# Aqua_D_CTRL.net
KiCad netlist of a schematic drawn in EAGLE
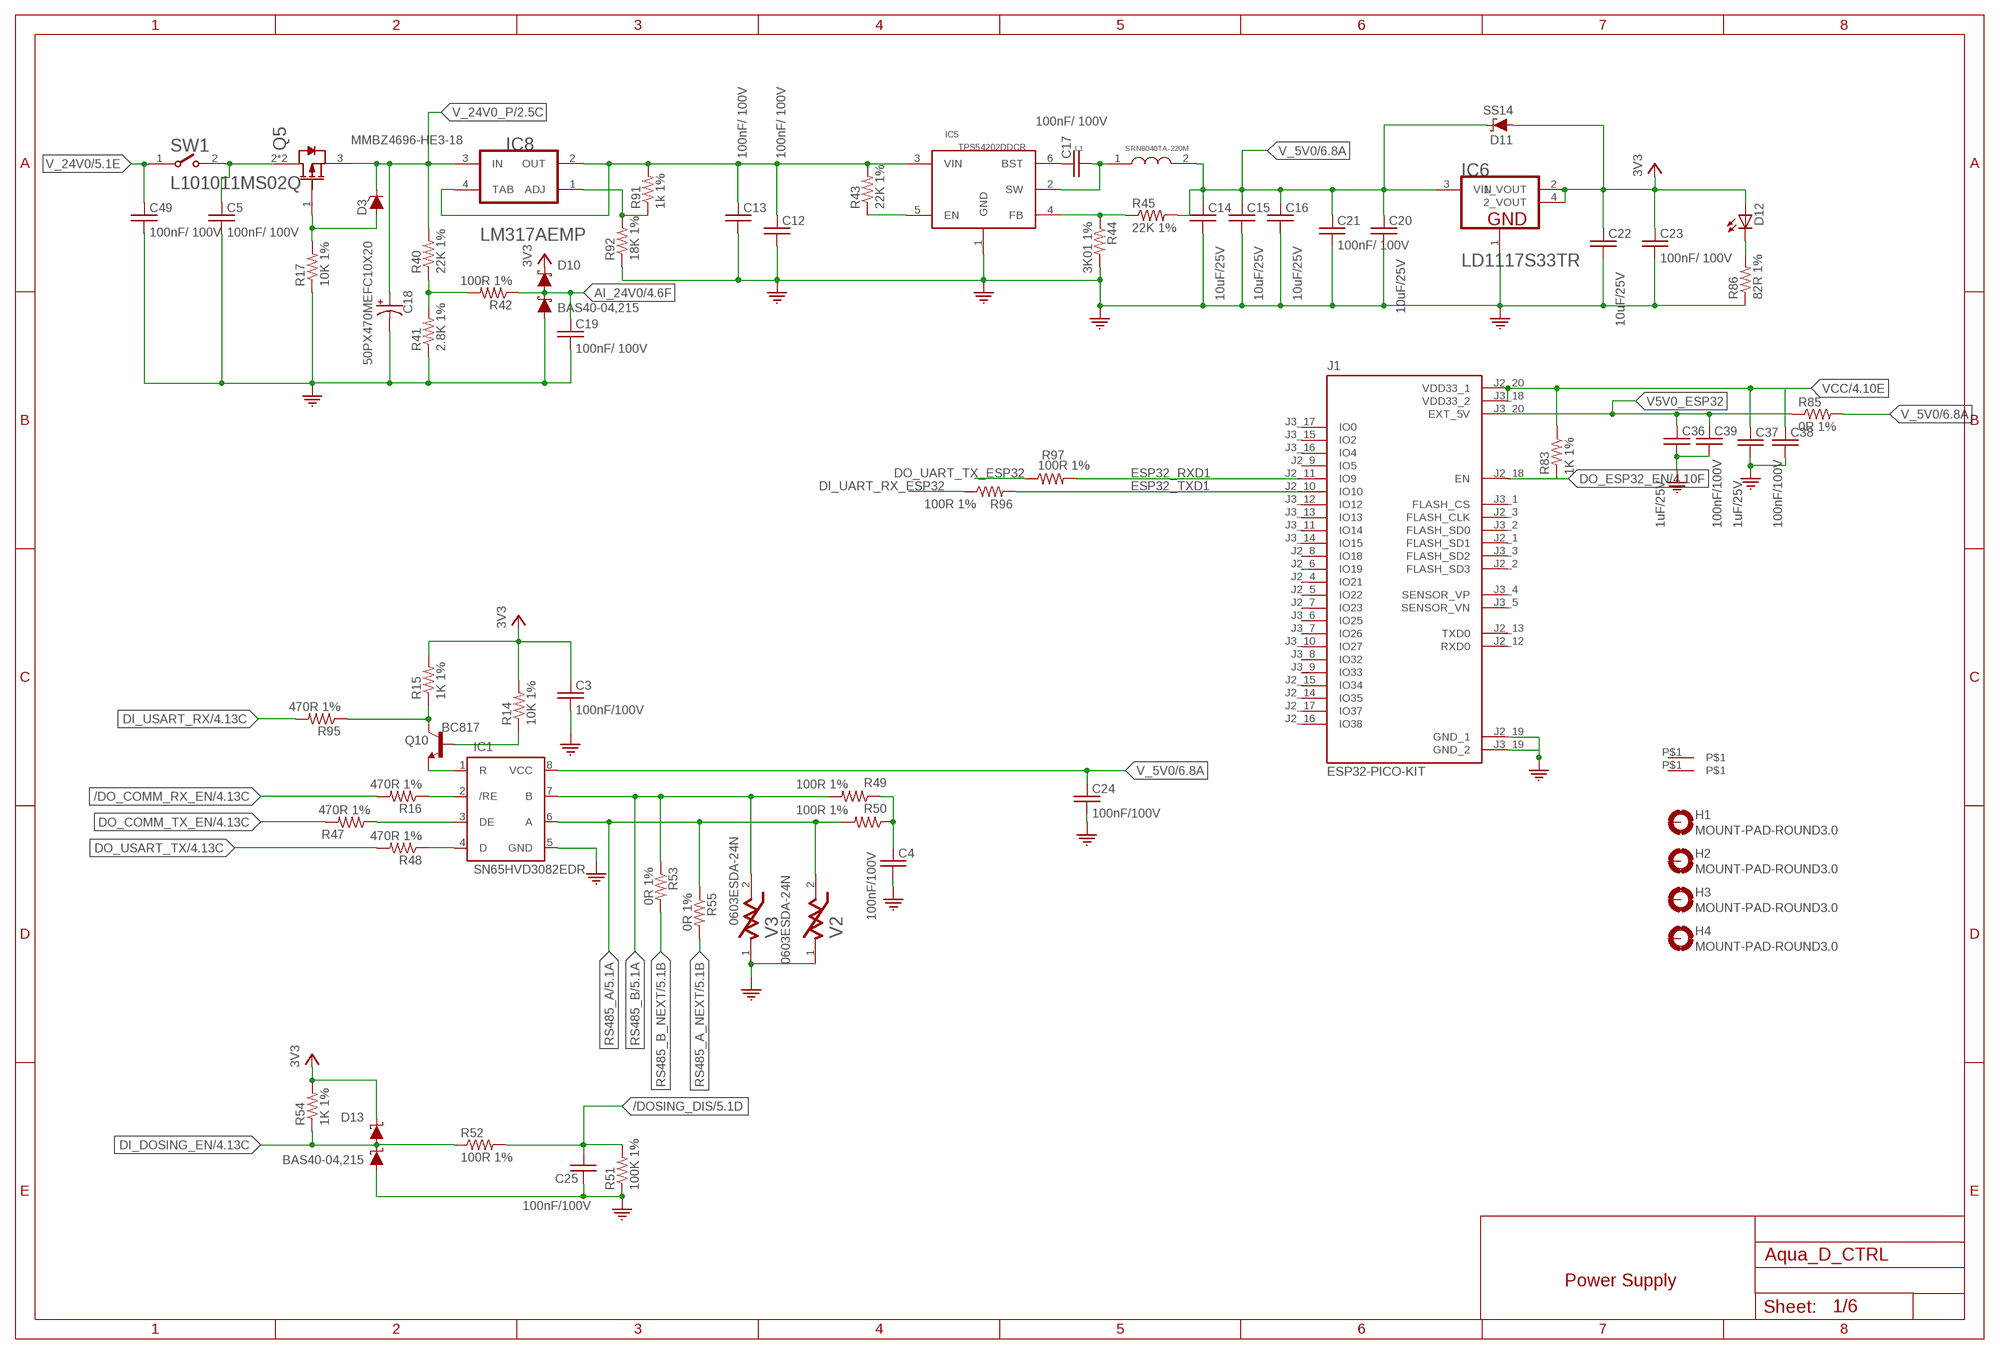
[diagram p0: schematic, sheet 1]
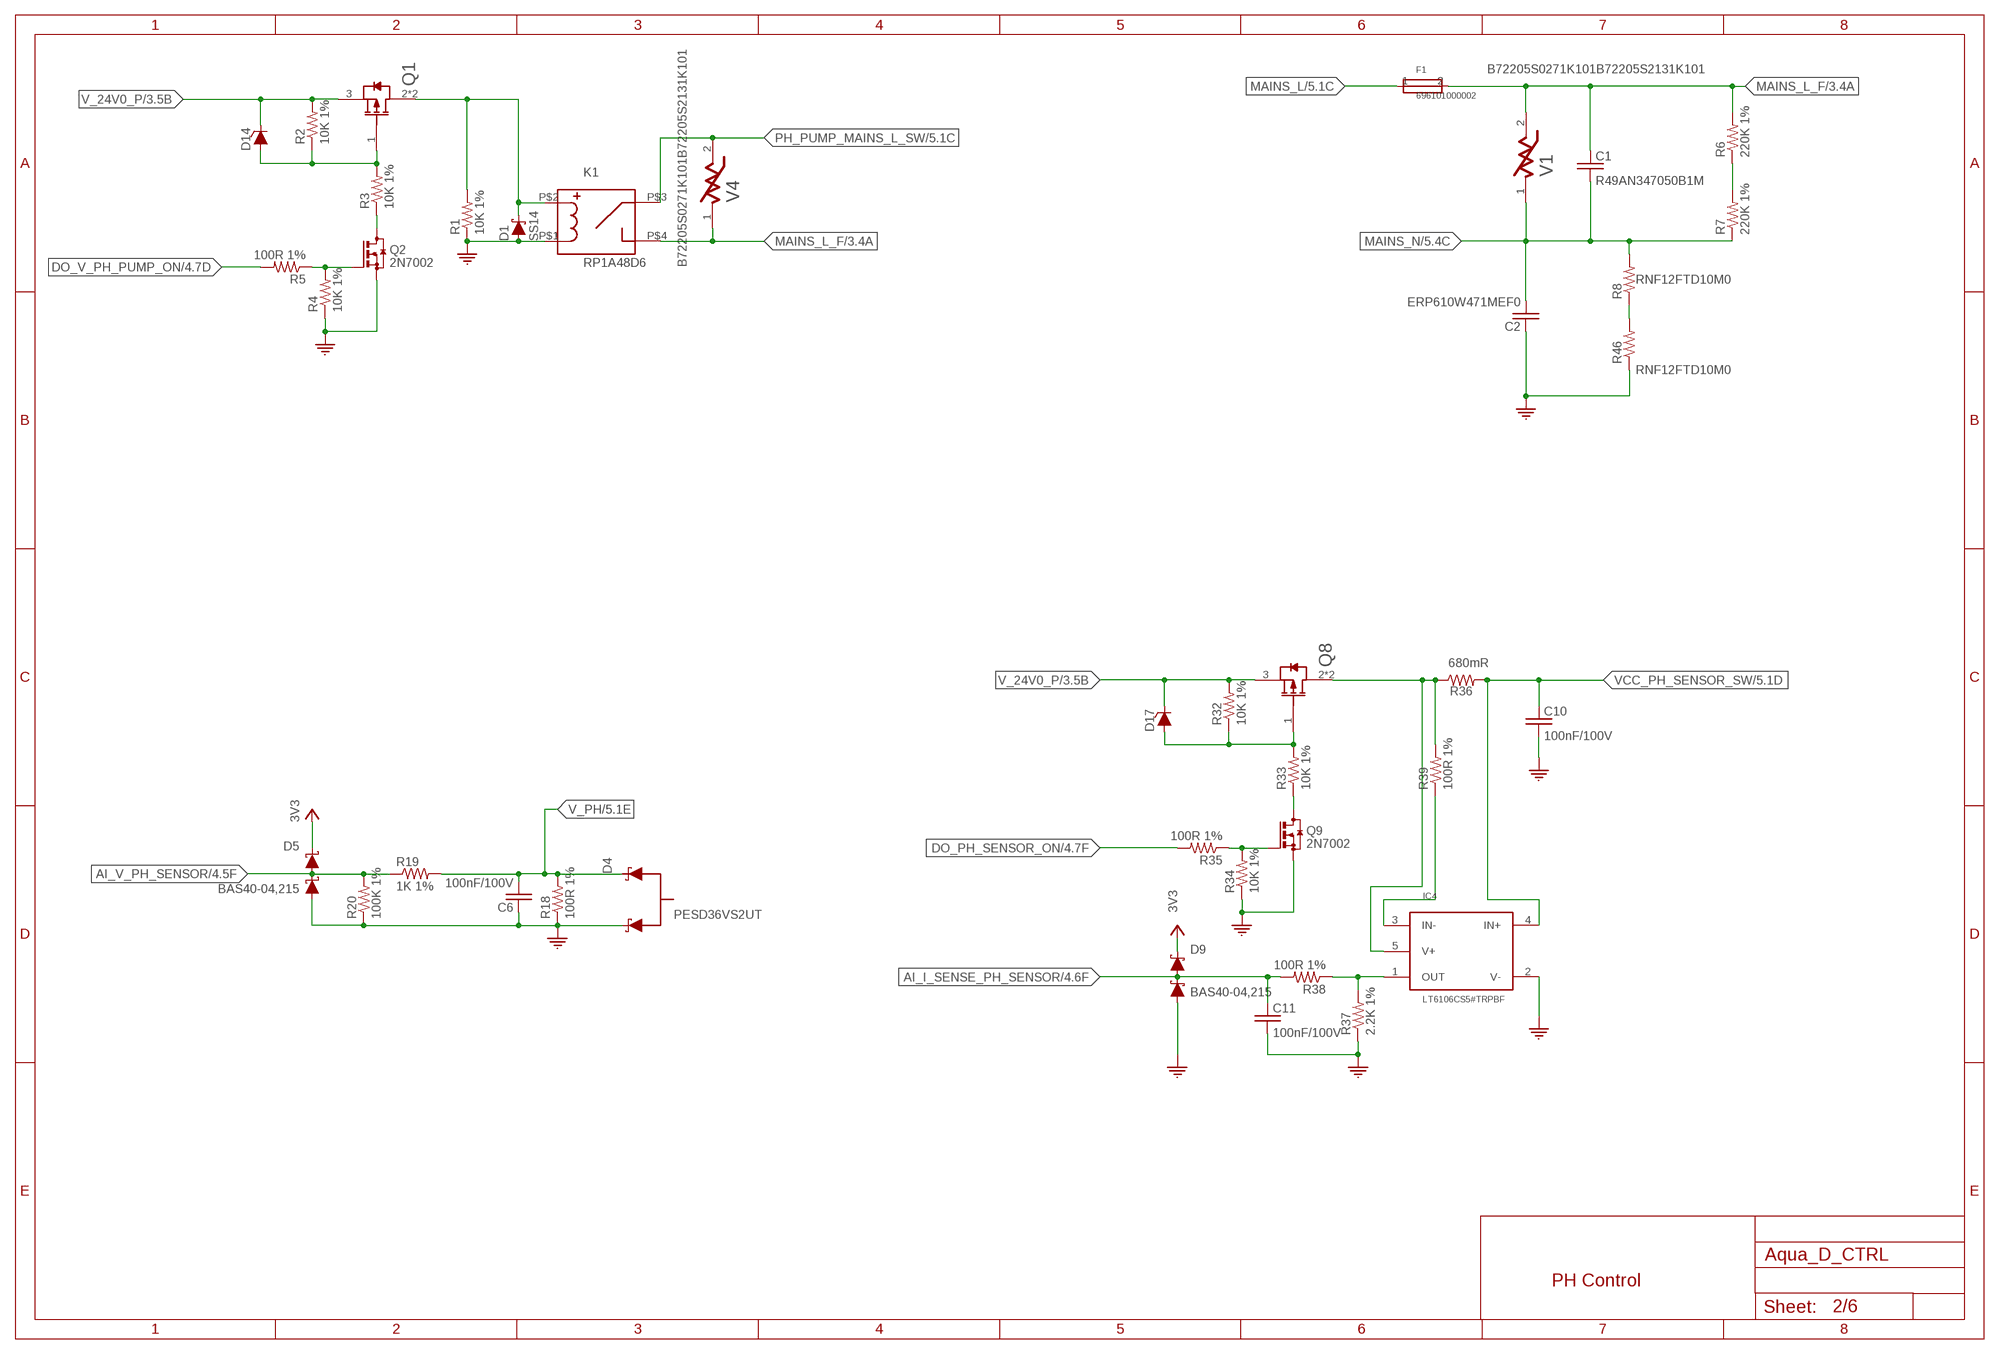
[diagram p1: schematic, sheet 2]
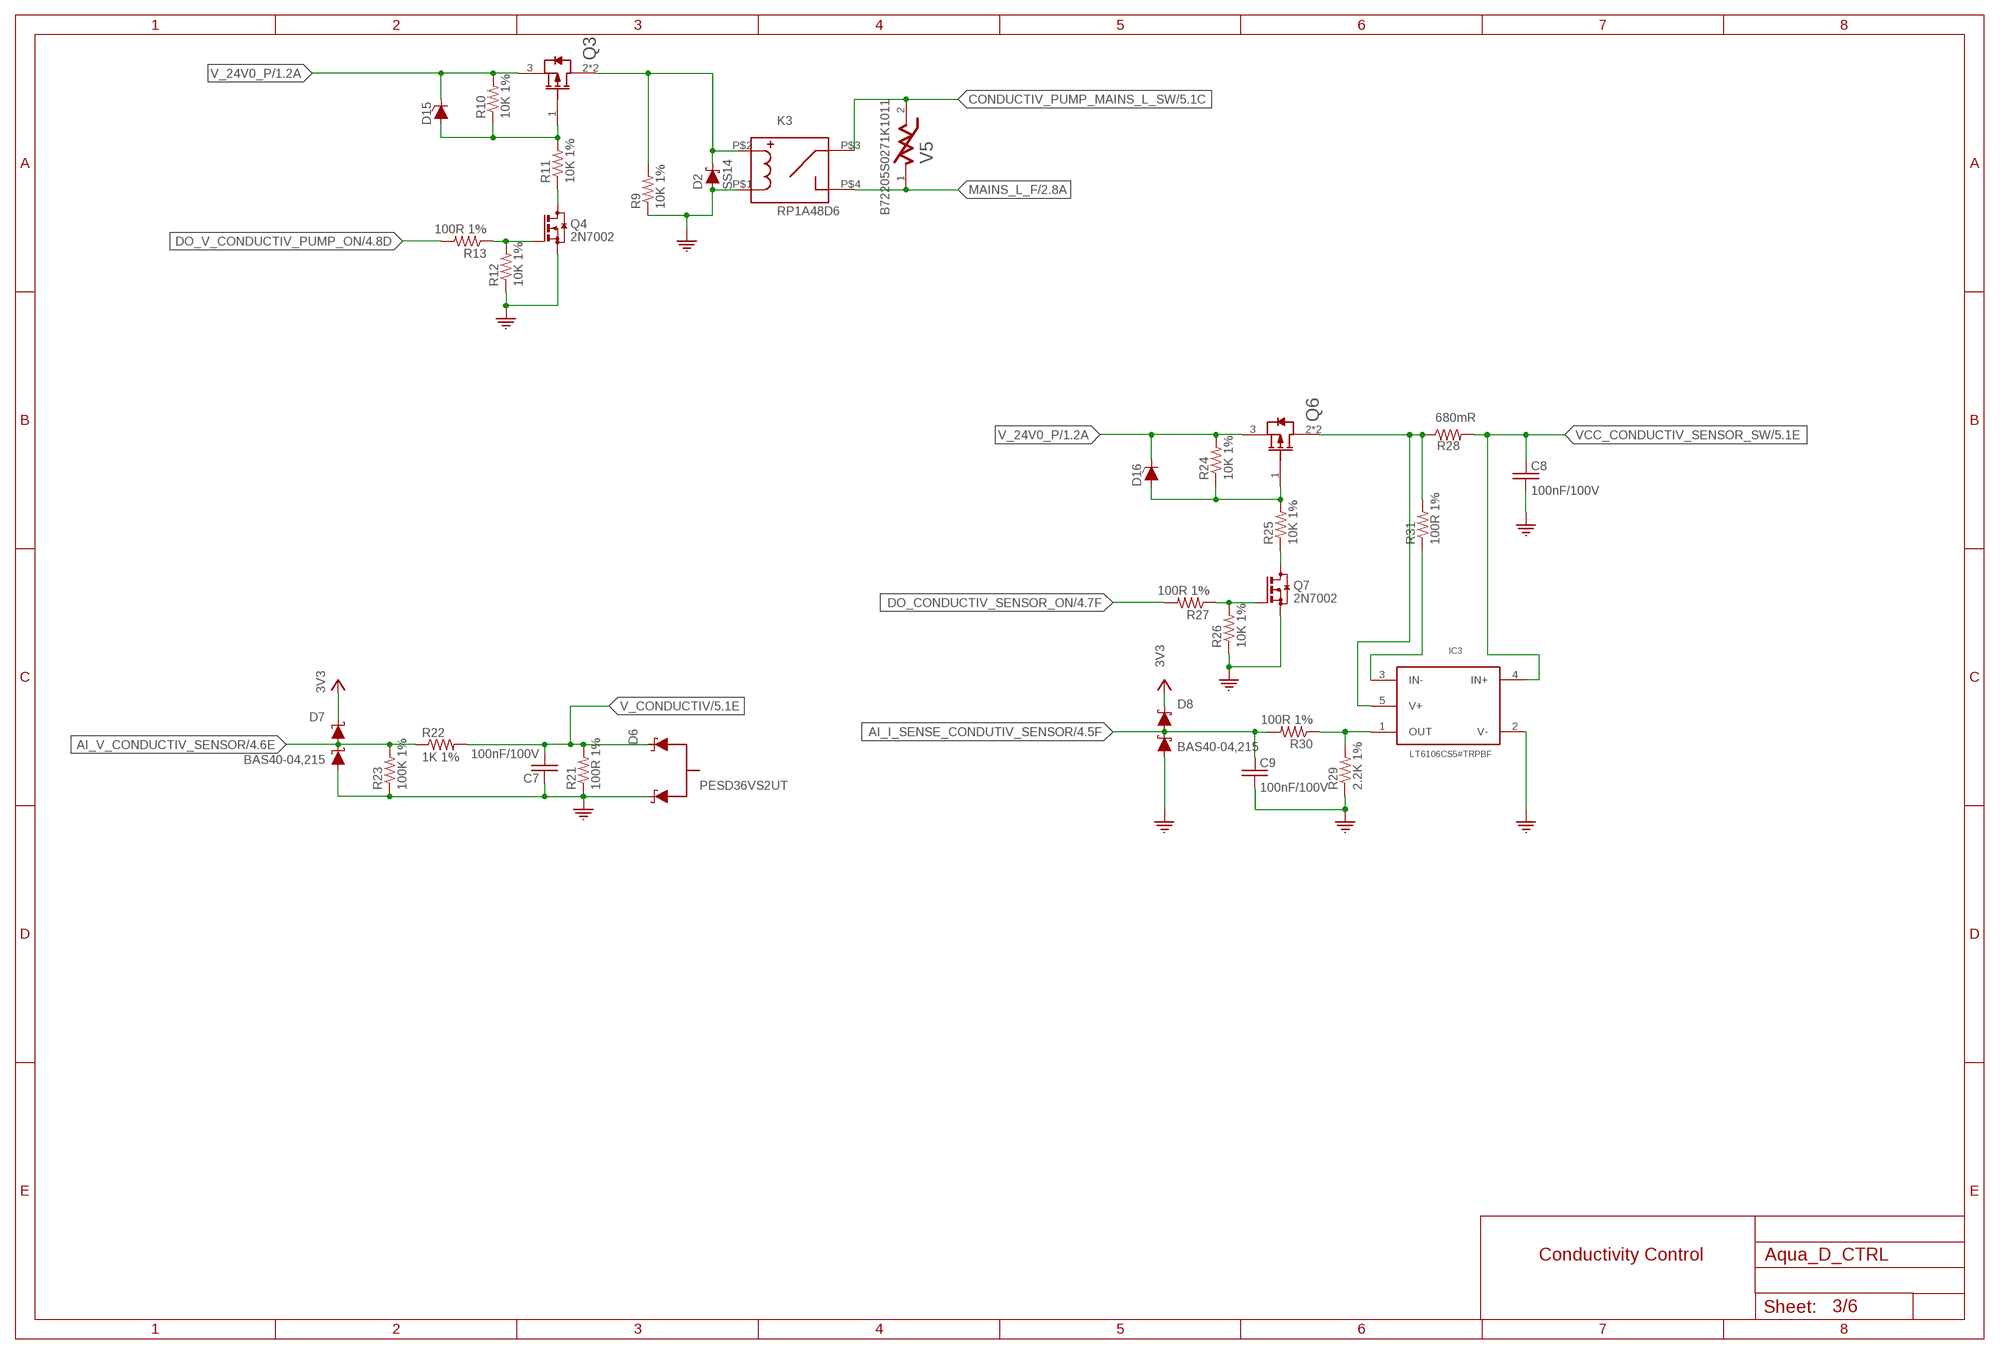
[diagram p2: schematic, sheet 3]
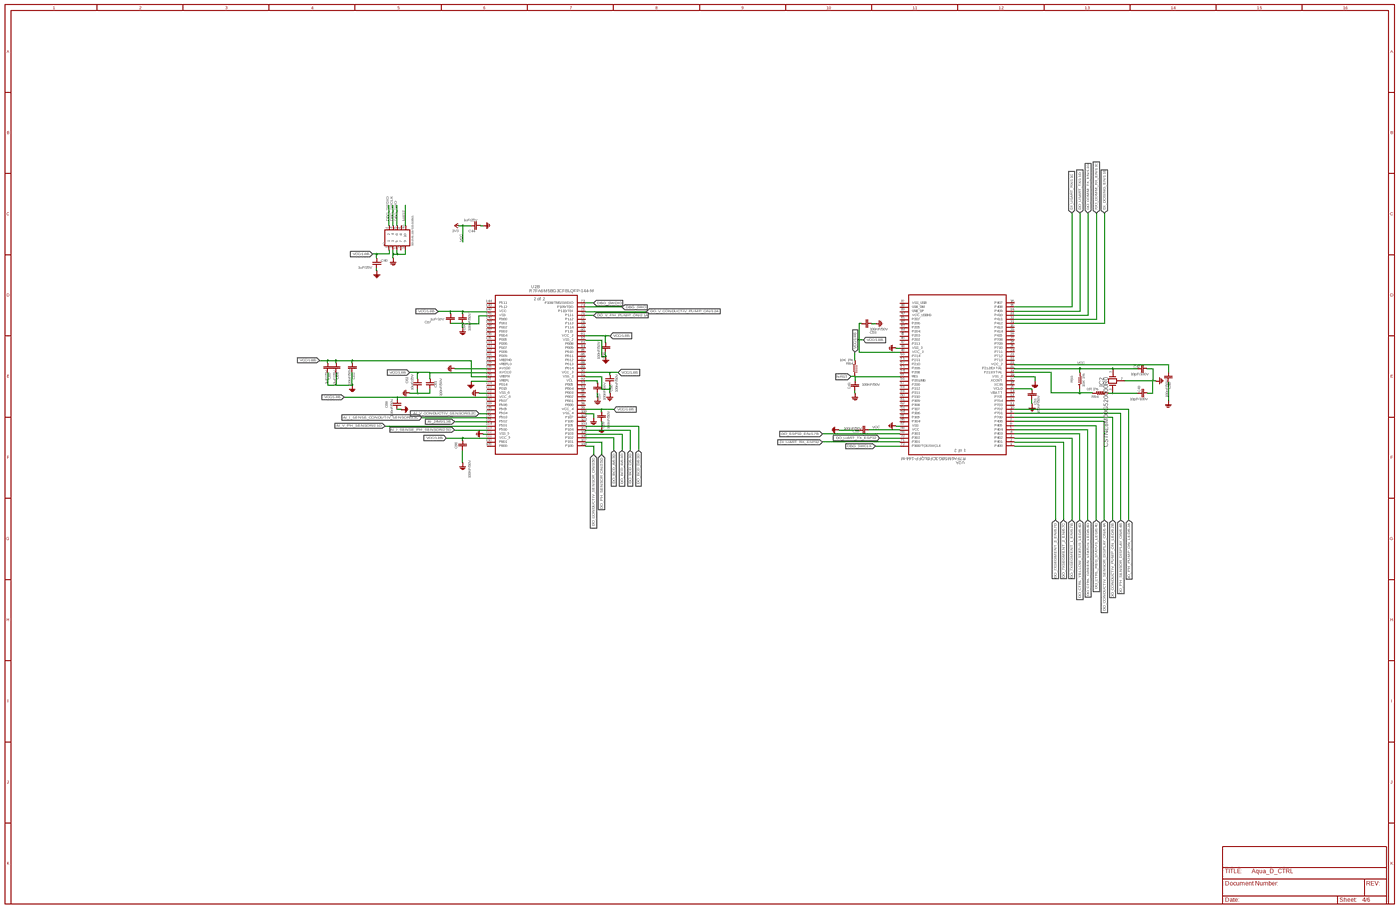
[diagram p3: schematic, sheet 4, overview]
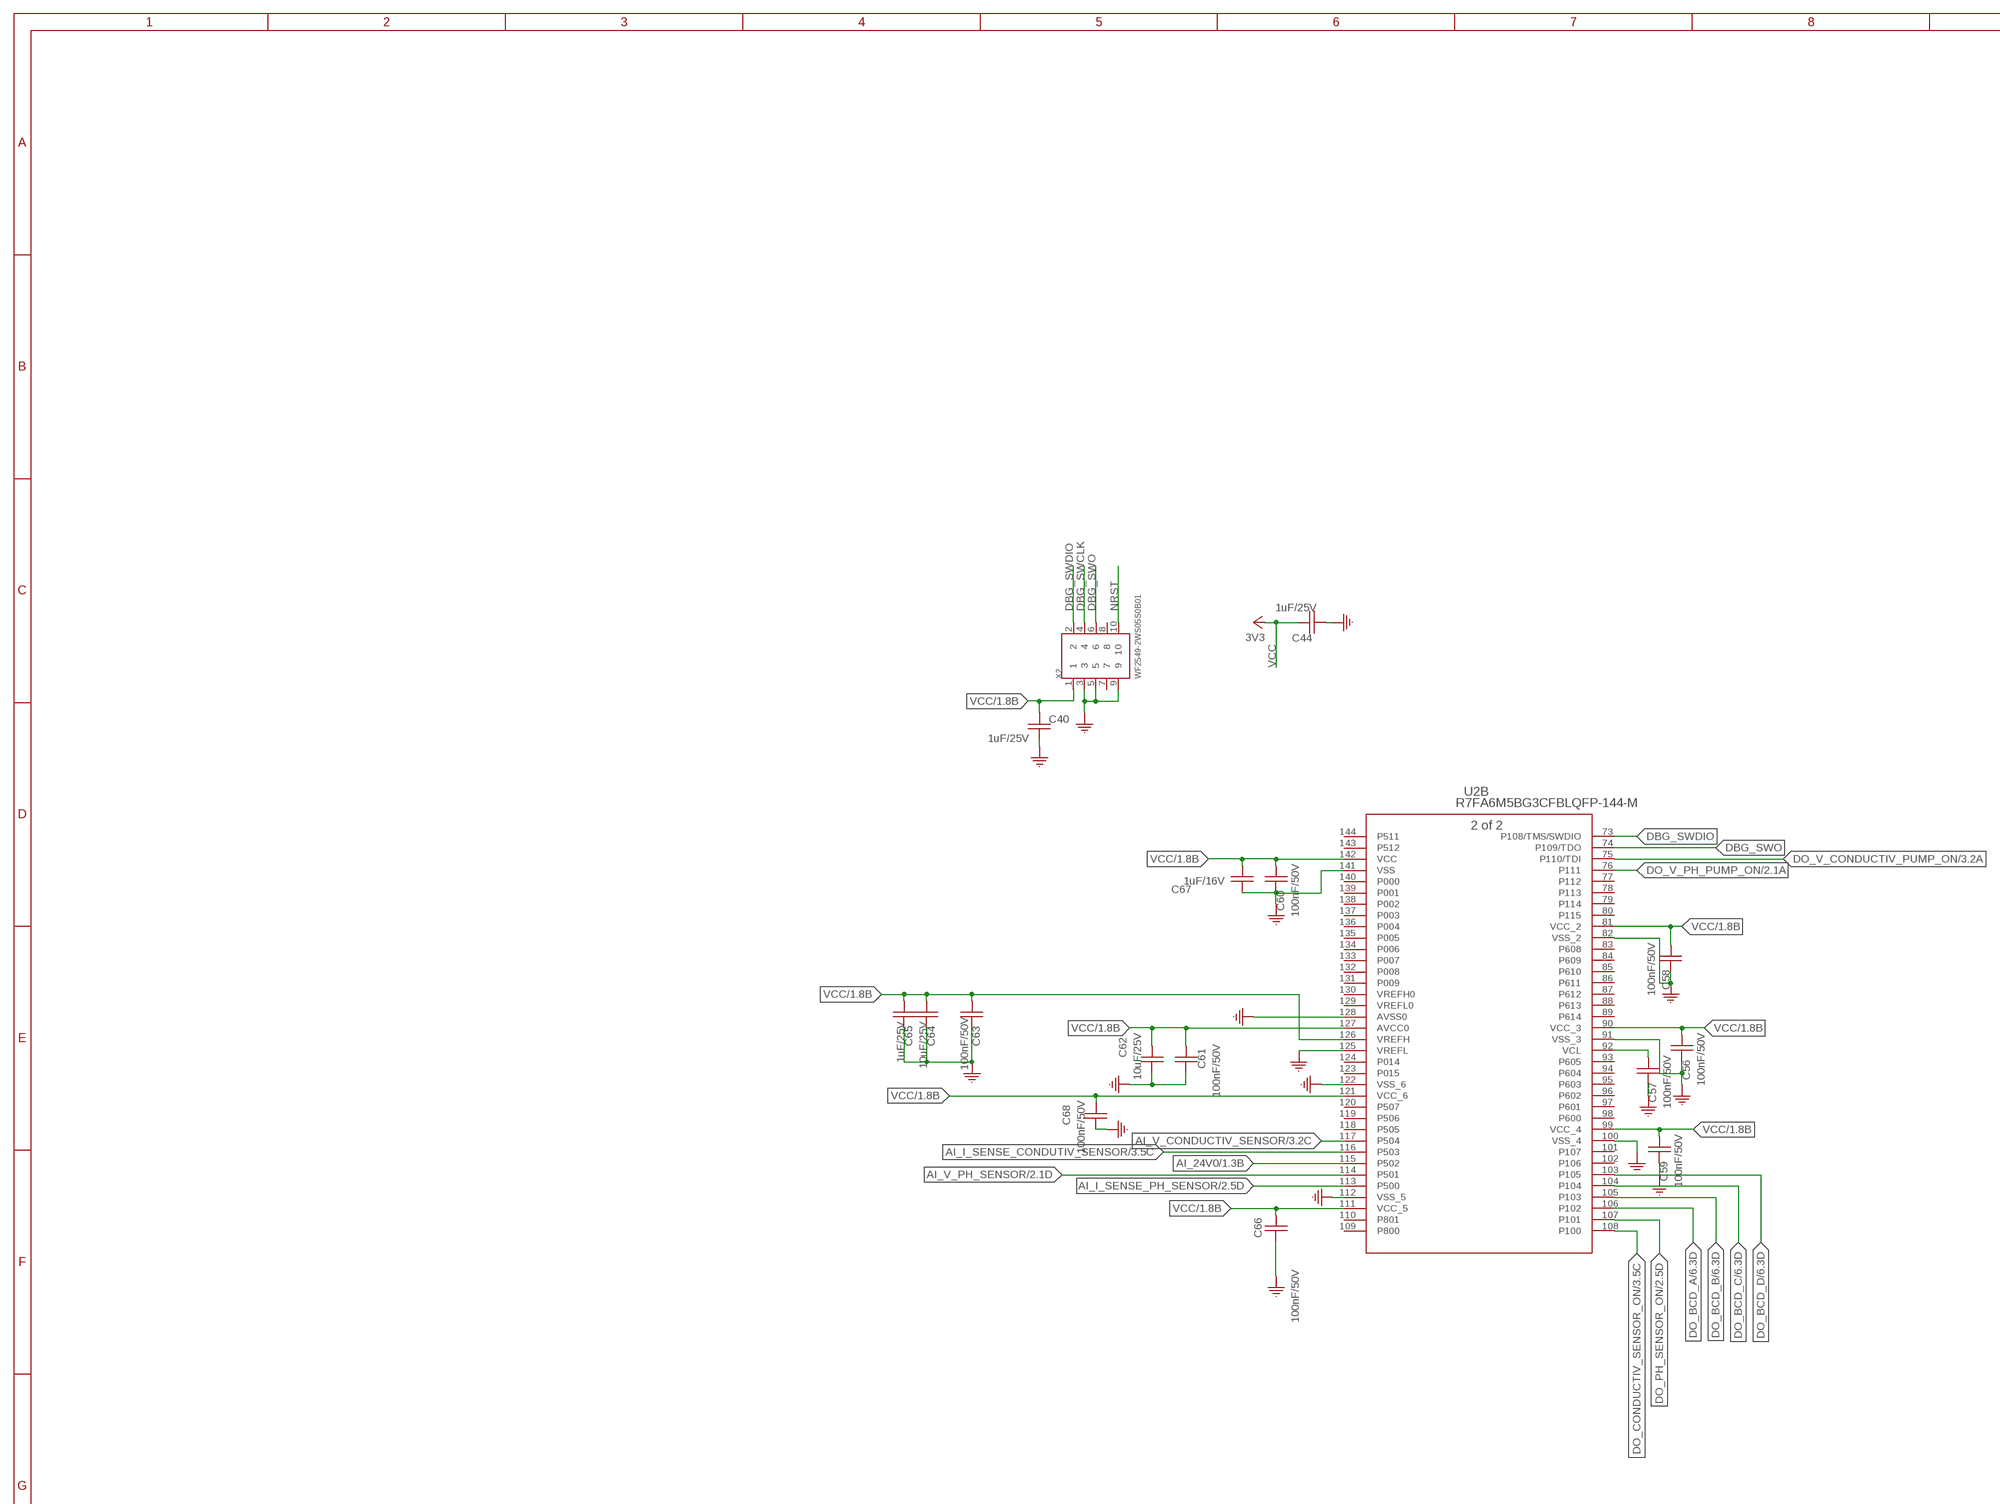
[diagram p4: schematic, sheet 4, part 1 of 4]
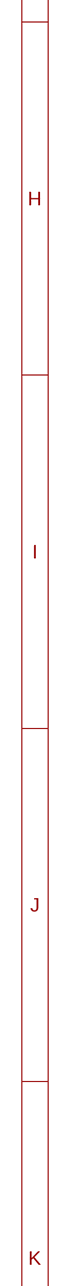
[diagram p5: schematic, sheet 4, part 2 of 4]
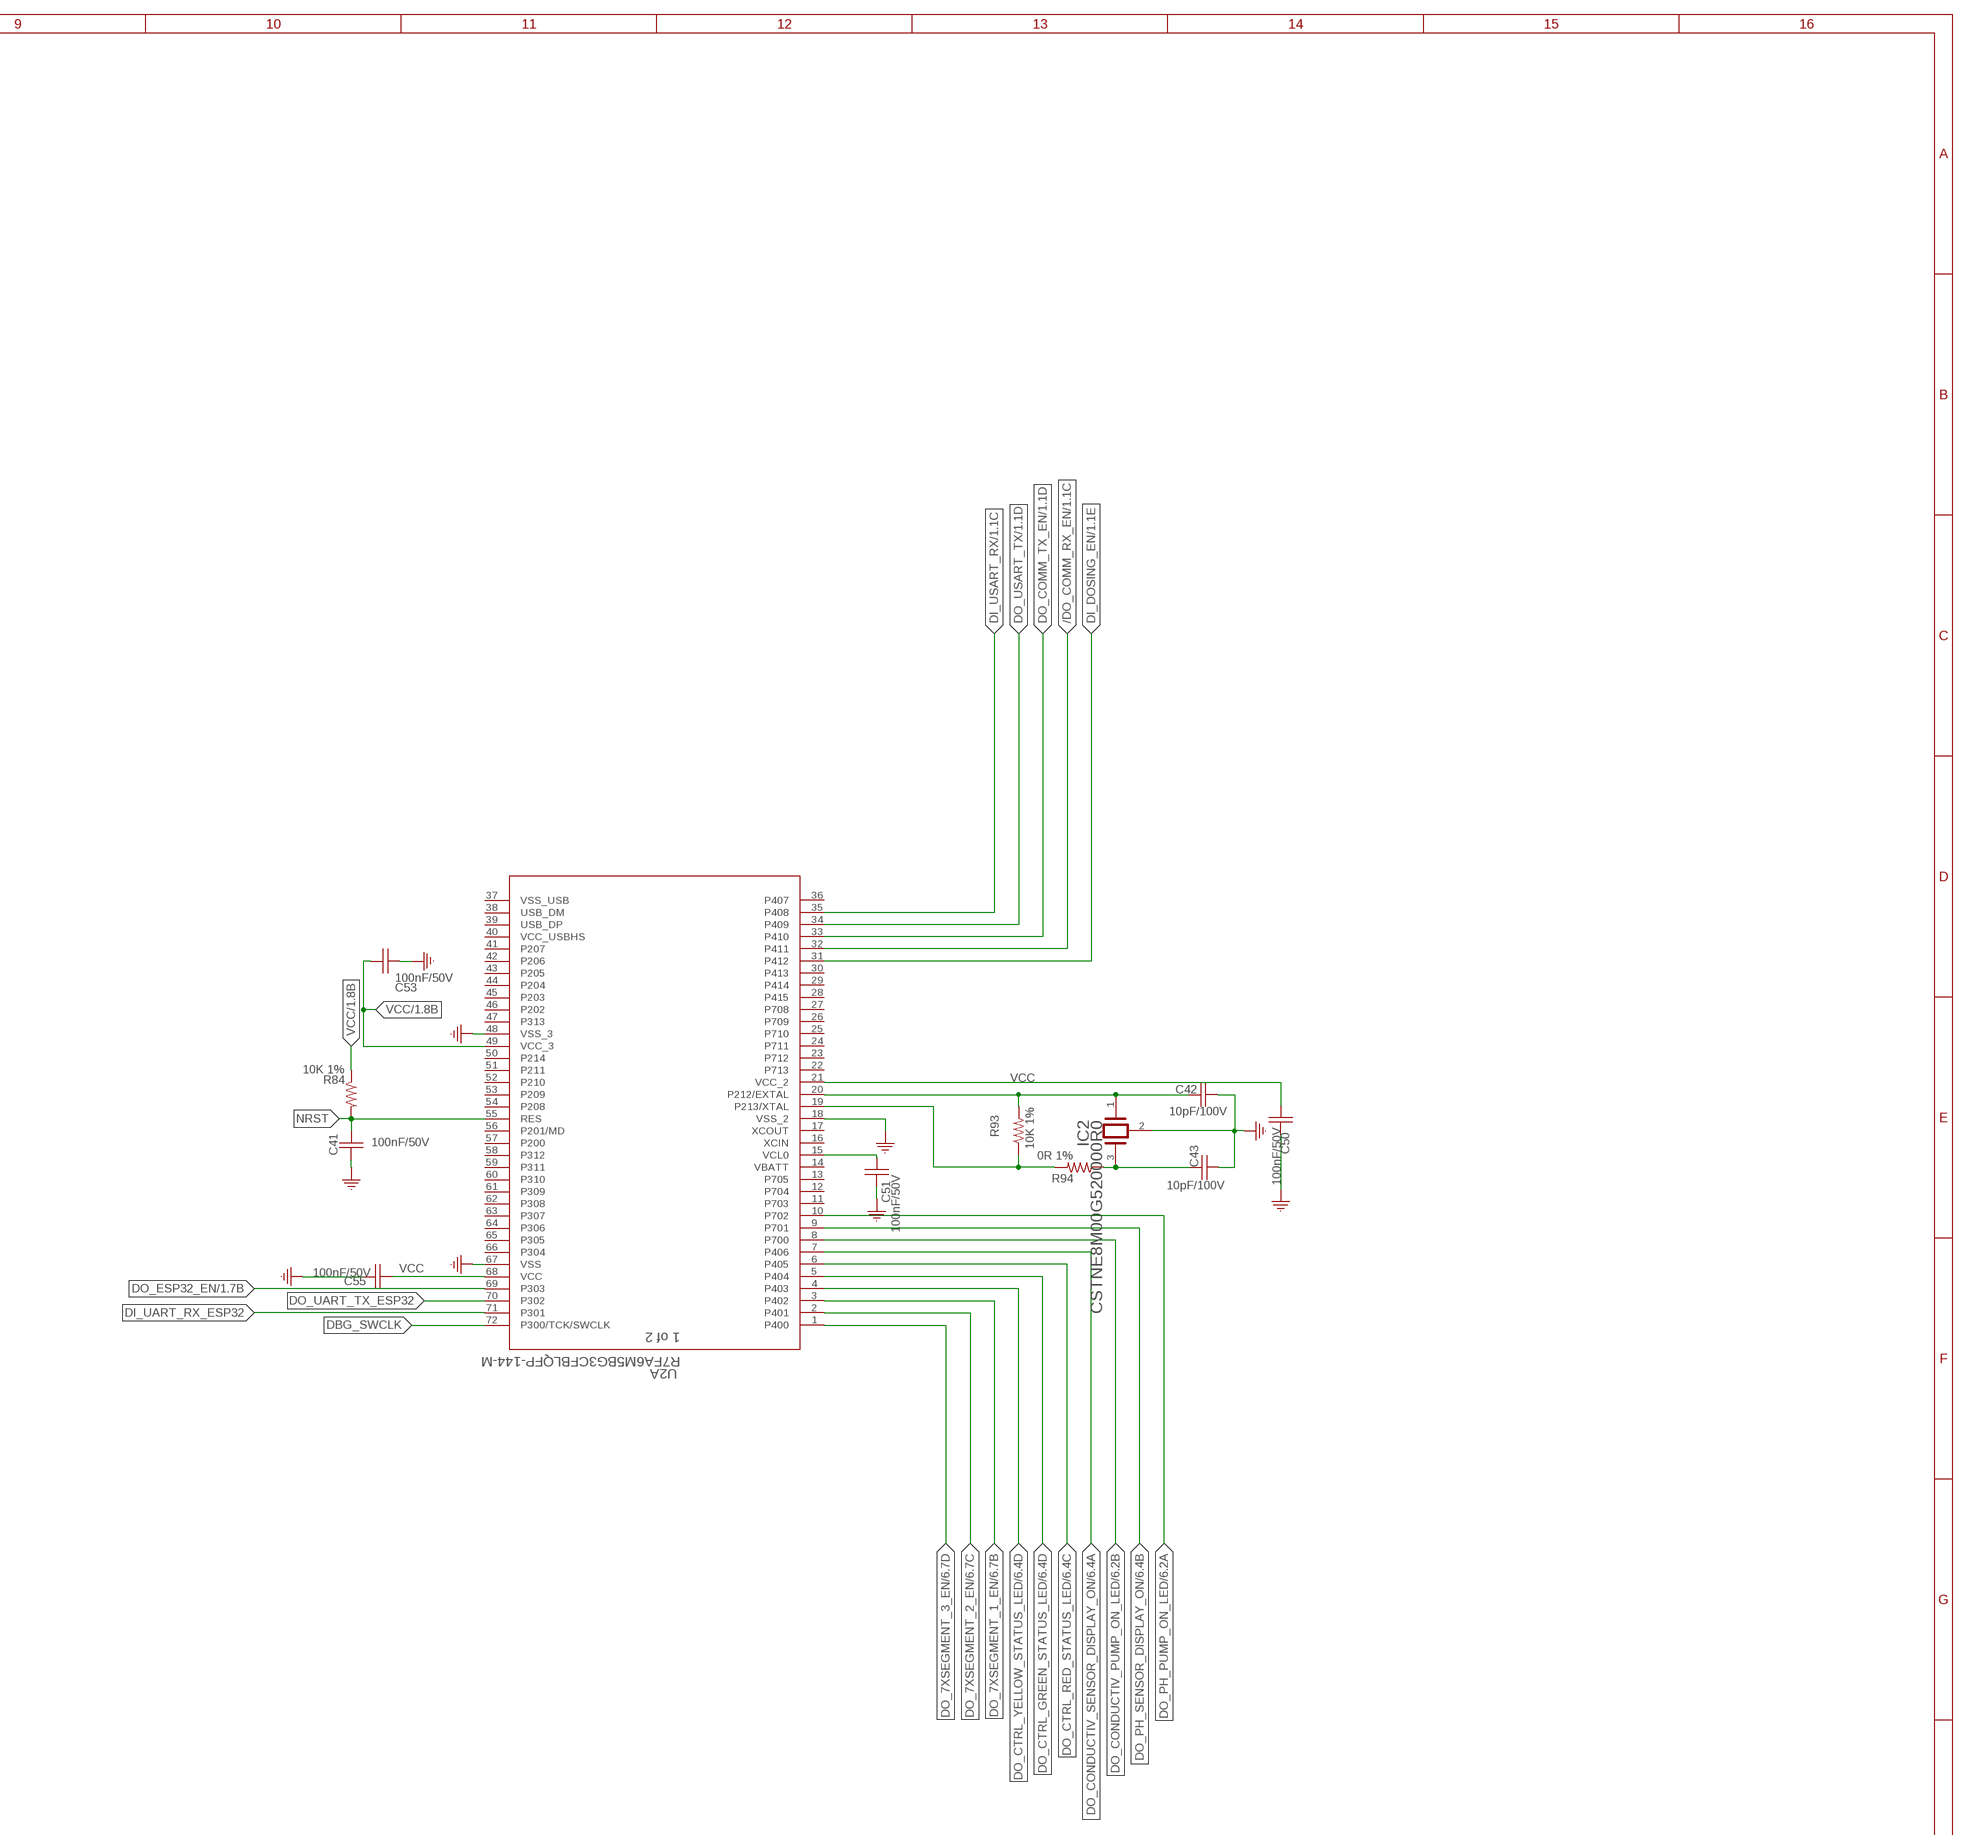
[diagram p6: schematic, sheet 4, part 3 of 4]
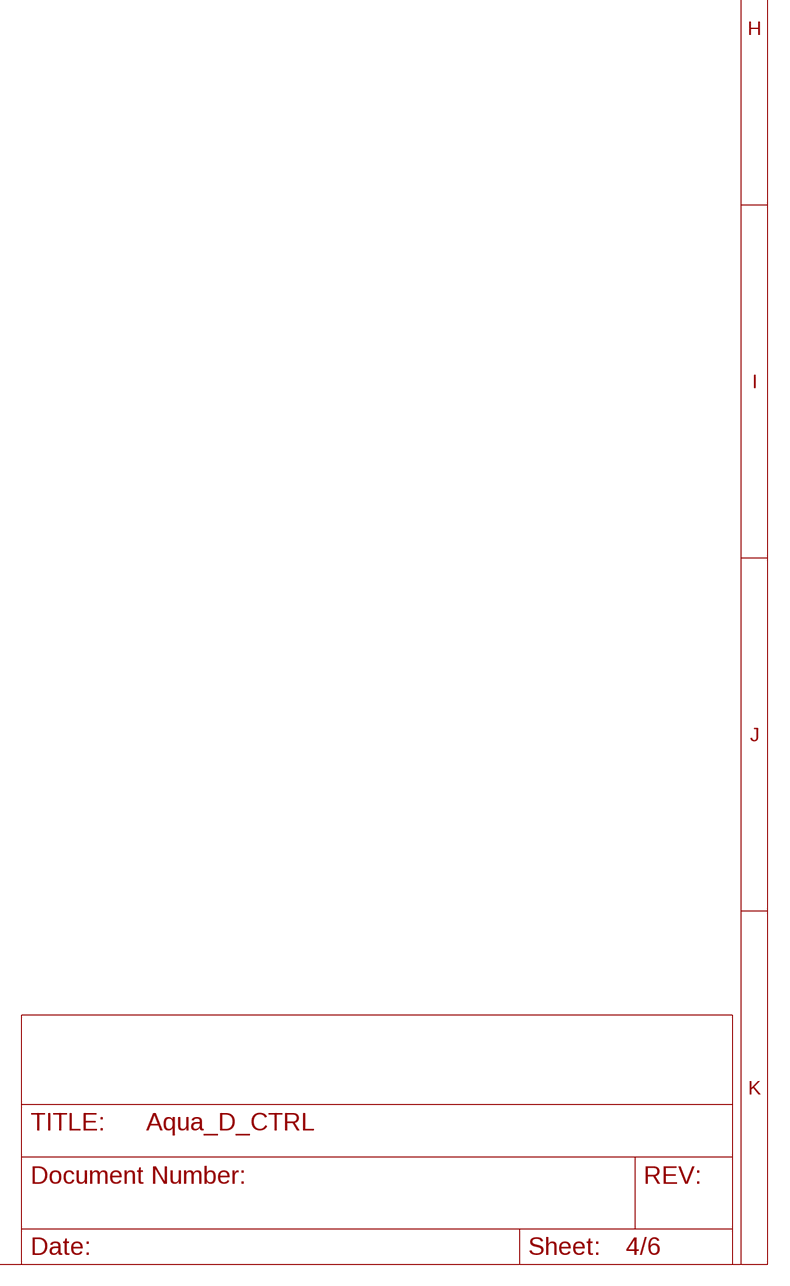
[diagram p7: schematic, sheet 4, part 4 of 4]
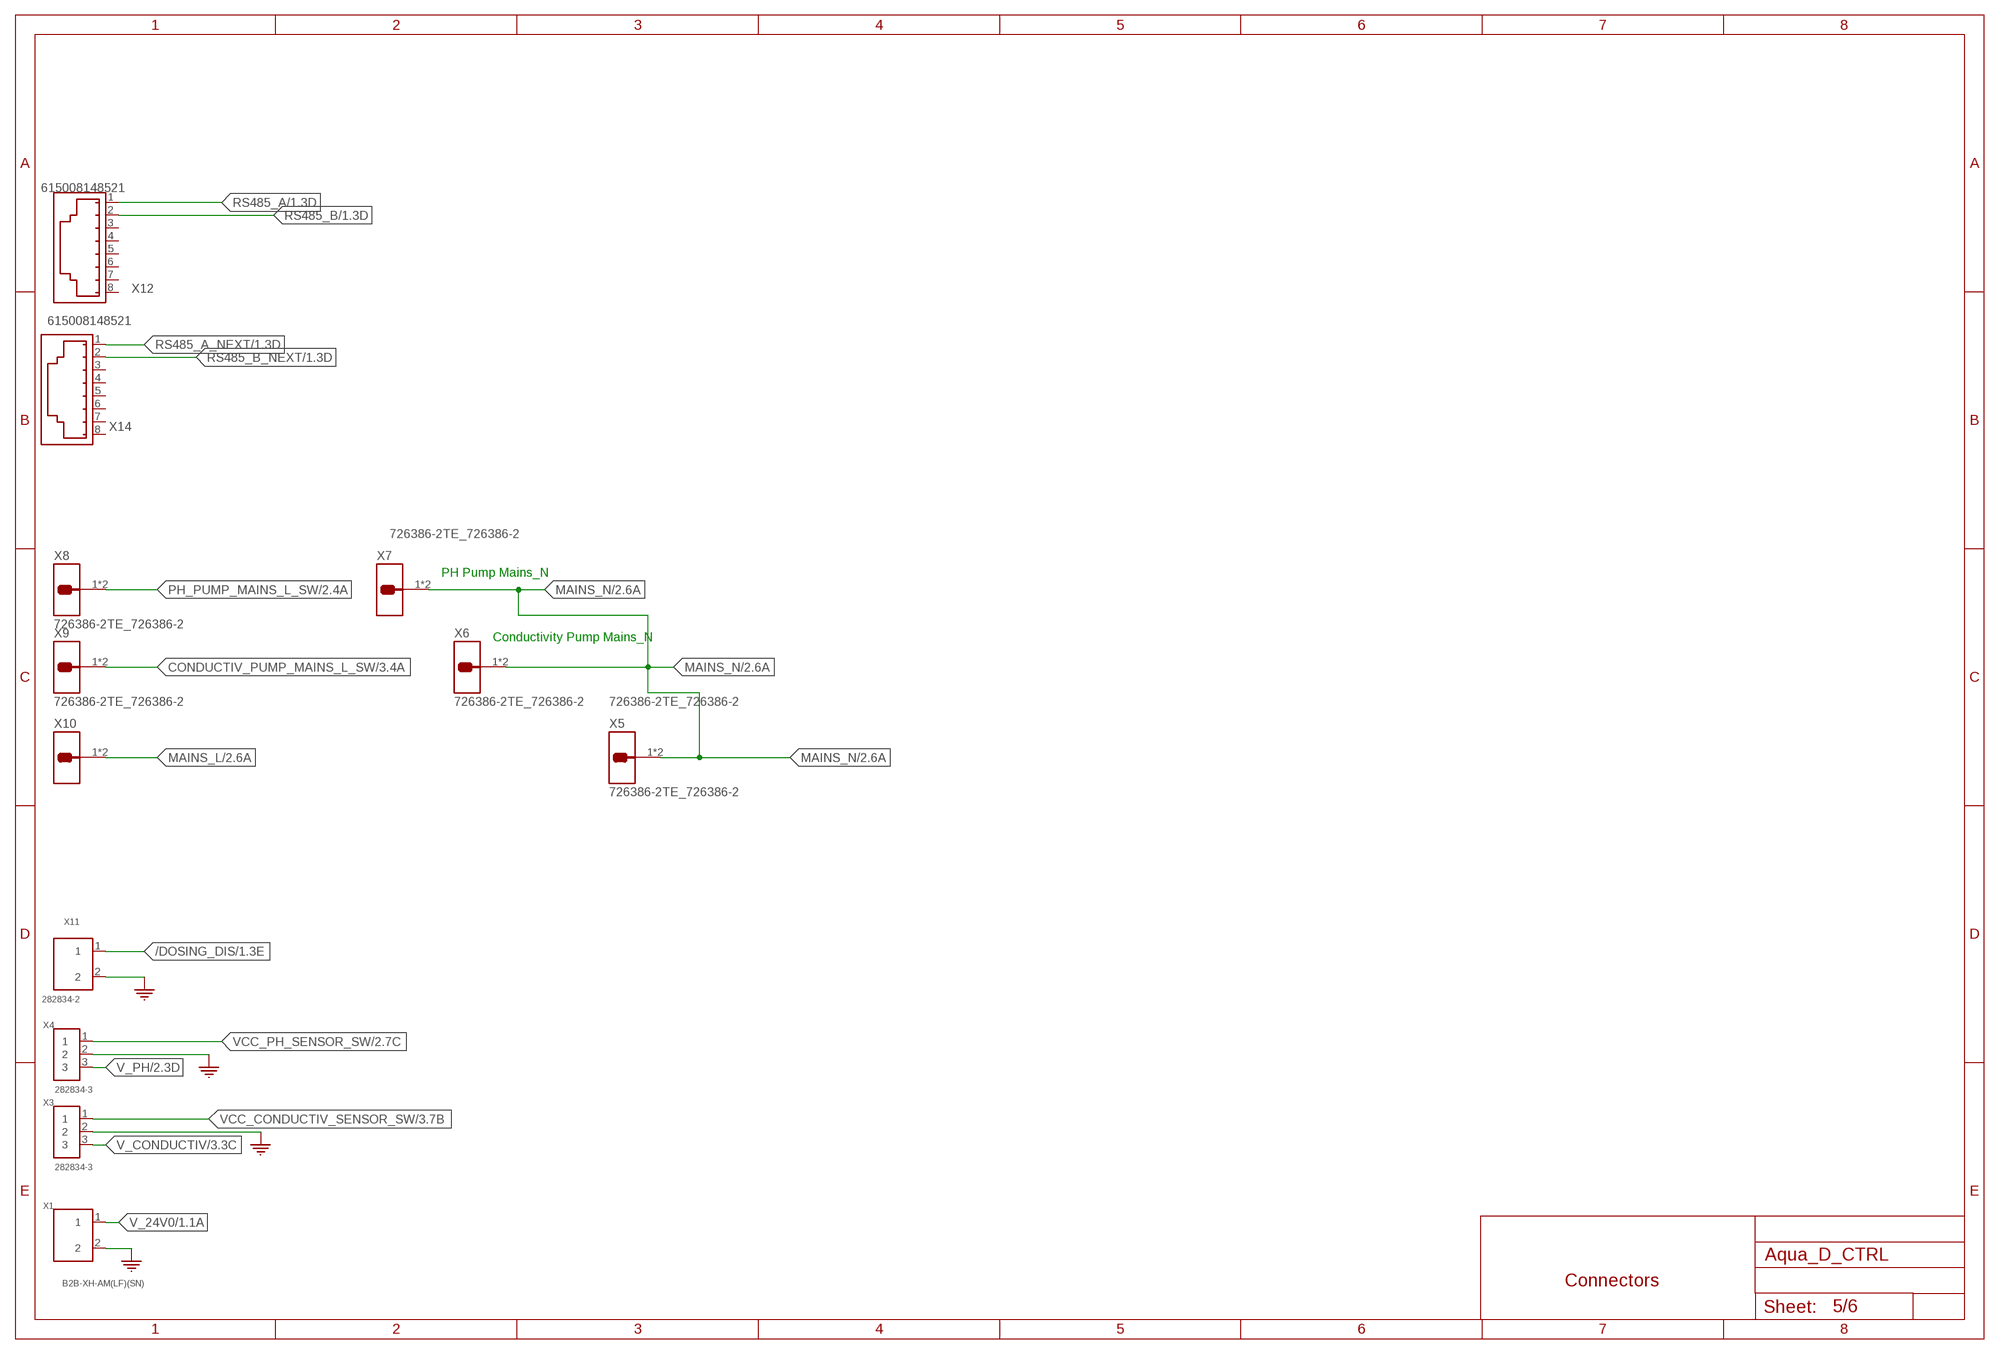
[diagram p8: schematic, sheet 5]
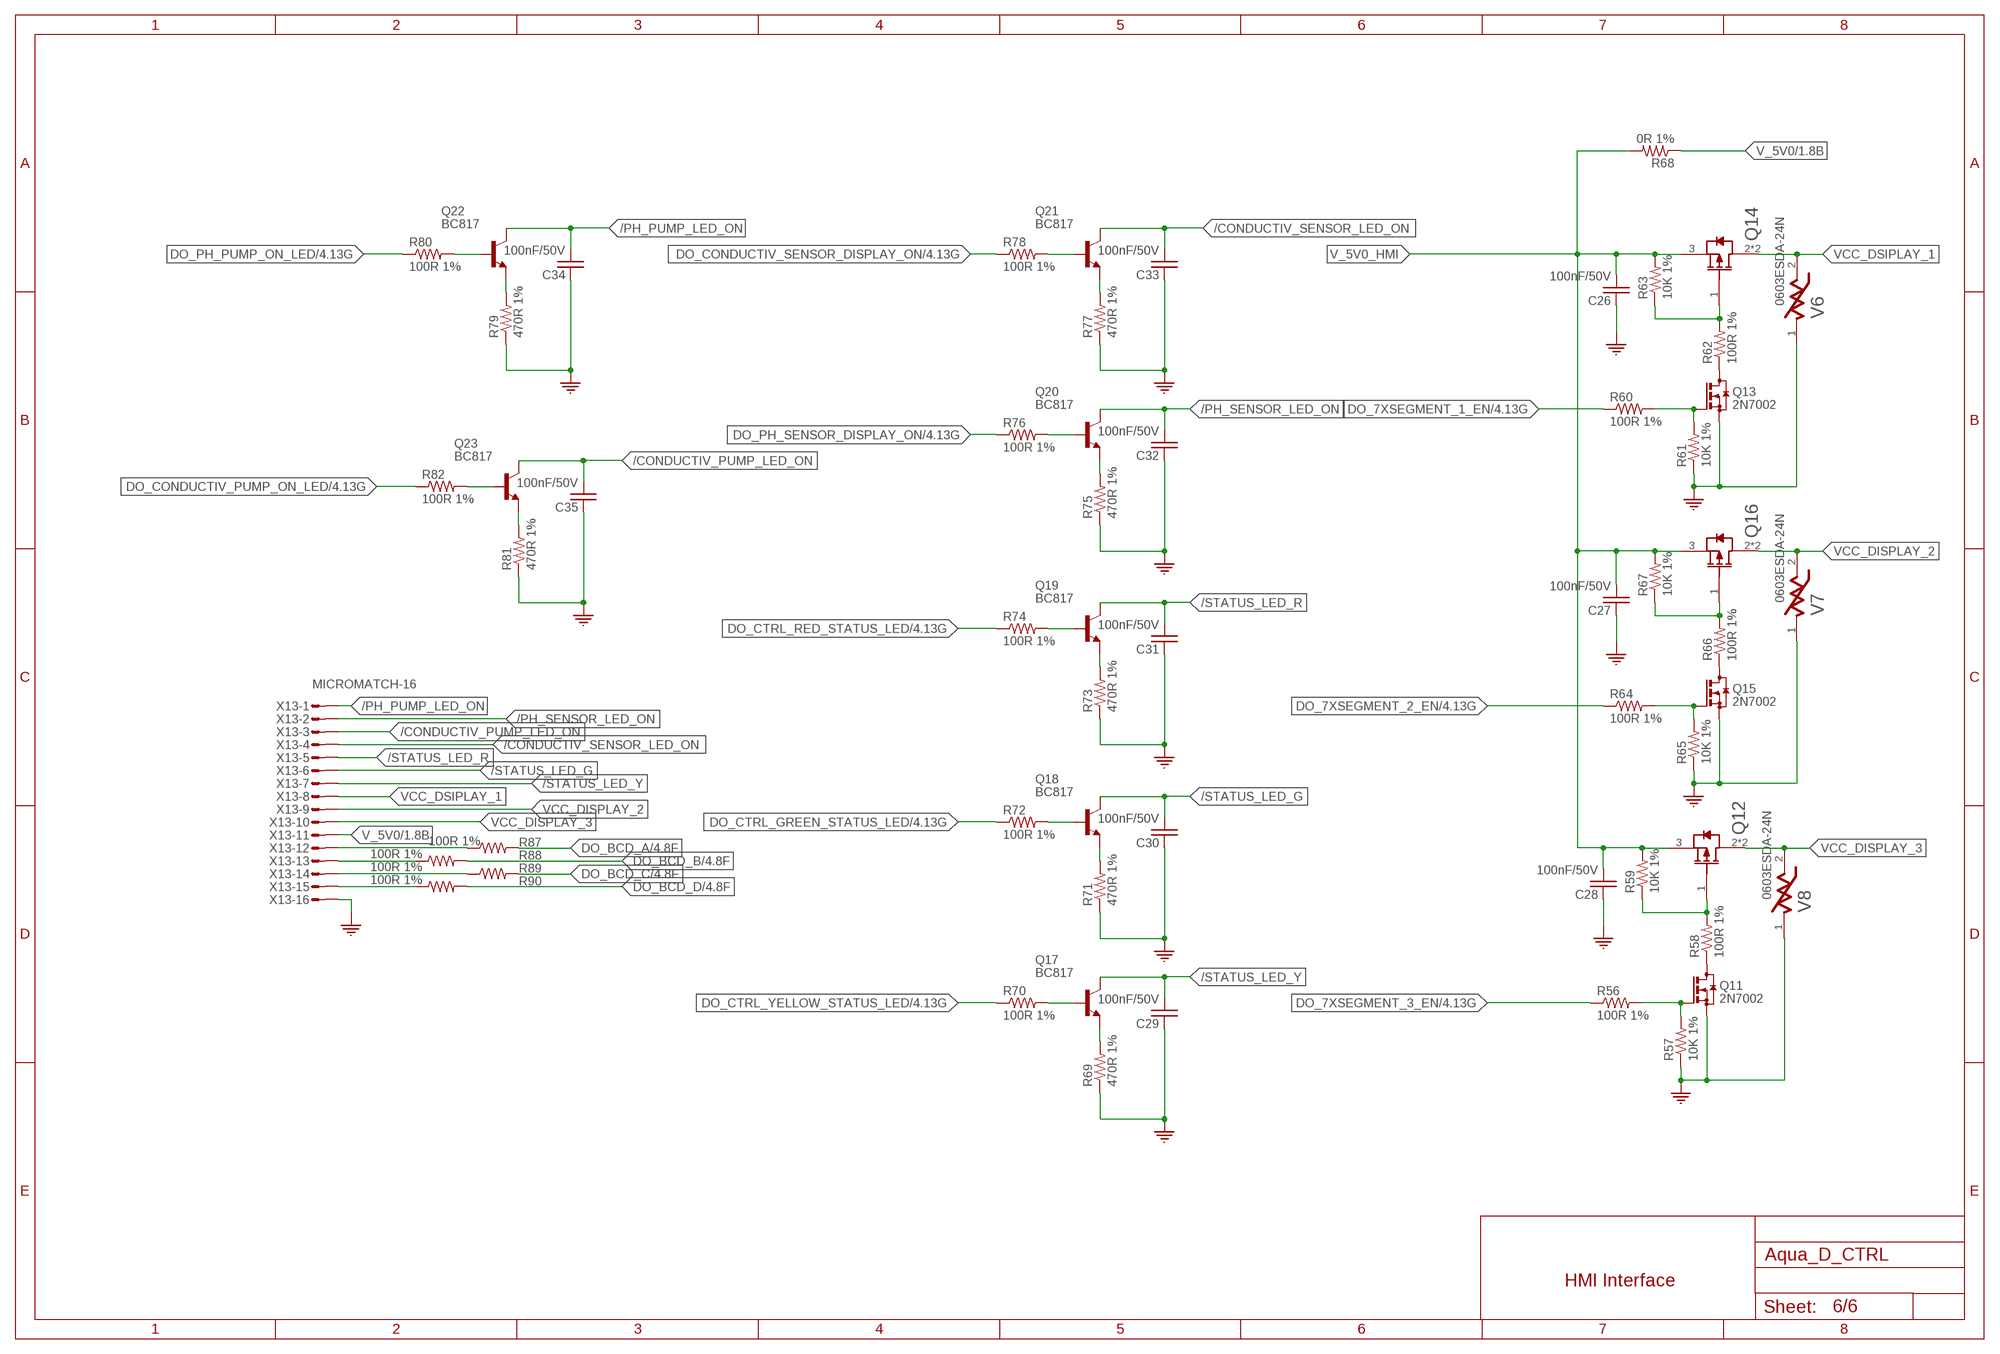
[diagram p9: schematic, sheet 6]

(export (version "E")
  (design (tool "Eeschema 10.0.6"))
  (components
    (comp (ref "C40")
      (value "1uF/25V")
      (footprint "eagle-import:0603")
      (libsource (lib "eagle-import") (part "C_0603"))
    )
    (comp (ref "C41")
      (value "100nF/50V")
      (footprint "eagle-import:0603")
      (libsource (lib "eagle-import") (part "C_0603"))
    )
    (comp (ref "C42")
      (value "10pF/100V")
      (footprint "eagle-import:0603")
      (libsource (lib "eagle-import") (part "C_0603"))
    )
    (comp (ref "C43")
      (value "10pF/100V")
      (footprint "eagle-import:0603")
      (libsource (lib "eagle-import") (part "C_0603"))
    )
    (comp (ref "C44")
      (value "1uF/25V")
      (footprint "eagle-import:0603")
      (libsource (lib "eagle-import") (part "C_0603"))
    )
    (comp (ref "C50")
      (value "100nF/50V")
      (footprint "eagle-import:0603")
      (libsource (lib "eagle-import") (part "C_0603"))
    )
    (comp (ref "C51")
      (value "100nF/50V")
      (footprint "eagle-import:0603")
      (libsource (lib "eagle-import") (part "C_0603"))
    )
    (comp (ref "C53")
      (value "100nF/50V")
      (footprint "eagle-import:0603")
      (libsource (lib "eagle-import") (part "C_0603"))
    )
    (comp (ref "C55")
      (value "100nF/50V")
      (footprint "eagle-import:0603")
      (libsource (lib "eagle-import") (part "C_0603"))
    )
    (comp (ref "C56")
      (value "100nF/50V")
      (footprint "eagle-import:0603")
      (libsource (lib "eagle-import") (part "C_0603"))
    )
    (comp (ref "C57")
      (value "100nF/50V")
      (footprint "eagle-import:0603")
      (libsource (lib "eagle-import") (part "C_0603"))
    )
    (comp (ref "C58")
      (value "100nF/50V")
      (footprint "eagle-import:0603")
      (libsource (lib "eagle-import") (part "C_0603"))
    )
    (comp (ref "C59")
      (value "100nF/50V")
      (footprint "eagle-import:0603")
      (libsource (lib "eagle-import") (part "C_0603"))
    )
    (comp (ref "C60")
      (value "100nF/50V")
      (footprint "eagle-import:0603")
      (libsource (lib "eagle-import") (part "C_0603"))
    )
    (comp (ref "C61")
      (value "100nF/50V")
      (footprint "eagle-import:0603")
      (libsource (lib "eagle-import") (part "C_0603"))
    )
    (comp (ref "C62")
      (value "10uF/25V")
      (footprint "eagle-import:0603")
      (libsource (lib "eagle-import") (part "C_0603"))
    )
    (comp (ref "C63")
      (value "100nF/50V")
      (footprint "eagle-import:0603")
      (libsource (lib "eagle-import") (part "C_0603"))
    )
    (comp (ref "C64")
      (value "10uF/25V")
      (footprint "eagle-import:0603")
      (libsource (lib "eagle-import") (part "C_0603"))
    )
    (comp (ref "C65")
      (value "1uF/25V")
      (footprint "eagle-import:0603")
      (libsource (lib "eagle-import") (part "C_0603"))
    )
    (comp (ref "C66")
      (value "100nF/50V")
      (footprint "eagle-import:0603")
      (libsource (lib "eagle-import") (part "C_0603"))
    )
    (comp (ref "C67")
      (value "1uF/16V")
      (footprint "eagle-import:0603")
      (libsource (lib "eagle-import") (part "C_0603"))
    )
    (comp (ref "C68")
      (value "100nF/50V")
      (footprint "eagle-import:0603")
      (libsource (lib "eagle-import") (part "C_0603"))
    )
    (comp (ref "IC2")
      (value "CSTNE8M00G520000R0")
      (footprint "eagle-import:CSTNE8M00G520000R0")
      (fields (field (name "MFR") "Murata"))
      (libsource (lib "eagle-import") (part "CSTNE8M00G520000R0"))
    )
    (comp (ref "R84")
      (value "10K 1%")
      (footprint "eagle-import:R0603")
      (libsource (lib "eagle-import") (part "Labops_Lib_AH_R_0603"))
    )
    (comp (ref "R93")
      (value "10K 1%")
      (footprint "eagle-import:R0603")
      (libsource (lib "eagle-import") (part "Labops_Lib_AH_R_0603"))
    )
    (comp (ref "R94")
      (value "0R 1%")
      (footprint "eagle-import:R0603")
      (libsource (lib "eagle-import") (part "Labops_Lib_AH_R_0603"))
    )
    (comp (ref "U2")
      (value "R7FA6M5BG3CFBLQFP-144-M")
      (footprint "eagle-import:LQFP-144-M")
      (fields (field (name "MFR") "Renesas"))
      (libsource (lib "eagle-import") (part "R7FA6M5BG3CFBLQFP-144-M"))
    )
    (comp (ref "X2")
      (value "WF2549-2WS05S0B01")
      (footprint "eagle-import:X10_100MIL_2XROW_VERT")
      (fields (field (name "MFR") "WCON"))
      (libsource (lib "eagle-import") (part "WF2549-2WS05S0B01"))
    )
    (comp (ref "C3")
      (value "100nF/100V")
      (footprint "eagle-import:0603")
      (libsource (lib "eagle-import") (part "C_0603"))
    )
    (comp (ref "C4")
      (value "100nF/100V")
      (footprint "eagle-import:0603")
      (libsource (lib "eagle-import") (part "C_0603"))
    )
    (comp (ref "C5")
      (value "100nF/ 100V")
      (footprint "eagle-import:0603")
      (libsource (lib "eagle-import") (part "C_0603"))
    )
    (comp (ref "C12")
      (value "100nF/ 100V")
      (footprint "eagle-import:0603")
      (libsource (lib "eagle-import") (part "C_0603"))
    )
    (comp (ref "C13")
      (value "100nF/ 100V")
      (footprint "eagle-import:0603")
      (libsource (lib "eagle-import") (part "C_0603"))
    )
    (comp (ref "C14")
      (value "10uF/25V")
      (footprint "eagle-import:0603")
      (libsource (lib "eagle-import") (part "C_0603"))
    )
    (comp (ref "C15")
      (value "10uF/25V")
      (footprint "eagle-import:0603")
      (libsource (lib "eagle-import") (part "C_0603"))
    )
    (comp (ref "C16")
      (value "10uF/25V")
      (footprint "eagle-import:0603")
      (libsource (lib "eagle-import") (part "C_0603"))
    )
    (comp (ref "C17")
      (value "100nF/ 100V")
      (footprint "eagle-import:0603")
      (libsource (lib "eagle-import") (part "C_0603"))
    )
    (comp (ref "C18")
      (value "50PX470MEFC10X20")
      (footprint "eagle-import:CAPACITOR-ELKO-RM5-10X16")
      (fields (field (name "MFR") "Rubicon"))
      (libsource (lib "eagle-import") (part "50PX470MEFC10X20"))
    )
    (comp (ref "C19")
      (value "100nF/ 100V")
      (footprint "eagle-import:0603")
      (libsource (lib "eagle-import") (part "C_0603"))
    )
    (comp (ref "C20")
      (value "10uF/25V")
      (footprint "eagle-import:0603")
      (libsource (lib "eagle-import") (part "C_0603"))
    )
    (comp (ref "C21")
      (value "100nF/ 100V")
      (footprint "eagle-import:0603")
      (libsource (lib "eagle-import") (part "C_0603"))
    )
    (comp (ref "C22")
      (value "10uF/25V")
      (footprint "eagle-import:0603")
      (libsource (lib "eagle-import") (part "C_0603"))
    )
    (comp (ref "C23")
      (value "100nF/ 100V")
      (footprint "eagle-import:0603")
      (libsource (lib "eagle-import") (part "C_0603"))
    )
    (comp (ref "C24")
      (value "100nF/100V")
      (footprint "eagle-import:0603")
      (libsource (lib "eagle-import") (part "C_0603"))
    )
    (comp (ref "C25")
      (value "100nF/100V")
      (footprint "eagle-import:0603")
      (libsource (lib "eagle-import") (part "C_0603"))
    )
    (comp (ref "C36")
      (value "1uF/25V")
      (footprint "eagle-import:0603")
      (libsource (lib "eagle-import") (part "C_0603"))
    )
    (comp (ref "C37")
      (value "1uF/25V")
      (footprint "eagle-import:0603")
      (libsource (lib "eagle-import") (part "C_0603"))
    )
    (comp (ref "C38")
      (value "100nF/100V")
      (footprint "eagle-import:0603")
      (libsource (lib "eagle-import") (part "C_0603"))
    )
    (comp (ref "C39")
      (value "100nF/100V")
      (footprint "eagle-import:0603")
      (libsource (lib "eagle-import") (part "C_0603"))
    )
    (comp (ref "C49")
      (value "100nF/ 100V")
      (footprint "eagle-import:0603")
      (libsource (lib "eagle-import") (part "C_0603"))
    )
    (comp (ref "D3")
      (value "MMBZ4696-HE3-18")
      (footprint "eagle-import:SOT23-3")
      (fields (field (name "MFR") "Vishay"))
      (libsource (lib "eagle-import") (part "MMBZ4696-HE3-18"))
    )
    (comp (ref "D10")
      (value "BAS40-04,215")
      (footprint "eagle-import:SOT23-3")
      (fields (field (name "MFR") "NXP"))
      (libsource (lib "eagle-import") (part "BAS40-04,215"))
    )
    (comp (ref "D11")
      (value "SS14")
      (footprint "eagle-import:SMA")
      (fields (field (name "MFR") "MCC"))
      (libsource (lib "eagle-import") (part "SS14"))
    )
    (comp (ref "D12")
      (value "26-21/GPC-F3138B/CA")
      (footprint "eagle-import:SMD1206-LED")
      (fields (field (name "MFR") "Everlight"))
      (libsource (lib "eagle-import") (part "26-21/GPC-F3138B/CA"))
    )
    (comp (ref "D13")
      (value "BAS40-04,215")
      (footprint "eagle-import:SOT23-3")
      (fields (field (name "MFR") "NXP"))
      (libsource (lib "eagle-import") (part "BAS40-04,215"))
    )
    (comp (ref "FID1")
      (value "FIDUCIAL")
      (footprint "eagle-import:FIDUCIAL")
      (libsource (lib "eagle-import") (part "FIDUCIAL"))
    )
    (comp (ref "FID2")
      (value "FIDUCIAL")
      (footprint "eagle-import:FIDUCIAL")
      (libsource (lib "eagle-import") (part "FIDUCIAL"))
    )
    (comp (ref "H1")
      (value "MOUNT-PAD-ROUND3.0")
      (footprint "eagle-import:3,0-PAD")
      (libsource (lib "eagle-import") (part "MOUNT-PAD-ROUND3.0"))
    )
    (comp (ref "H2")
      (value "MOUNT-PAD-ROUND3.0")
      (footprint "eagle-import:3,0-PAD")
      (libsource (lib "eagle-import") (part "MOUNT-PAD-ROUND3.0"))
    )
    (comp (ref "H3")
      (value "MOUNT-PAD-ROUND3.0")
      (footprint "eagle-import:3,0-PAD")
      (libsource (lib "eagle-import") (part "MOUNT-PAD-ROUND3.0"))
    )
    (comp (ref "H4")
      (value "MOUNT-PAD-ROUND3.0")
      (footprint "eagle-import:3,0-PAD")
      (libsource (lib "eagle-import") (part "MOUNT-PAD-ROUND3.0"))
    )
    (comp (ref "IC1")
      (value "SN65HVD3082EDR")
      (footprint "eagle-import:SOIC8")
      (fields (field (name "MFR") "TI,3Peak"))
      (libsource (lib "eagle-import") (part "SN65HVD3082EDR"))
    )
    (comp (ref "IC5")
      (value "TPS54202DDCR")
      (footprint "eagle-import:SOT23-6")
      (fields (field (name "MFR") "Texas Instruments"))
      (libsource (lib "eagle-import") (part "TPS54202DDCR"))
    )
    (comp (ref "IC6")
      (value "LD1117S33TR")
      (footprint "eagle-import:SOT223_LD1117S33TR")
      (fields (field (name "MFR") "STmicro, Diodes, TI,"))
      (libsource (lib "eagle-import") (part "LD1117S33TR"))
    )
    (comp (ref "IC8")
      (value "LM317AEMP")
      (footprint "eagle-import:SOT223_LM317AEMP")
      (libsource (lib "eagle-import") (part "LM317AEMP"))
    )
    (comp (ref "J1")
      (value "ESP32-PICO-KIT")
      (footprint "eagle-import:XCVR_ESP32-PICO-KIT")
      (fields (field (name "MFR") "Espressif Systems"))
      (libsource (lib "eagle-import") (part "ESP32-PICO-KIT"))
    )
    (comp (ref "L1")
      (value "SRN8040TA-220M")
      (footprint "eagle-import:SRN8040TA-220M")
      (fields (field (name "MFR") "Bourns"))
      (libsource (lib "eagle-import") (part "SRN8040TA-220M"))
    )
    (comp (ref "Q5")
      (value "DMP6185SEQ-13")
      (footprint "eagle-import:SOT223")
      (fields (field (name "MFR") "Diodes"))
      (libsource (lib "eagle-import") (part "DMP6185SEQ-13"))
    )
    (comp (ref "Q10")
      (value "BC817")
      (footprint "eagle-import:SOT23")
      (fields (field (name "MFR") "NXP"))
      (libsource (lib "eagle-import") (part "BC817"))
    )
    (comp (ref "R14")
      (value "10K 1%")
      (footprint "eagle-import:R0603")
      (libsource (lib "eagle-import") (part "Labops_Lib_AH_R_0603"))
    )
    (comp (ref "R15")
      (value "1K 1%")
      (footprint "eagle-import:R0603")
      (libsource (lib "eagle-import") (part "Labops_Lib_AH_R_0603"))
    )
    (comp (ref "R16")
      (value "470R 1%")
      (footprint "eagle-import:R0603")
      (libsource (lib "eagle-import") (part "Labops_Lib_AH_R_0603"))
    )
    (comp (ref "R17")
      (value "10K 1%")
      (footprint "eagle-import:R0603")
      (libsource (lib "eagle-import") (part "Labops_Lib_AH_R_0603"))
    )
    (comp (ref "R40")
      (value "22K 1%")
      (footprint "eagle-import:R0603")
      (libsource (lib "eagle-import") (part "Labops_Lib_AH_R_0603"))
    )
    (comp (ref "R41")
      (value "2.8K 1%")
      (footprint "eagle-import:R0603")
      (libsource (lib "eagle-import") (part "Labops_Lib_AH_R_0603"))
    )
    (comp (ref "R42")
      (value "100R 1%")
      (footprint "eagle-import:R0603")
      (libsource (lib "eagle-import") (part "Labops_Lib_AH_R_0603"))
    )
    (comp (ref "R43")
      (value "22K 1%")
      (footprint "eagle-import:R0603")
      (libsource (lib "eagle-import") (part "Labops_Lib_AH_R_0603"))
    )
    (comp (ref "R44")
      (value "3K01 1%")
      (footprint "eagle-import:R0603")
      (libsource (lib "eagle-import") (part "Labops_Lib_AH_R_0603"))
    )
    (comp (ref "R45")
      (value "22K 1%")
      (footprint "eagle-import:R0603")
      (libsource (lib "eagle-import") (part "Labops_Lib_AH_R_0603"))
    )
    (comp (ref "R47")
      (value "470R 1%")
      (footprint "eagle-import:R0603")
      (libsource (lib "eagle-import") (part "Labops_Lib_AH_R_0603"))
    )
    (comp (ref "R48")
      (value "470R 1%")
      (footprint "eagle-import:R0603")
      (libsource (lib "eagle-import") (part "Labops_Lib_AH_R_0603"))
    )
    (comp (ref "R49")
      (value "100R 1%")
      (footprint "eagle-import:R0603")
      (libsource (lib "eagle-import") (part "Labops_Lib_AH_R_0603"))
    )
    (comp (ref "R50")
      (value "100R 1%")
      (footprint "eagle-import:R0603")
      (libsource (lib "eagle-import") (part "Labops_Lib_AH_R_0603"))
    )
    (comp (ref "R51")
      (value "100K 1%")
      (footprint "eagle-import:R1206")
      (libsource (lib "eagle-import") (part "R_1206"))
    )
    (comp (ref "R52")
      (value "100R 1%")
      (footprint "eagle-import:R0603")
      (libsource (lib "eagle-import") (part "Labops_Lib_AH_R_0603"))
    )
    (comp (ref "R53")
      (value "0R 1%")
      (footprint "eagle-import:R0603")
      (libsource (lib "eagle-import") (part "Labops_Lib_AH_R_0603"))
    )
    (comp (ref "R54")
      (value "1K 1%")
      (footprint "eagle-import:R1206")
      (libsource (lib "eagle-import") (part "R_1206"))
    )
    (comp (ref "R55")
      (value "0R 1%")
      (footprint "eagle-import:R0603")
      (libsource (lib "eagle-import") (part "Labops_Lib_AH_R_0603"))
    )
    (comp (ref "R83")
      (value "1K 1%")
      (footprint "eagle-import:R0603")
      (libsource (lib "eagle-import") (part "Labops_Lib_AH_R_0603"))
    )
    (comp (ref "R85")
      (value "0R 1%")
      (footprint "eagle-import:R1206")
      (libsource (lib "eagle-import") (part "R_1206"))
    )
    (comp (ref "R86")
      (value "82R 1%")
      (footprint "eagle-import:R1206")
      (libsource (lib "eagle-import") (part "R_1206"))
    )
    (comp (ref "R91")
      (value "1k 1%")
      (footprint "eagle-import:R0603")
      (libsource (lib "eagle-import") (part "Labops_Lib_AH_R_0603"))
    )
    (comp (ref "R92")
      (value "18K 1%")
      (footprint "eagle-import:R0603")
      (libsource (lib "eagle-import") (part "Labops_Lib_AH_R_0603"))
    )
    (comp (ref "R95")
      (value "470R 1%")
      (footprint "eagle-import:R0603")
      (libsource (lib "eagle-import") (part "Labops_Lib_AH_R_0603"))
    )
    (comp (ref "R96")
      (value "100R 1%")
      (footprint "eagle-import:R0603")
      (libsource (lib "eagle-import") (part "Labops_Lib_AH_R_0603"))
    )
    (comp (ref "R97")
      (value "100R 1%")
      (footprint "eagle-import:R0603")
      (libsource (lib "eagle-import") (part "Labops_Lib_AH_R_0603"))
    )
    (comp (ref "SW1")
      (value "L101011MS02Q")
      (footprint "eagle-import:L101011MS02Q")
      (fields (field (name "MFR") "C&K"))
      (libsource (lib "eagle-import") (part "L101011MS02Q"))
    )
    (comp (ref "V2")
      (value "0603ESDA-24N")
      (footprint "eagle-import:0603")
      (fields (field (name "MFR") "BORN"))
      (libsource (lib "eagle-import") (part "0603ESDA-24N"))
    )
    (comp (ref "V3")
      (value "0603ESDA-24N")
      (footprint "eagle-import:0603")
      (fields (field (name "MFR") "BORN"))
      (libsource (lib "eagle-import") (part "0603ESDA-24N"))
    )
    (comp (ref "C26")
      (value "100nF/50V")
      (footprint "eagle-import:0603")
      (libsource (lib "eagle-import") (part "C_0603"))
    )
    (comp (ref "C27")
      (value "100nF/50V")
      (footprint "eagle-import:0603")
      (libsource (lib "eagle-import") (part "C_0603"))
    )
    (comp (ref "C28")
      (value "100nF/50V")
      (footprint "eagle-import:0603")
      (libsource (lib "eagle-import") (part "C_0603"))
    )
    (comp (ref "C29")
      (value "100nF/50V")
      (footprint "eagle-import:0603")
      (libsource (lib "eagle-import") (part "C_0603"))
    )
    (comp (ref "C30")
      (value "100nF/50V")
      (footprint "eagle-import:0603")
      (libsource (lib "eagle-import") (part "C_0603"))
    )
    (comp (ref "C31")
      (value "100nF/50V")
      (footprint "eagle-import:0603")
      (libsource (lib "eagle-import") (part "C_0603"))
    )
    (comp (ref "C32")
      (value "100nF/50V")
      (footprint "eagle-import:0603")
      (libsource (lib "eagle-import") (part "C_0603"))
    )
    (comp (ref "C33")
      (value "100nF/50V")
      (footprint "eagle-import:0603")
      (libsource (lib "eagle-import") (part "C_0603"))
    )
    (comp (ref "C34")
      (value "100nF/50V")
      (footprint "eagle-import:0603")
      (libsource (lib "eagle-import") (part "C_0603"))
    )
    (comp (ref "C35")
      (value "100nF/50V")
      (footprint "eagle-import:0603")
      (libsource (lib "eagle-import") (part "C_0603"))
    )
    (comp (ref "Q11")
      (value "2N7002")
      (footprint "eagle-import:SOT23")
      (fields (field (name "MFR") "Diodes, Guangdong Hotetech,NXP"))
      (libsource (lib "eagle-import") (part "2N7002"))
    )
    (comp (ref "Q12")
      (value "UT2955G-AA3-R")
      (footprint "eagle-import:SOT223")
      (fields (field (name "MFR") "UTC"))
      (libsource (lib "eagle-import") (part "UT2955G-AA3-R"))
    )
    (comp (ref "Q13")
      (value "2N7002")
      (footprint "eagle-import:SOT23")
      (fields (field (name "MFR") "Diodes, Guangdong Hotetech,NXP"))
      (libsource (lib "eagle-import") (part "2N7002"))
    )
    (comp (ref "Q14")
      (value "UT2955G-AA3-R")
      (footprint "eagle-import:SOT223")
      (fields (field (name "MFR") "UTC"))
      (libsource (lib "eagle-import") (part "UT2955G-AA3-R"))
    )
    (comp (ref "Q15")
      (value "2N7002")
      (footprint "eagle-import:SOT23")
      (fields (field (name "MFR") "Diodes, Guangdong Hotetech,NXP"))
      (libsource (lib "eagle-import") (part "2N7002"))
    )
    (comp (ref "Q16")
      (value "UT2955G-AA3-R")
      (footprint "eagle-import:SOT223")
      (fields (field (name "MFR") "UTC"))
      (libsource (lib "eagle-import") (part "UT2955G-AA3-R"))
    )
    (comp (ref "Q17")
      (value "BC817")
      (footprint "eagle-import:SOT23")
      (fields (field (name "MFR") "NXP"))
      (libsource (lib "eagle-import") (part "BC817"))
    )
    (comp (ref "Q18")
      (value "BC817")
      (footprint "eagle-import:SOT23")
      (fields (field (name "MFR") "NXP"))
      (libsource (lib "eagle-import") (part "BC817"))
    )
    (comp (ref "Q19")
      (value "BC817")
      (footprint "eagle-import:SOT23")
      (fields (field (name "MFR") "NXP"))
      (libsource (lib "eagle-import") (part "BC817"))
    )
    (comp (ref "Q20")
      (value "BC817")
      (footprint "eagle-import:SOT23")
      (fields (field (name "MFR") "NXP"))
      (libsource (lib "eagle-import") (part "BC817"))
    )
    (comp (ref "Q21")
      (value "BC817")
      (footprint "eagle-import:SOT23")
      (fields (field (name "MFR") "NXP"))
      (libsource (lib "eagle-import") (part "BC817"))
    )
    (comp (ref "Q22")
      (value "BC817")
      (footprint "eagle-import:SOT23")
      (fields (field (name "MFR") "NXP"))
      (libsource (lib "eagle-import") (part "BC817"))
    )
    (comp (ref "Q23")
      (value "BC817")
      (footprint "eagle-import:SOT23")
      (fields (field (name "MFR") "NXP"))
      (libsource (lib "eagle-import") (part "BC817"))
    )
    (comp (ref "R56")
      (value "100R 1%")
      (footprint "eagle-import:R0603")
      (libsource (lib "eagle-import") (part "Labops_Lib_AH_R_0603"))
    )
    (comp (ref "R57")
      (value "10K 1%")
      (footprint "eagle-import:R0603")
      (libsource (lib "eagle-import") (part "Labops_Lib_AH_R_0603"))
    )
    (comp (ref "R58")
      (value "100R 1%")
      (footprint "eagle-import:R0603")
      (libsource (lib "eagle-import") (part "Labops_Lib_AH_R_0603"))
    )
    (comp (ref "R59")
      (value "10K 1%")
      (footprint "eagle-import:R0603")
      (libsource (lib "eagle-import") (part "Labops_Lib_AH_R_0603"))
    )
    (comp (ref "R60")
      (value "100R 1%")
      (footprint "eagle-import:R0603")
      (libsource (lib "eagle-import") (part "Labops_Lib_AH_R_0603"))
    )
    (comp (ref "R61")
      (value "10K 1%")
      (footprint "eagle-import:R0603")
      (libsource (lib "eagle-import") (part "Labops_Lib_AH_R_0603"))
    )
    (comp (ref "R62")
      (value "100R 1%")
      (footprint "eagle-import:R0603")
      (libsource (lib "eagle-import") (part "Labops_Lib_AH_R_0603"))
    )
    (comp (ref "R63")
      (value "10K 1%")
      (footprint "eagle-import:R0603")
      (libsource (lib "eagle-import") (part "Labops_Lib_AH_R_0603"))
    )
    (comp (ref "R64")
      (value "100R 1%")
      (footprint "eagle-import:R0603")
      (libsource (lib "eagle-import") (part "Labops_Lib_AH_R_0603"))
    )
    (comp (ref "R65")
      (value "10K 1%")
      (footprint "eagle-import:R0603")
      (libsource (lib "eagle-import") (part "Labops_Lib_AH_R_0603"))
    )
    (comp (ref "R66")
      (value "100R 1%")
      (footprint "eagle-import:R0603")
      (libsource (lib "eagle-import") (part "Labops_Lib_AH_R_0603"))
    )
    (comp (ref "R67")
      (value "10K 1%")
      (footprint "eagle-import:R0603")
      (libsource (lib "eagle-import") (part "Labops_Lib_AH_R_0603"))
    )
    (comp (ref "R68")
      (value "0R 1%")
      (footprint "eagle-import:R0603")
      (libsource (lib "eagle-import") (part "Labops_Lib_AH_R_0603"))
    )
    (comp (ref "R69")
      (value "470R 1%")
      (footprint "eagle-import:R0603")
      (libsource (lib "eagle-import") (part "Labops_Lib_AH_R_0603"))
    )
    (comp (ref "R70")
      (value "100R 1%")
      (footprint "eagle-import:R0603")
      (libsource (lib "eagle-import") (part "Labops_Lib_AH_R_0603"))
    )
    (comp (ref "R71")
      (value "470R 1%")
      (footprint "eagle-import:R0603")
      (libsource (lib "eagle-import") (part "Labops_Lib_AH_R_0603"))
    )
    (comp (ref "R72")
      (value "100R 1%")
      (footprint "eagle-import:R0603")
      (libsource (lib "eagle-import") (part "Labops_Lib_AH_R_0603"))
    )
    (comp (ref "R73")
      (value "470R 1%")
      (footprint "eagle-import:R0603")
      (libsource (lib "eagle-import") (part "Labops_Lib_AH_R_0603"))
    )
    (comp (ref "R74")
      (value "100R 1%")
      (footprint "eagle-import:R0603")
      (libsource (lib "eagle-import") (part "Labops_Lib_AH_R_0603"))
    )
    (comp (ref "R75")
      (value "470R 1%")
      (footprint "eagle-import:R0603")
      (libsource (lib "eagle-import") (part "Labops_Lib_AH_R_0603"))
    )
    (comp (ref "R76")
      (value "100R 1%")
      (footprint "eagle-import:R0603")
      (libsource (lib "eagle-import") (part "Labops_Lib_AH_R_0603"))
    )
    (comp (ref "R77")
      (value "470R 1%")
      (footprint "eagle-import:R0603")
      (libsource (lib "eagle-import") (part "Labops_Lib_AH_R_0603"))
    )
    (comp (ref "R78")
      (value "100R 1%")
      (footprint "eagle-import:R0603")
      (libsource (lib "eagle-import") (part "Labops_Lib_AH_R_0603"))
    )
    (comp (ref "R79")
      (value "470R 1%")
      (footprint "eagle-import:R0603")
      (libsource (lib "eagle-import") (part "Labops_Lib_AH_R_0603"))
    )
    (comp (ref "R80")
      (value "100R 1%")
      (footprint "eagle-import:R0603")
      (libsource (lib "eagle-import") (part "Labops_Lib_AH_R_0603"))
    )
    (comp (ref "R81")
      (value "470R 1%")
      (footprint "eagle-import:R0603")
      (libsource (lib "eagle-import") (part "Labops_Lib_AH_R_0603"))
    )
    (comp (ref "R82")
      (value "100R 1%")
      (footprint "eagle-import:R0603")
      (libsource (lib "eagle-import") (part "Labops_Lib_AH_R_0603"))
    )
    (comp (ref "R87")
      (value "100R 1%")
      (footprint "eagle-import:R0603")
      (libsource (lib "eagle-import") (part "Labops_Lib_AH_R_0603"))
    )
    (comp (ref "R88")
      (value "100R 1%")
      (footprint "eagle-import:R0603")
      (libsource (lib "eagle-import") (part "Labops_Lib_AH_R_0603"))
    )
    (comp (ref "R89")
      (value "100R 1%")
      (footprint "eagle-import:R0603")
      (libsource (lib "eagle-import") (part "Labops_Lib_AH_R_0603"))
    )
    (comp (ref "R90")
      (value "100R 1%")
      (footprint "eagle-import:R0603")
      (libsource (lib "eagle-import") (part "Labops_Lib_AH_R_0603"))
    )
    (comp (ref "V6")
      (value "0603ESDA-24N")
      (footprint "eagle-import:0603")
      (fields (field (name "MFR") "BORN"))
      (libsource (lib "eagle-import") (part "0603ESDA-24N"))
    )
    (comp (ref "V7")
      (value "0603ESDA-24N")
      (footprint "eagle-import:0603")
      (fields (field (name "MFR") "BORN"))
      (libsource (lib "eagle-import") (part "0603ESDA-24N"))
    )
    (comp (ref "V8")
      (value "0603ESDA-24N")
      (footprint "eagle-import:0603")
      (fields (field (name "MFR") "BORN"))
      (libsource (lib "eagle-import") (part "0603ESDA-24N"))
    )
    (comp (ref "X13")
      (value "MICROMATCH-16")
      (footprint "eagle-import:MICROMATCH-16")
      (fields (field (name "MF") "FARNELL") (field (name "MPN") "8-215464-6"))
      (libsource (lib "eagle-import") (part "MICROMATCH-16"))
    )
    (comp (ref "X1")
      (value "B2B-XH-AM(LF)(SN)")
      (footprint "eagle-import:B2B-XH-AM(LF)(SN)")
      (fields (field (name "MFR") "JST"))
      (libsource (lib "eagle-import") (part "B2B-XH-AM(LF)(SN)"))
    )
    (comp (ref "X3")
      (value "282834-3")
      (footprint "eagle-import:TE_282834-3_0")
      (fields (field (name "MFR") "TE"))
      (libsource (lib "eagle-import") (part "282834-3"))
    )
    (comp (ref "X4")
      (value "282834-3")
      (footprint "eagle-import:TE_282834-3_0")
      (fields (field (name "MFR") "TE"))
      (libsource (lib "eagle-import") (part "282834-3"))
    )
    (comp (ref "X5")
      (value "726386-2TE_726386-2")
      (footprint "eagle-import:TE_726386-2")
      (fields
        (field (name "DIGIKEY_PART_NUMBER") "A114371-ND")
        (field (name "MF") "TE")
        (field (name "MOUSER_PART_NUMBER") "571-726386-2")
      )
      (libsource (lib "eagle-import") (part "726386-2TE_726386-2"))
    )
    (comp (ref "X6")
      (value "726386-2TE_726386-2")
      (footprint "eagle-import:TE_726386-2")
      (fields
        (field (name "DIGIKEY_PART_NUMBER") "A114371-ND")
        (field (name "MF") "TE")
        (field (name "MOUSER_PART_NUMBER") "571-726386-2")
      )
      (libsource (lib "eagle-import") (part "726386-2TE_726386-2"))
    )
    (comp (ref "X7")
      (value "726386-2TE_726386-2")
      (footprint "eagle-import:TE_726386-2")
      (fields
        (field (name "DIGIKEY_PART_NUMBER") "A114371-ND")
        (field (name "MF") "TE")
        (field (name "MOUSER_PART_NUMBER") "571-726386-2")
      )
      (libsource (lib "eagle-import") (part "726386-2TE_726386-2"))
    )
    (comp (ref "X8")
      (value "726386-2TE_726386-2")
      (footprint "eagle-import:TE_726386-2")
      (fields
        (field (name "DIGIKEY_PART_NUMBER") "A114371-ND")
        (field (name "MF") "TE")
        (field (name "MOUSER_PART_NUMBER") "571-726386-2")
      )
      (libsource (lib "eagle-import") (part "726386-2TE_726386-2"))
    )
    (comp (ref "X9")
      (value "726386-2TE_726386-2")
      (footprint "eagle-import:TE_726386-2")
      (fields
        (field (name "DIGIKEY_PART_NUMBER") "A114371-ND")
        (field (name "MF") "TE")
        (field (name "MOUSER_PART_NUMBER") "571-726386-2")
      )
      (libsource (lib "eagle-import") (part "726386-2TE_726386-2"))
    )
    (comp (ref "X10")
      (value "726386-2TE_726386-2")
      (footprint "eagle-import:TE_726386-2")
      (fields
        (field (name "DIGIKEY_PART_NUMBER") "A114371-ND")
        (field (name "MF") "TE")
        (field (name "MOUSER_PART_NUMBER") "571-726386-2")
      )
      (libsource (lib "eagle-import") (part "726386-2TE_726386-2"))
    )
    (comp (ref "X11")
      (value "282834-2")
      (footprint "eagle-import:TE_282834-2_0")
      (fields (field (name "MFR") "TE"))
      (libsource (lib "eagle-import") (part "282834-2"))
    )
    (comp (ref "X12")
      (value "615008148521")
      (footprint "eagle-import:615008148521")
      (fields (field (name "MFR") "Wurth Elektronik"))
      (libsource (lib "eagle-import") (part "615008148521"))
    )
    (comp (ref "X14")
      (value "615008148521")
      (footprint "eagle-import:615008148521")
      (fields (field (name "MFR") "Wurth Elektronik"))
      (libsource (lib "eagle-import") (part "615008148521"))
    )
    (comp (ref "C7")
      (value "100nF/100V")
      (footprint "eagle-import:0603")
      (libsource (lib "eagle-import") (part "C_0603"))
    )
    (comp (ref "C8")
      (value "100nF/100V")
      (footprint "eagle-import:0603")
      (fields (field (name "PART_VALUE") "100nF/100V"))
      (libsource (lib "eagle-import") (part "C_0603"))
    )
    (comp (ref "C9")
      (value "100nF/100V")
      (footprint "eagle-import:0603")
      (fields (field (name "PART_VALUE") "100nF/100V"))
      (libsource (lib "eagle-import") (part "C_0603"))
    )
    (comp (ref "D2")
      (value "SS14")
      (footprint "eagle-import:SMA")
      (fields (field (name "MFR") "MCC"))
      (libsource (lib "eagle-import") (part "SS14"))
    )
    (comp (ref "D6")
      (value "PESD36VS2UT")
      (footprint "eagle-import:SOT23-3")
      (fields (field (name "MFR") "NXP"))
      (libsource (lib "eagle-import") (part "PESD36VS2UT"))
    )
    (comp (ref "D7")
      (value "BAS40-04,215")
      (footprint "eagle-import:SOT23-3")
      (fields (field (name "MFR") "NXP"))
      (libsource (lib "eagle-import") (part "BAS40-04,215"))
    )
    (comp (ref "D8")
      (value "BAS40-04,215")
      (footprint "eagle-import:SOT23-3")
      (fields (field (name "MFR") "NXP"))
      (libsource (lib "eagle-import") (part "BAS40-04,215"))
    )
    (comp (ref "D15")
      (value "MMBZ4696-HE3-18")
      (footprint "eagle-import:SOT23-3")
      (fields (field (name "MFR") "Vishay"))
      (libsource (lib "eagle-import") (part "MMBZ4696-HE3-18"))
    )
    (comp (ref "D16")
      (value "MMBZ4696-HE3-18")
      (footprint "eagle-import:SOT23-3")
      (fields (field (name "MFR") "Vishay"))
      (libsource (lib "eagle-import") (part "MMBZ4696-HE3-18"))
    )
    (comp (ref "IC3")
      (value "LT6106CS5#TRPBF")
      (footprint "eagle-import:SOT-23-5")
      (fields (field (name "MFR") "Analog Devices"))
      (libsource (lib "eagle-import") (part "LT6106CS5#TRPBF"))
    )
    (comp (ref "K3")
      (value "RP1A48D6")
      (footprint "eagle-import:SSR_RP1A")
      (libsource (lib "eagle-import") (part "RP1A48D6"))
    )
    (comp (ref "Q3")
      (value "UT2955G-AA3-R")
      (footprint "eagle-import:SOT223")
      (fields (field (name "MFR") "UTC"))
      (libsource (lib "eagle-import") (part "UT2955G-AA3-R"))
    )
    (comp (ref "Q4")
      (value "2N7002")
      (footprint "eagle-import:SOT23")
      (fields (field (name "MFR") "Diodes, Guangdong Hotetech,NXP"))
      (libsource (lib "eagle-import") (part "2N7002"))
    )
    (comp (ref "Q6")
      (value "UT2955G-AA3-R")
      (footprint "eagle-import:SOT223")
      (fields (field (name "MFR") "UTC"))
      (libsource (lib "eagle-import") (part "UT2955G-AA3-R"))
    )
    (comp (ref "Q7")
      (value "2N7002")
      (footprint "eagle-import:SOT23")
      (fields (field (name "MFR") "Diodes, Guangdong Hotetech,NXP"))
      (libsource (lib "eagle-import") (part "2N7002"))
    )
    (comp (ref "R9")
      (value "10K 1%")
      (footprint "eagle-import:0603")
      (libsource (lib "eagle-import") (part "R_0603"))
    )
    (comp (ref "R10")
      (value "10K 1%")
      (footprint "eagle-import:0603")
      (libsource (lib "eagle-import") (part "R_0603"))
    )
    (comp (ref "R11")
      (value "10K 1%")
      (footprint "eagle-import:0603")
      (libsource (lib "eagle-import") (part "R_0603"))
    )
    (comp (ref "R12")
      (value "10K 1%")
      (footprint "eagle-import:0603")
      (libsource (lib "eagle-import") (part "R_0603"))
    )
    (comp (ref "R13")
      (value "100R 1%")
      (footprint "eagle-import:0603")
      (libsource (lib "eagle-import") (part "R_0603"))
    )
    (comp (ref "R21")
      (value "100R 1%")
      (footprint "eagle-import:R1206")
      (libsource (lib "eagle-import") (part "R_1206"))
    )
    (comp (ref "R22")
      (value "1K 1%")
      (footprint "eagle-import:R0603")
      (libsource (lib "eagle-import") (part "Labops_Lib_AH_R_0603"))
    )
    (comp (ref "R23")
      (value "100K 1%")
      (footprint "eagle-import:R0603")
      (libsource (lib "eagle-import") (part "Labops_Lib_AH_R_0603"))
    )
    (comp (ref "R24")
      (value "10K 1%")
      (footprint "eagle-import:0603")
      (libsource (lib "eagle-import") (part "R_0603"))
    )
    (comp (ref "R25")
      (value "10K 1%")
      (footprint "eagle-import:0603")
      (libsource (lib "eagle-import") (part "R_0603"))
    )
    (comp (ref "R26")
      (value "10K 1%")
      (footprint "eagle-import:0603")
      (libsource (lib "eagle-import") (part "R_0603"))
    )
    (comp (ref "R27")
      (value "100R 1%")
      (footprint "eagle-import:0603")
      (libsource (lib "eagle-import") (part "R_0603"))
    )
    (comp (ref "R28")
      (value "R_2010")
      (footprint "eagle-import:R2010")
      (fields (field (name "MFN") "RL73K2HR68JTE") (field (name "PART_VALUE") "680mR"))
      (libsource (lib "eagle-import") (part "R_2010"))
    )
    (comp (ref "R29")
      (value "2.2K 1%")
      (footprint "eagle-import:0603")
      (libsource (lib "eagle-import") (part "R_0603"))
    )
    (comp (ref "R30")
      (value "100R 1%")
      (footprint "eagle-import:0603")
      (libsource (lib "eagle-import") (part "R_0603"))
    )
    (comp (ref "R31")
      (value "100R 1%")
      (footprint "eagle-import:0603")
      (libsource (lib "eagle-import") (part "R_0603"))
    )
    (comp (ref "V5")
      (value "B72205S0271K1011")
      (footprint "eagle-import:EPCOS_B72205S0271K101_MODIFIED")
      (libsource (lib "eagle-import") (part "B72205S0271K1011"))
    )
    (comp (ref "C1")
      (value "R49AN347050B1M")
      (footprint "eagle-import:R49AN347050B1M")
      (fields (field (name "MFR") "Kemet"))
      (libsource (lib "eagle-import") (part "R49AN347050B1M"))
    )
    (comp (ref "C2")
      (value "ERP610W471MEF0")
      (footprint "eagle-import:CAP-P12.5-H15-W4-D1")
      (fields (field (name "MFR") "Kemet"))
      (libsource (lib "eagle-import") (part "ERP610W471MEF0"))
    )
    (comp (ref "C6")
      (value "100nF/100V")
      (footprint "eagle-import:0603")
      (libsource (lib "eagle-import") (part "C_0603"))
    )
    (comp (ref "C10")
      (value "100nF/100V")
      (footprint "eagle-import:0603")
      (fields (field (name "PART_VALUE") "100nF/100V"))
      (libsource (lib "eagle-import") (part "C_0603"))
    )
    (comp (ref "C11")
      (value "100nF/100V")
      (footprint "eagle-import:0603")
      (fields (field (name "PART_VALUE") "100nF/100V"))
      (libsource (lib "eagle-import") (part "C_0603"))
    )
    (comp (ref "D1")
      (value "SS14")
      (footprint "eagle-import:SMA")
      (fields (field (name "MFR") "MCC"))
      (libsource (lib "eagle-import") (part "SS14"))
    )
    (comp (ref "D4")
      (value "PESD36VS2UT")
      (footprint "eagle-import:SOT23-3")
      (fields (field (name "MFR") "NXP"))
      (libsource (lib "eagle-import") (part "PESD36VS2UT"))
    )
    (comp (ref "D5")
      (value "BAS40-04,215")
      (footprint "eagle-import:SOT23-3")
      (fields (field (name "MFR") "NXP"))
      (libsource (lib "eagle-import") (part "BAS40-04,215"))
    )
    (comp (ref "D9")
      (value "BAS40-04,215")
      (footprint "eagle-import:SOT23-3")
      (fields (field (name "MFR") "NXP"))
      (libsource (lib "eagle-import") (part "BAS40-04,215"))
    )
    (comp (ref "D14")
      (value "MMBZ4696-HE3-18")
      (footprint "eagle-import:SOT23-3")
      (fields (field (name "MFR") "Vishay"))
      (libsource (lib "eagle-import") (part "MMBZ4696-HE3-18"))
    )
    (comp (ref "D17")
      (value "MMBZ4696-HE3-18")
      (footprint "eagle-import:SOT23-3")
      (fields (field (name "MFR") "Vishay"))
      (libsource (lib "eagle-import") (part "MMBZ4696-HE3-18"))
    )
    (comp (ref "F1")
      (value "696101000002")
      (footprint "eagle-import:FUSE_RM22.6")
      (fields (field (name "MFR") "Wurth Elektronik"))
      (libsource (lib "eagle-import") (part "696101000002"))
    )
    (comp (ref "IC4")
      (value "LT6106CS5#TRPBF")
      (footprint "eagle-import:SOT-23-5")
      (fields (field (name "MFR") "Analog Devices"))
      (libsource (lib "eagle-import") (part "LT6106CS5#TRPBF"))
    )
    (comp (ref "K1")
      (value "RP1A48D6")
      (footprint "eagle-import:SSR_RP1A")
      (libsource (lib "eagle-import") (part "RP1A48D6"))
    )
    (comp (ref "Q1")
      (value "UT2955G-AA3-R")
      (footprint "eagle-import:SOT223")
      (fields (field (name "MFR") "UTC"))
      (libsource (lib "eagle-import") (part "UT2955G-AA3-R"))
    )
    (comp (ref "Q2")
      (value "2N7002")
      (footprint "eagle-import:SOT23")
      (fields (field (name "MFR") "Diodes, Guangdong Hotetech,NXP"))
      (libsource (lib "eagle-import") (part "2N7002"))
    )
    (comp (ref "Q8")
      (value "UT2955G-AA3-R")
      (footprint "eagle-import:SOT223")
      (fields (field (name "MFR") "UTC"))
      (libsource (lib "eagle-import") (part "UT2955G-AA3-R"))
    )
    (comp (ref "Q9")
      (value "2N7002")
      (footprint "eagle-import:SOT23")
      (fields (field (name "MFR") "Diodes, Guangdong Hotetech,NXP"))
      (libsource (lib "eagle-import") (part "2N7002"))
    )
    (comp (ref "R1")
      (value "10K 1%")
      (footprint "eagle-import:0603")
      (libsource (lib "eagle-import") (part "R_0603"))
    )
    (comp (ref "R2")
      (value "10K 1%")
      (footprint "eagle-import:0603")
      (libsource (lib "eagle-import") (part "R_0603"))
    )
    (comp (ref "R3")
      (value "10K 1%")
      (footprint "eagle-import:0603")
      (libsource (lib "eagle-import") (part "R_0603"))
    )
    (comp (ref "R4")
      (value "10K 1%")
      (footprint "eagle-import:0603")
      (libsource (lib "eagle-import") (part "R_0603"))
    )
    (comp (ref "R5")
      (value "100R 1%")
      (footprint "eagle-import:0603")
      (libsource (lib "eagle-import") (part "R_0603"))
    )
    (comp (ref "R6")
      (value "220K 1%")
      (footprint "eagle-import:R2010")
      (libsource (lib "eagle-import") (part "R_2010"))
    )
    (comp (ref "R7")
      (value "220K 1%")
      (footprint "eagle-import:R2010")
      (libsource (lib "eagle-import") (part "R_2010"))
    )
    (comp (ref "R8")
      (value "RNF12FTD10M0")
      (footprint "eagle-import:RES-RM12.5-VR37")
      (fields (field (name "MFR") "Stackpole Electronics Inc"))
      (libsource (lib "eagle-import") (part "RNF12FTD10M0"))
    )
    (comp (ref "R18")
      (value "100R 1%")
      (footprint "eagle-import:R1206")
      (libsource (lib "eagle-import") (part "R_1206"))
    )
    (comp (ref "R19")
      (value "1K 1%")
      (footprint "eagle-import:R0603")
      (libsource (lib "eagle-import") (part "Labops_Lib_AH_R_0603"))
    )
    (comp (ref "R20")
      (value "100K 1%")
      (footprint "eagle-import:R0603")
      (libsource (lib "eagle-import") (part "Labops_Lib_AH_R_0603"))
    )
    (comp (ref "R32")
      (value "10K 1%")
      (footprint "eagle-import:0603")
      (libsource (lib "eagle-import") (part "R_0603"))
    )
    (comp (ref "R33")
      (value "10K 1%")
      (footprint "eagle-import:0603")
      (libsource (lib "eagle-import") (part "R_0603"))
    )
    (comp (ref "R34")
      (value "10K 1%")
      (footprint "eagle-import:0603")
      (libsource (lib "eagle-import") (part "R_0603"))
    )
    (comp (ref "R35")
      (value "100R 1%")
      (footprint "eagle-import:0603")
      (libsource (lib "eagle-import") (part "R_0603"))
    )
    (comp (ref "R36")
      (value "R_2010")
      (footprint "eagle-import:R2010")
      (fields (field (name "MFN") "RL73K2HR68JTE") (field (name "PART_VALUE") "680mR"))
      (libsource (lib "eagle-import") (part "R_2010"))
    )
    (comp (ref "R37")
      (value "2.2K 1%")
      (footprint "eagle-import:0603")
      (libsource (lib "eagle-import") (part "R_0603"))
    )
    (comp (ref "R38")
      (value "100R 1%")
      (footprint "eagle-import:0603")
      (libsource (lib "eagle-import") (part "R_0603"))
    )
    (comp (ref "R39")
      (value "100R 1%")
      (footprint "eagle-import:0603")
      (libsource (lib "eagle-import") (part "R_0603"))
    )
    (comp (ref "R46")
      (value "RNF12FTD10M0")
      (footprint "eagle-import:RES-RM12.5-VR37")
      (fields (field (name "MFR") "Stackpole Electronics Inc"))
      (libsource (lib "eagle-import") (part "RNF12FTD10M0"))
    )
    (comp (ref "V1")
      (value "B72205S0271K101B72205S2131K101")
      (footprint "eagle-import:EPCOS_B72205S0271K101_0")
      (fields (field (name "MFR") "EPCOS"))
      (libsource (lib "eagle-import") (part "B72205S0271K101B72205S2131K101"))
    )
    (comp (ref "V4")
      (value "B72205S0271K101B72205S2131K101")
      (footprint "eagle-import:EPCOS_B72205S0271K101_0")
      (fields (field (name "MFR") "EPCOS"))
      (libsource (lib "eagle-import") (part "B72205S0271K101B72205S2131K101"))
    )
  )
  (nets
    (net (code "1") (name "AI_24V0") (class "Default")
      (node (ref "C19") (pin "1") (pinfunction "1_1") (pintype "passive"))
      (node (ref "D10") (pin "3") (pinfunction "C1_A2_3") (pintype "passive"))
      (node (ref "R42") (pin "1") (pinfunction "1_1") (pintype "passive"))
      (node (ref "U2") (pin "115") (pinfunction "P502_115") (pintype "bidirectional"))
    )
    (net (code "2") (name "AI_I_SENSE_CONDUTIV_SENSOR") (class "Default")
      (node (ref "C9") (pin "1") (pinfunction "1_1") (pintype "passive"))
      (node (ref "D8") (pin "3") (pinfunction "C1_A2_3") (pintype "passive"))
      (node (ref "R30") (pin "2") (pinfunction "2_2") (pintype "passive"))
      (node (ref "U2") (pin "116") (pinfunction "P503_116") (pintype "bidirectional"))
    )
    (net (code "3") (name "AI_I_SENSE_PH_SENSOR") (class "Default")
      (node (ref "C11") (pin "1") (pinfunction "1_1") (pintype "passive"))
      (node (ref "D9") (pin "3") (pinfunction "C1_A2_3") (pintype "passive"))
      (node (ref "R38") (pin "2") (pinfunction "2_2") (pintype "passive"))
      (node (ref "U2") (pin "113") (pinfunction "P500_113") (pintype "bidirectional"))
    )
    (net (code "4") (name "AI_V_CONDUCTIV_SENSOR") (class "Default")
      (node (ref "D7") (pin "3") (pinfunction "C1_A2_3") (pintype "passive"))
      (node (ref "R22") (pin "1") (pinfunction "1_1") (pintype "passive"))
      (node (ref "R23") (pin "2") (pinfunction "2_2") (pintype "passive"))
      (node (ref "U2") (pin "117") (pinfunction "P504_117") (pintype "bidirectional"))
    )
    (net (code "5") (name "AI_V_PH_SENSOR") (class "Default")
      (node (ref "D5") (pin "3") (pinfunction "C1_A2_3") (pintype "passive"))
      (node (ref "R19") (pin "1") (pinfunction "1_1") (pintype "passive"))
      (node (ref "R20") (pin "2") (pinfunction "2_2") (pintype "passive"))
      (node (ref "U2") (pin "114") (pinfunction "P501_114") (pintype "bidirectional"))
    )
    (net (code "6") (name "CONDUCTIV_PUMP_MAINS_L_SW") (class "Default")
      (node (ref "K3") (pin "P$3") (pinfunction "3_P$3") (pintype "passive"))
      (node (ref "V5") (pin "2") (pinfunction "2_2") (pintype "passive"))
      (node (ref "X9") (pin "1") (pinfunction "1_1") (pintype "passive"))
      (node (ref "X9") (pin "1-2") (pinfunction "1_1-2") (pintype "passive"))
    )
    (net (code "7") (name "DBG_SWCLK") (class "Default")
      (node (ref "U2") (pin "72") (pinfunction "P300/TCK/SWCLK_72") (pintype "bidirectional"))
      (node (ref "X2") (pin "4") (pinfunction "4_4") (pintype "bidirectional"))
    )
    (net (code "8") (name "DBG_SWDIO") (class "Default")
      (node (ref "U2") (pin "73") (pinfunction "P108/TMS/SWDIO_73") (pintype "bidirectional"))
      (node (ref "X2") (pin "2") (pinfunction "2_2") (pintype "bidirectional"))
    )
    (net (code "9") (name "DBG_SWO") (class "Default")
      (node (ref "U2") (pin "74") (pinfunction "P109/TDO_74") (pintype "bidirectional"))
      (node (ref "X2") (pin "6") (pinfunction "6_6") (pintype "bidirectional"))
    )
    (net (code "10") (name "DI_DOSING_EN") (class "Default")
      (node (ref "D13") (pin "3") (pinfunction "C1_A2_3") (pintype "passive"))
      (node (ref "R52") (pin "1") (pinfunction "1_1") (pintype "passive"))
      (node (ref "R54") (pin "1") (pinfunction "1_1") (pintype "passive"))
      (node (ref "U2") (pin "31") (pinfunction "P412_31") (pintype "bidirectional"))
    )
    (net (code "11") (name "DI_UART_RX_ESP32") (class "Default")
      (node (ref "R96") (pin "1") (pinfunction "1_1") (pintype "passive"))
      (node (ref "U2") (pin "71") (pinfunction "P301_71") (pintype "bidirectional"))
    )
    (net (code "12") (name "DI_USART_RX") (class "Default")
      (node (ref "R95") (pin "2") (pinfunction "2_2") (pintype "passive"))
      (node (ref "U2") (pin "35") (pinfunction "P408_35") (pintype "bidirectional"))
    )
    (net (code "13") (name "DO_7XSEGMENT_1_EN") (class "Default")
      (node (ref "R60") (pin "1") (pinfunction "1_1") (pintype "passive"))
      (node (ref "U2") (pin "3") (pinfunction "P402_3") (pintype "bidirectional"))
    )
    (net (code "14") (name "DO_7XSEGMENT_2_EN") (class "Default")
      (node (ref "R64") (pin "1") (pinfunction "1_1") (pintype "passive"))
      (node (ref "U2") (pin "2") (pinfunction "P401_2") (pintype "bidirectional"))
    )
    (net (code "15") (name "DO_7XSEGMENT_3_EN") (class "Default")
      (node (ref "R56") (pin "1") (pinfunction "1_1") (pintype "passive"))
      (node (ref "U2") (pin "1") (pinfunction "P400_1") (pintype "bidirectional"))
    )
    (net (code "16") (name "DO_BCD_A") (class "Default")
      (node (ref "R87") (pin "2") (pinfunction "2_2") (pintype "passive"))
      (node (ref "U2") (pin "106") (pinfunction "P102_106") (pintype "bidirectional"))
    )
    (net (code "17") (name "DO_BCD_B") (class "Default")
      (node (ref "R88") (pin "2") (pinfunction "2_2") (pintype "passive"))
      (node (ref "U2") (pin "105") (pinfunction "P103_105") (pintype "bidirectional"))
    )
    (net (code "18") (name "DO_BCD_C") (class "Default")
      (node (ref "R89") (pin "2") (pinfunction "2_2") (pintype "passive"))
      (node (ref "U2") (pin "104") (pinfunction "P104_104") (pintype "bidirectional"))
    )
    (net (code "19") (name "DO_BCD_D") (class "Default")
      (node (ref "R90") (pin "2") (pinfunction "2_2") (pintype "passive"))
      (node (ref "U2") (pin "103") (pinfunction "P105_103") (pintype "bidirectional"))
    )
    (net (code "20") (name "DO_COMM_TX_EN") (class "Default")
      (node (ref "R47") (pin "2") (pinfunction "2_2") (pintype "passive"))
      (node (ref "U2") (pin "33") (pinfunction "P410_33") (pintype "bidirectional"))
    )
    (net (code "21") (name "DO_CONDUCTIV_PUMP_ON_LED") (class "Default")
      (node (ref "R82") (pin "1") (pinfunction "1_1") (pintype "passive"))
      (node (ref "U2") (pin "8") (pinfunction "P700_8") (pintype "bidirectional"))
    )
    (net (code "22") (name "DO_CONDUCTIV_SENSOR_DISPLAY_ON") (class "Default")
      (node (ref "R78") (pin "1") (pinfunction "1_1") (pintype "passive"))
      (node (ref "U2") (pin "7") (pinfunction "P406_7") (pintype "bidirectional"))
    )
    (net (code "23") (name "DO_CONDUCTIV_SENSOR_ON") (class "Default")
      (node (ref "R27") (pin "2") (pinfunction "2_2") (pintype "passive"))
      (node (ref "U2") (pin "108") (pinfunction "P100_108") (pintype "bidirectional"))
    )
    (net (code "24") (name "DO_CTRL_GREEN_STATUS_LED") (class "Default")
      (node (ref "R72") (pin "1") (pinfunction "1_1") (pintype "passive"))
      (node (ref "U2") (pin "5") (pinfunction "P404_5") (pintype "bidirectional"))
    )
    (net (code "25") (name "DO_CTRL_RED_STATUS_LED") (class "Default")
      (node (ref "R74") (pin "1") (pinfunction "1_1") (pintype "passive"))
      (node (ref "U2") (pin "6") (pinfunction "P405_6") (pintype "bidirectional"))
    )
    (net (code "26") (name "DO_CTRL_YELLOW_STATUS_LED") (class "Default")
      (node (ref "R70") (pin "1") (pinfunction "1_1") (pintype "passive"))
      (node (ref "U2") (pin "4") (pinfunction "P403_4") (pintype "bidirectional"))
    )
    (net (code "27") (name "DO_ESP32_EN") (class "Default")
      (node (ref "J1") (pin "J2_18") (pinfunction "EN_J2_18") (pintype "input"))
      (node (ref "R83") (pin "2") (pinfunction "2_2") (pintype "passive"))
      (node (ref "U2") (pin "69") (pinfunction "P303_69") (pintype "bidirectional"))
    )
    (net (code "28") (name "DO_PH_PUMP_ON_LED") (class "Default")
      (node (ref "R80") (pin "1") (pinfunction "1_1") (pintype "passive"))
      (node (ref "U2") (pin "10") (pinfunction "P702_10") (pintype "bidirectional"))
    )
    (net (code "29") (name "DO_PH_SENSOR_DISPLAY_ON") (class "Default")
      (node (ref "R76") (pin "1") (pinfunction "1_1") (pintype "passive"))
      (node (ref "U2") (pin "9") (pinfunction "P701_9") (pintype "bidirectional"))
    )
    (net (code "30") (name "DO_PH_SENSOR_ON") (class "Default")
      (node (ref "R35") (pin "2") (pinfunction "2_2") (pintype "passive"))
      (node (ref "U2") (pin "107") (pinfunction "P101_107") (pintype "bidirectional"))
    )
    (net (code "31") (name "DO_UART_TX_ESP32") (class "Default")
      (node (ref "R97") (pin "1") (pinfunction "1_1") (pintype "passive"))
      (node (ref "U2") (pin "70") (pinfunction "P302_70") (pintype "bidirectional"))
    )
    (net (code "32") (name "DO_USART_TX") (class "Default")
      (node (ref "R48") (pin "2") (pinfunction "2_2") (pintype "passive"))
      (node (ref "U2") (pin "34") (pinfunction "P409_34") (pintype "bidirectional"))
    )
    (net (code "33") (name "DO_V_CONDUCTIV_PUMP_ON") (class "Default")
      (node (ref "R13") (pin "2") (pinfunction "2_2") (pintype "passive"))
      (node (ref "U2") (pin "75") (pinfunction "P110/TDI_75") (pintype "bidirectional"))
    )
    (net (code "34") (name "DO_V_PH_PUMP_ON") (class "Default")
      (node (ref "R5") (pin "2") (pinfunction "2_2") (pintype "passive"))
      (node (ref "U2") (pin "76") (pinfunction "P111_76") (pintype "bidirectional"))
    )
    (net (code "35") (name "ESP32_RXD1") (class "Default")
      (node (ref "J1") (pin "J2_11") (pinfunction "IO9_J2_11") (pintype "bidirectional"))
      (node (ref "R97") (pin "2") (pinfunction "2_2") (pintype "passive"))
    )
    (net (code "36") (name "ESP32_TXD1") (class "Default")
      (node (ref "J1") (pin "J2_10") (pinfunction "IO10_J2_10") (pintype "bidirectional"))
      (node (ref "R96") (pin "2") (pinfunction "2_2") (pintype "passive"))
    )
    (net (code "37") (name "GND") (class "Default")
      (node (ref "C10") (pin "2") (pinfunction "2_2") (pintype "passive"))
      (node (ref "C11") (pin "2") (pinfunction "2_2") (pintype "passive"))
      (node (ref "C12") (pin "2") (pinfunction "2_2") (pintype "passive"))
      (node (ref "C13") (pin "2") (pinfunction "2_2") (pintype "passive"))
      (node (ref "C14") (pin "2") (pinfunction "2_2") (pintype "passive"))
      (node (ref "C15") (pin "2") (pinfunction "2_2") (pintype "passive"))
      (node (ref "C16") (pin "2") (pinfunction "2_2") (pintype "passive"))
      (node (ref "C18") (pin "2") (pinfunction "-_2") (pintype "passive"))
      (node (ref "C19") (pin "2") (pinfunction "2_2") (pintype "passive"))
      (node (ref "C2") (pin "P$1") (pinfunction "1_P$1") (pintype "passive"))
      (node (ref "C20") (pin "2") (pinfunction "2_2") (pintype "passive"))
      (node (ref "C21") (pin "2") (pinfunction "2_2") (pintype "passive"))
      (node (ref "C22") (pin "2") (pinfunction "2_2") (pintype "passive"))
      (node (ref "C23") (pin "2") (pinfunction "2_2") (pintype "passive"))
      (node (ref "C24") (pin "2") (pinfunction "2_2") (pintype "passive"))
      (node (ref "C25") (pin "1") (pinfunction "1_1") (pintype "passive"))
      (node (ref "C26") (pin "1") (pinfunction "1_1") (pintype "passive"))
      (node (ref "C27") (pin "1") (pinfunction "1_1") (pintype "passive"))
      (node (ref "C28") (pin "1") (pinfunction "1_1") (pintype "passive"))
      (node (ref "C29") (pin "1") (pinfunction "1_1") (pintype "passive"))
      (node (ref "C3") (pin "2") (pinfunction "2_2") (pintype "passive"))
      (node (ref "C30") (pin "1") (pinfunction "1_1") (pintype "passive"))
      (node (ref "C31") (pin "1") (pinfunction "1_1") (pintype "passive"))
      (node (ref "C32") (pin "1") (pinfunction "1_1") (pintype "passive"))
      (node (ref "C33") (pin "1") (pinfunction "1_1") (pintype "passive"))
      (node (ref "C34") (pin "1") (pinfunction "1_1") (pintype "passive"))
      (node (ref "C35") (pin "1") (pinfunction "1_1") (pintype "passive"))
      (node (ref "C36") (pin "2") (pinfunction "2_2") (pintype "passive"))
      (node (ref "C37") (pin "2") (pinfunction "2_2") (pintype "passive"))
      (node (ref "C38") (pin "2") (pinfunction "2_2") (pintype "passive"))
      (node (ref "C39") (pin "2") (pinfunction "2_2") (pintype "passive"))
      (node (ref "C4") (pin "2") (pinfunction "2_2") (pintype "passive"))
      (node (ref "C40") (pin "2") (pinfunction "2_2") (pintype "passive"))
      (node (ref "C41") (pin "2") (pinfunction "2_2") (pintype "passive"))
      (node (ref "C42") (pin "1") (pinfunction "1_1") (pintype "passive"))
      (node (ref "C43") (pin "1") (pinfunction "1_1") (pintype "passive"))
      (node (ref "C44") (pin "2") (pinfunction "2_2") (pintype "passive"))
      (node (ref "C49") (pin "2") (pinfunction "2_2") (pintype "passive"))
      (node (ref "C5") (pin "2") (pinfunction "2_2") (pintype "passive"))
      (node (ref "C50") (pin "1") (pinfunction "1_1") (pintype "passive"))
      (node (ref "C51") (pin "1") (pinfunction "1_1") (pintype "passive"))
      (node (ref "C53") (pin "1") (pinfunction "1_1") (pintype "passive"))
      (node (ref "C55") (pin "1") (pinfunction "1_1") (pintype "passive"))
      (node (ref "C56") (pin "1") (pinfunction "1_1") (pintype "passive"))
      (node (ref "C57") (pin "1") (pinfunction "1_1") (pintype "passive"))
      (node (ref "C58") (pin "1") (pinfunction "1_1") (pintype "passive"))
      (node (ref "C59") (pin "1") (pinfunction "1_1") (pintype "passive"))
      (node (ref "C6") (pin "1") (pinfunction "1_1") (pintype "passive"))
      (node (ref "C60") (pin "1") (pinfunction "1_1") (pintype "passive"))
      (node (ref "C61") (pin "1") (pinfunction "1_1") (pintype "passive"))
      (node (ref "C62") (pin "1") (pinfunction "1_1") (pintype "passive"))
      (node (ref "C63") (pin "1") (pinfunction "1_1") (pintype "passive"))
      (node (ref "C64") (pin "1") (pinfunction "1_1") (pintype "passive"))
      (node (ref "C65") (pin "1") (pinfunction "1_1") (pintype "passive"))
      (node (ref "C66") (pin "1") (pinfunction "1_1") (pintype "passive"))
      (node (ref "C67") (pin "1") (pinfunction "1_1") (pintype "passive"))
      (node (ref "C68") (pin "1") (pinfunction "1_1") (pintype "passive"))
      (node (ref "C7") (pin "1") (pinfunction "1_1") (pintype "passive"))
      (node (ref "C8") (pin "2") (pinfunction "2_2") (pintype "passive"))
      (node (ref "C9") (pin "2") (pinfunction "2_2") (pintype "passive"))
      (node (ref "D1") (pin "2") (pinfunction "A_2") (pintype "passive"))
      (node (ref "D10") (pin "1") (pinfunction "A1_1") (pintype "passive"))
      (node (ref "D13") (pin "1") (pinfunction "A1_1") (pintype "passive"))
      (node (ref "D2") (pin "2") (pinfunction "A_2") (pintype "passive"))
      (node (ref "D4") (pin "1") (pinfunction "C1_1") (pintype "passive"))
      (node (ref "D5") (pin "1") (pinfunction "A1_1") (pintype "passive"))
      (node (ref "D6") (pin "1") (pinfunction "C1_1") (pintype "passive"))
      (node (ref "D7") (pin "1") (pinfunction "A1_1") (pintype "passive"))
      (node (ref "D8") (pin "1") (pinfunction "A1_1") (pintype "passive"))
      (node (ref "D9") (pin "1") (pinfunction "A1_1") (pintype "passive"))
      (node (ref "IC1") (pin "5") (pinfunction "GND_5") (pintype "bidirectional"))
      (node (ref "IC2") (pin "2") (pinfunction "GND_2") (pintype "power_in"))
      (node (ref "IC3") (pin "2") (pinfunction "V-_2") (pintype "bidirectional"))
      (node (ref "IC4") (pin "2") (pinfunction "V-_2") (pintype "bidirectional"))
      (node (ref "IC5") (pin "1") (pinfunction "GND_1") (pintype "bidirectional"))
      (node (ref "IC6") (pin "1") (pinfunction "GND_1") (pintype "power_in"))
      (node (ref "J1") (pin "J2_19") (pinfunction "GND_1_J2_19") (pintype "power_in"))
      (node (ref "J1") (pin "J3_19") (pinfunction "GND_2_J3_19") (pintype "power_in"))
      (node (ref "K1") (pin "P$1") (pinfunction "1_P$1") (pintype "passive"))
      (node (ref "K3") (pin "P$1") (pinfunction "1_P$1") (pintype "passive"))
      (node (ref "Q11") (pin "2") (pinfunction "S_2") (pintype "passive"))
      (node (ref "Q13") (pin "2") (pinfunction "S_2") (pintype "passive"))
      (node (ref "Q15") (pin "2") (pinfunction "S_2") (pintype "passive"))
      (node (ref "Q2") (pin "2") (pinfunction "S_2") (pintype "passive"))
      (node (ref "Q4") (pin "2") (pinfunction "S_2") (pintype "passive"))
      (node (ref "Q7") (pin "2") (pinfunction "S_2") (pintype "passive"))
      (node (ref "Q9") (pin "2") (pinfunction "S_2") (pintype "passive"))
      (node (ref "R1") (pin "1") (pinfunction "1_1") (pintype "passive"))
      (node (ref "R12") (pin "1") (pinfunction "1_1") (pintype "passive"))
      (node (ref "R17") (pin "1") (pinfunction "1_1") (pintype "passive"))
      (node (ref "R18") (pin "1") (pinfunction "1_1") (pintype "passive"))
      (node (ref "R20") (pin "1") (pinfunction "1_1") (pintype "passive"))
      (node (ref "R21") (pin "1") (pinfunction "1_1") (pintype "passive"))
      (node (ref "R23") (pin "1") (pinfunction "1_1") (pintype "passive"))
      (node (ref "R26") (pin "1") (pinfunction "1_1") (pintype "passive"))
      (node (ref "R29") (pin "1") (pinfunction "1_1") (pintype "passive"))
      (node (ref "R34") (pin "1") (pinfunction "1_1") (pintype "passive"))
      (node (ref "R37") (pin "1") (pinfunction "1_1") (pintype "passive"))
      (node (ref "R4") (pin "1") (pinfunction "1_1") (pintype "passive"))
      (node (ref "R41") (pin "1") (pinfunction "1_1") (pintype "passive"))
      (node (ref "R44") (pin "2") (pinfunction "2_2") (pintype "passive"))
      (node (ref "R46") (pin "1") (pinfunction "1_1") (pintype "passive"))
      (node (ref "R51") (pin "1") (pinfunction "1_1") (pintype "passive"))
      (node (ref "R57") (pin "1") (pinfunction "1_1") (pintype "passive"))
      (node (ref "R61") (pin "1") (pinfunction "1_1") (pintype "passive"))
      (node (ref "R65") (pin "1") (pinfunction "1_1") (pintype "passive"))
      (node (ref "R69") (pin "1") (pinfunction "1_1") (pintype "passive"))
      (node (ref "R71") (pin "1") (pinfunction "1_1") (pintype "passive"))
      (node (ref "R73") (pin "1") (pinfunction "1_1") (pintype "passive"))
      (node (ref "R75") (pin "1") (pinfunction "1_1") (pintype "passive"))
      (node (ref "R77") (pin "1") (pinfunction "1_1") (pintype "passive"))
      (node (ref "R79") (pin "1") (pinfunction "1_1") (pintype "passive"))
      (node (ref "R81") (pin "1") (pinfunction "1_1") (pintype "passive"))
      (node (ref "R86") (pin "1") (pinfunction "1_1") (pintype "passive"))
      (node (ref "R9") (pin "1") (pinfunction "1_1") (pintype "passive"))
      (node (ref "R92") (pin "1") (pinfunction "1_1") (pintype "passive"))
      (node (ref "U2") (pin "100") (pinfunction "VSS_4_100") (pintype "power_in"))
      (node (ref "U2") (pin "112") (pinfunction "VSS_5_112") (pintype "power_in"))
      (node (ref "U2") (pin "122") (pinfunction "VSS_6_122") (pintype "power_in"))
      (node (ref "U2") (pin "125") (pinfunction "VREFL_125") (pintype "power_in"))
      (node (ref "U2") (pin "128") (pinfunction "AVSS0_128") (pintype "power_in"))
      (node (ref "U2") (pin "141") (pinfunction "VSS_141") (pintype "power_in"))
      (node (ref "U2") (pin "18") (pinfunction "VSS_2_18") (pintype "power_in"))
      (node (ref "U2") (pin "48") (pinfunction "VSS_3_48") (pintype "power_in"))
      (node (ref "U2") (pin "67") (pinfunction "VSS_67") (pintype "power_in"))
      (node (ref "U2") (pin "82") (pinfunction "VSS_2_82") (pintype "power_in"))
      (node (ref "U2") (pin "91") (pinfunction "VSS_3_91") (pintype "power_in"))
      (node (ref "V2") (pin "1") (pinfunction "1_1") (pintype "passive"))
      (node (ref "V3") (pin "1") (pinfunction "1_1") (pintype "passive"))
      (node (ref "V6") (pin "1") (pinfunction "1_1") (pintype "passive"))
      (node (ref "V7") (pin "1") (pinfunction "1_1") (pintype "passive"))
      (node (ref "V8") (pin "1") (pinfunction "1_1") (pintype "passive"))
      (node (ref "X1") (pin "2") (pinfunction "2_2") (pintype "bidirectional"))
      (node (ref "X11") (pin "2") (pinfunction "2_2") (pintype "bidirectional"))
      (node (ref "X13") (pin "16") (pinfunction "S_16") (pintype "passive"))
      (node (ref "X2") (pin "3") (pinfunction "3_3") (pintype "bidirectional"))
      (node (ref "X2") (pin "5") (pinfunction "5_5") (pintype "bidirectional"))
      (node (ref "X2") (pin "9") (pinfunction "9_9") (pintype "bidirectional"))
      (node (ref "X3") (pin "2") (pinfunction "2_2") (pintype "bidirectional"))
      (node (ref "X4") (pin "2") (pinfunction "2_2") (pintype "bidirectional"))
    )
    (net (code "38") (name "MAINS_L") (class "Default")
      (node (ref "F1") (pin "1") (pinfunction "P$1_1") (pintype "bidirectional"))
      (node (ref "X10") (pin "1") (pinfunction "1_1") (pintype "passive"))
      (node (ref "X10") (pin "1-2") (pinfunction "1_1-2") (pintype "passive"))
    )
    (net (code "39") (name "MAINS_L_F") (class "Default")
      (node (ref "C1") (pin "1") (pinfunction "1_1") (pintype "passive"))
      (node (ref "F1") (pin "2") (pinfunction "P$2_2") (pintype "bidirectional"))
      (node (ref "K1") (pin "P$4") (pinfunction "4_P$4") (pintype "passive"))
      (node (ref "K3") (pin "P$4") (pinfunction "4_P$4") (pintype "passive"))
      (node (ref "R6") (pin "2") (pinfunction "2_2") (pintype "passive"))
      (node (ref "V1") (pin "2") (pinfunction "2_2") (pintype "passive"))
      (node (ref "V4") (pin "1") (pinfunction "1_1") (pintype "passive"))
      (node (ref "V5") (pin "1") (pinfunction "1_1") (pintype "passive"))
    )
    (net (code "40") (name "MAINS_N") (class "Default")
      (node (ref "C1") (pin "2") (pinfunction "2_2") (pintype "passive"))
      (node (ref "C2") (pin "P$2") (pinfunction "2_P$2") (pintype "passive"))
      (node (ref "R7") (pin "1") (pinfunction "1_1") (pintype "passive"))
      (node (ref "R8") (pin "2") (pinfunction "2_2") (pintype "passive"))
      (node (ref "V1") (pin "1") (pinfunction "1_1") (pintype "passive"))
      (node (ref "X5") (pin "1") (pinfunction "1_1") (pintype "passive"))
      (node (ref "X5") (pin "1-2") (pinfunction "1_1-2") (pintype "passive"))
      (node (ref "X6") (pin "1") (pinfunction "1_1") (pintype "passive"))
      (node (ref "X6") (pin "1-2") (pinfunction "1_1-2") (pintype "passive"))
      (node (ref "X7") (pin "1") (pinfunction "1_1") (pintype "passive"))
      (node (ref "X7") (pin "1-2") (pinfunction "1_1-2") (pintype "passive"))
    )
    (net (code "41") (name "NRST") (class "Default")
      (node (ref "C41") (pin "1") (pinfunction "1_1") (pintype "passive"))
      (node (ref "R84") (pin "2") (pinfunction "2_2") (pintype "passive"))
      (node (ref "U2") (pin "55") (pinfunction "RES_55") (pintype "passive"))
      (node (ref "X2") (pin "10") (pinfunction "10_10") (pintype "bidirectional"))
    )
    (net (code "42") (name "Net-(C4-Pad1)") (class "Default")
      (node (ref "C4") (pin "1") (pinfunction "1_1") (pintype "passive"))
      (node (ref "R49") (pin "1") (pinfunction "1_1") (pintype "passive"))
      (node (ref "R50") (pin "1") (pinfunction "1_1") (pintype "passive"))
    )
    (net (code "43") (name "Net-(C5-Pad1)") (class "Default")
      (node (ref "C5") (pin "1") (pinfunction "1_1") (pintype "passive"))
      (node (ref "Q5") (pin "2") (pinfunction "DRAIN_2") (pintype "passive"))
      (node (ref "Q5") (pin "4") (pinfunction "DRAIN_4") (pintype "passive"))
      (node (ref "SW1") (pin "2") (pinfunction "2_2") (pintype "passive"))
    )
    (net (code "44") (name "Net-(D1-C)") (class "Default")
      (node (ref "D1") (pin "1") (pinfunction "C_1") (pintype "passive"))
      (node (ref "K1") (pin "P$2") (pinfunction "2_P$2") (pintype "passive"))
      (node (ref "Q1") (pin "2") (pinfunction "DRAIN_2") (pintype "passive"))
      (node (ref "Q1") (pin "4") (pinfunction "DRAIN_4") (pintype "passive"))
      (node (ref "R1") (pin "2") (pinfunction "2_2") (pintype "passive"))
    )
    (net (code "45") (name "Net-(D2-C)") (class "Default")
      (node (ref "D2") (pin "1") (pinfunction "C_1") (pintype "passive"))
      (node (ref "K3") (pin "P$2") (pinfunction "2_P$2") (pintype "passive"))
      (node (ref "Q3") (pin "2") (pinfunction "DRAIN_2") (pintype "passive"))
      (node (ref "Q3") (pin "4") (pinfunction "DRAIN_4") (pintype "passive"))
      (node (ref "R9") (pin "2") (pinfunction "2_2") (pintype "passive"))
    )
    (net (code "46") (name "Net-(D3-A)") (class "Default")
      (node (ref "D3") (pin "1") (pinfunction "A_1") (pintype "passive"))
      (node (ref "Q5") (pin "1") (pinfunction "GATE_1") (pintype "passive"))
      (node (ref "R17") (pin "2") (pinfunction "2_2") (pintype "passive"))
    )
    (net (code "47") (name "Net-(D12-C)") (class "Default")
      (node (ref "D12") (pin "2") (pinfunction "C_2") (pintype "passive"))
      (node (ref "R86") (pin "2") (pinfunction "2_2") (pintype "passive"))
    )
    (net (code "48") (name "Net-(D14-A)") (class "Default")
      (node (ref "D14") (pin "1") (pinfunction "A_1") (pintype "passive"))
      (node (ref "Q1") (pin "1") (pinfunction "GATE_1") (pintype "passive"))
      (node (ref "R2") (pin "1") (pinfunction "1_1") (pintype "passive"))
      (node (ref "R3") (pin "2") (pinfunction "2_2") (pintype "passive"))
    )
    (net (code "49") (name "Net-(D15-A)") (class "Default")
      (node (ref "D15") (pin "1") (pinfunction "A_1") (pintype "passive"))
      (node (ref "Q3") (pin "1") (pinfunction "GATE_1") (pintype "passive"))
      (node (ref "R10") (pin "1") (pinfunction "1_1") (pintype "passive"))
      (node (ref "R11") (pin "2") (pinfunction "2_2") (pintype "passive"))
    )
    (net (code "50") (name "Net-(D16-A)") (class "Default")
      (node (ref "D16") (pin "1") (pinfunction "A_1") (pintype "passive"))
      (node (ref "Q6") (pin "1") (pinfunction "GATE_1") (pintype "passive"))
      (node (ref "R24") (pin "1") (pinfunction "1_1") (pintype "passive"))
      (node (ref "R25") (pin "2") (pinfunction "2_2") (pintype "passive"))
    )
    (net (code "51") (name "Net-(D17-A)") (class "Default")
      (node (ref "D17") (pin "1") (pinfunction "A_1") (pintype "passive"))
      (node (ref "Q8") (pin "1") (pinfunction "GATE_1") (pintype "passive"))
      (node (ref "R32") (pin "1") (pinfunction "1_1") (pintype "passive"))
      (node (ref "R33") (pin "2") (pinfunction "2_2") (pintype "passive"))
    )
    (net (code "52") (name "Net-(IC1-D)") (class "Default")
      (node (ref "IC1") (pin "4") (pinfunction "D_4") (pintype "bidirectional"))
      (node (ref "R48") (pin "1") (pinfunction "1_1") (pintype "passive"))
    )
    (net (code "53") (name "Net-(IC1-DE)") (class "Default")
      (node (ref "IC1") (pin "3") (pinfunction "DE_3") (pintype "bidirectional"))
      (node (ref "R47") (pin "1") (pinfunction "1_1") (pintype "passive"))
    )
    (net (code "54") (name "Net-(IC1-R)") (class "Default")
      (node (ref "IC1") (pin "1") (pinfunction "R_1") (pintype "bidirectional"))
      (node (ref "Q10") (pin "2") (pinfunction "E_2") (pintype "passive"))
    )
    (net (code "55") (name "Net-(IC1-{slash}RE)") (class "Default")
      (node (ref "IC1") (pin "2") (pinfunction "/RE_2") (pintype "bidirectional"))
      (node (ref "R16") (pin "1") (pinfunction "1_1") (pintype "passive"))
    )
    (net (code "56") (name "Net-(IC2-INPUT)") (class "Default")
      (node (ref "C42") (pin "2") (pinfunction "2_2") (pintype "passive"))
      (node (ref "IC2") (pin "1") (pinfunction "INPUT_1") (pintype "passive"))
      (node (ref "R93") (pin "2") (pinfunction "2_2") (pintype "passive"))
      (node (ref "U2") (pin "20") (pinfunction "P212/EXTAL_20") (pintype "bidirectional"))
    )
    (net (code "57") (name "Net-(IC2-OUTPUT)") (class "Default")
      (node (ref "C43") (pin "2") (pinfunction "2_2") (pintype "passive"))
      (node (ref "IC2") (pin "3") (pinfunction "OUTPUT_3") (pintype "passive"))
      (node (ref "R94") (pin "1") (pinfunction "1_1") (pintype "passive"))
    )
    (net (code "58") (name "Net-(IC3-IN-)") (class "Default")
      (node (ref "IC3") (pin "3") (pinfunction "IN-_3") (pintype "bidirectional"))
      (node (ref "R31") (pin "1") (pinfunction "1_1") (pintype "passive"))
    )
    (net (code "59") (name "Net-(IC3-OUT)") (class "Default")
      (node (ref "IC3") (pin "1") (pinfunction "OUT_1") (pintype "bidirectional"))
      (node (ref "R29") (pin "2") (pinfunction "2_2") (pintype "passive"))
      (node (ref "R30") (pin "1") (pinfunction "1_1") (pintype "passive"))
    )
    (net (code "60") (name "Net-(IC3-V+)") (class "Default")
      (node (ref "IC3") (pin "5") (pinfunction "V+_5") (pintype "bidirectional"))
      (node (ref "Q6") (pin "2") (pinfunction "DRAIN_2") (pintype "passive"))
      (node (ref "Q6") (pin "4") (pinfunction "DRAIN_4") (pintype "passive"))
      (node (ref "R28") (pin "1") (pinfunction "1_1") (pintype "passive"))
      (node (ref "R31") (pin "2") (pinfunction "2_2") (pintype "passive"))
    )
    (net (code "61") (name "Net-(IC4-IN-)") (class "Default")
      (node (ref "IC4") (pin "3") (pinfunction "IN-_3") (pintype "bidirectional"))
      (node (ref "R39") (pin "1") (pinfunction "1_1") (pintype "passive"))
    )
    (net (code "62") (name "Net-(IC4-OUT)") (class "Default")
      (node (ref "IC4") (pin "1") (pinfunction "OUT_1") (pintype "bidirectional"))
      (node (ref "R37") (pin "2") (pinfunction "2_2") (pintype "passive"))
      (node (ref "R38") (pin "1") (pinfunction "1_1") (pintype "passive"))
    )
    (net (code "63") (name "Net-(IC4-V+)") (class "Default")
      (node (ref "IC4") (pin "5") (pinfunction "V+_5") (pintype "bidirectional"))
      (node (ref "Q8") (pin "2") (pinfunction "DRAIN_2") (pintype "passive"))
      (node (ref "Q8") (pin "4") (pinfunction "DRAIN_4") (pintype "passive"))
      (node (ref "R36") (pin "1") (pinfunction "1_1") (pintype "passive"))
      (node (ref "R39") (pin "2") (pinfunction "2_2") (pintype "passive"))
    )
    (net (code "64") (name "Net-(IC5-BST)") (class "Default")
      (node (ref "C17") (pin "1") (pinfunction "1_1") (pintype "passive"))
      (node (ref "IC5") (pin "6") (pinfunction "BST_6") (pintype "bidirectional"))
    )
    (net (code "65") (name "Net-(IC5-EN)") (class "Default")
      (node (ref "IC5") (pin "5") (pinfunction "EN_5") (pintype "bidirectional"))
      (node (ref "R43") (pin "1") (pinfunction "1_1") (pintype "passive"))
    )
    (net (code "66") (name "Net-(IC5-FB)") (class "Default")
      (node (ref "IC5") (pin "4") (pinfunction "FB_4") (pintype "bidirectional"))
      (node (ref "R44") (pin "1") (pinfunction "1_1") (pintype "passive"))
      (node (ref "R45") (pin "1") (pinfunction "1_1") (pintype "passive"))
    )
    (net (code "67") (name "Net-(IC5-SW)") (class "Default")
      (node (ref "C17") (pin "2") (pinfunction "2_2") (pintype "passive"))
      (node (ref "IC5") (pin "2") (pinfunction "SW_2") (pintype "bidirectional"))
      (node (ref "L1") (pin "1") (pinfunction "P$1_1") (pintype "bidirectional"))
    )
    (net (code "68") (name "Net-(IC5-VIN)") (class "Default")
      (node (ref "C12") (pin "1") (pinfunction "1_1") (pintype "passive"))
      (node (ref "C13") (pin "1") (pinfunction "1_1") (pintype "passive"))
      (node (ref "IC5") (pin "3") (pinfunction "VIN_3") (pintype "bidirectional"))
      (node (ref "IC8") (pin "2") (pinfunction "OUT_2") (pintype "power_in"))
      (node (ref "IC8") (pin "4") (pinfunction "TAB_4") (pintype "power_in"))
      (node (ref "R43") (pin "2") (pinfunction "2_2") (pintype "passive"))
      (node (ref "R91") (pin "2") (pinfunction "2_2") (pintype "passive"))
    )
    (net (code "69") (name "Net-(IC8-ADJ)") (class "Default")
      (node (ref "IC8") (pin "1") (pinfunction "ADJ_1") (pintype "input"))
      (node (ref "R91") (pin "1") (pinfunction "1_1") (pintype "passive"))
      (node (ref "R92") (pin "2") (pinfunction "2_2") (pintype "passive"))
    )
    (net (code "70") (name "Net-(Q2-D)") (class "Default")
      (node (ref "Q2") (pin "3") (pinfunction "D_3") (pintype "passive"))
      (node (ref "R3") (pin "1") (pinfunction "1_1") (pintype "passive"))
    )
    (net (code "71") (name "Net-(Q2-G)") (class "Default")
      (node (ref "Q2") (pin "1") (pinfunction "G_1") (pintype "passive"))
      (node (ref "R4") (pin "2") (pinfunction "2_2") (pintype "passive"))
      (node (ref "R5") (pin "1") (pinfunction "1_1") (pintype "passive"))
    )
    (net (code "72") (name "Net-(Q4-D)") (class "Default")
      (node (ref "Q4") (pin "3") (pinfunction "D_3") (pintype "passive"))
      (node (ref "R11") (pin "1") (pinfunction "1_1") (pintype "passive"))
    )
    (net (code "73") (name "Net-(Q4-G)") (class "Default")
      (node (ref "Q4") (pin "1") (pinfunction "G_1") (pintype "passive"))
      (node (ref "R12") (pin "2") (pinfunction "2_2") (pintype "passive"))
      (node (ref "R13") (pin "1") (pinfunction "1_1") (pintype "passive"))
    )
    (net (code "74") (name "Net-(Q7-D)") (class "Default")
      (node (ref "Q7") (pin "3") (pinfunction "D_3") (pintype "passive"))
      (node (ref "R25") (pin "1") (pinfunction "1_1") (pintype "passive"))
    )
    (net (code "75") (name "Net-(Q7-G)") (class "Default")
      (node (ref "Q7") (pin "1") (pinfunction "G_1") (pintype "passive"))
      (node (ref "R26") (pin "2") (pinfunction "2_2") (pintype "passive"))
      (node (ref "R27") (pin "1") (pinfunction "1_1") (pintype "passive"))
    )
    (net (code "76") (name "Net-(Q9-D)") (class "Default")
      (node (ref "Q9") (pin "3") (pinfunction "D_3") (pintype "passive"))
      (node (ref "R33") (pin "1") (pinfunction "1_1") (pintype "passive"))
    )
    (net (code "77") (name "Net-(Q9-G)") (class "Default")
      (node (ref "Q9") (pin "1") (pinfunction "G_1") (pintype "passive"))
      (node (ref "R34") (pin "2") (pinfunction "2_2") (pintype "passive"))
      (node (ref "R35") (pin "1") (pinfunction "1_1") (pintype "passive"))
    )
    (net (code "78") (name "Net-(Q10-B)") (class "Default")
      (node (ref "Q10") (pin "1") (pinfunction "B_1") (pintype "passive"))
      (node (ref "R14") (pin "1") (pinfunction "1_1") (pintype "passive"))
    )
    (net (code "79") (name "Net-(Q10-C)") (class "Default")
      (node (ref "Q10") (pin "3") (pinfunction "C_3") (pintype "passive"))
      (node (ref "R15") (pin "1") (pinfunction "1_1") (pintype "passive"))
      (node (ref "R95") (pin "1") (pinfunction "1_1") (pintype "passive"))
    )
    (net (code "80") (name "Net-(Q11-D)") (class "Default")
      (node (ref "Q11") (pin "3") (pinfunction "D_3") (pintype "passive"))
      (node (ref "R58") (pin "1") (pinfunction "1_1") (pintype "passive"))
    )
    (net (code "81") (name "Net-(Q11-G)") (class "Default")
      (node (ref "Q11") (pin "1") (pinfunction "G_1") (pintype "passive"))
      (node (ref "R56") (pin "2") (pinfunction "2_2") (pintype "passive"))
      (node (ref "R57") (pin "2") (pinfunction "2_2") (pintype "passive"))
    )
    (net (code "82") (name "Net-(Q12-GATE)") (class "Default")
      (node (ref "Q12") (pin "1") (pinfunction "GATE_1") (pintype "passive"))
      (node (ref "R58") (pin "2") (pinfunction "2_2") (pintype "passive"))
      (node (ref "R59") (pin "1") (pinfunction "1_1") (pintype "passive"))
    )
    (net (code "83") (name "Net-(Q13-D)") (class "Default")
      (node (ref "Q13") (pin "3") (pinfunction "D_3") (pintype "passive"))
      (node (ref "R62") (pin "1") (pinfunction "1_1") (pintype "passive"))
    )
    (net (code "84") (name "Net-(Q13-G)") (class "Default")
      (node (ref "Q13") (pin "1") (pinfunction "G_1") (pintype "passive"))
      (node (ref "R60") (pin "2") (pinfunction "2_2") (pintype "passive"))
      (node (ref "R61") (pin "2") (pinfunction "2_2") (pintype "passive"))
    )
    (net (code "85") (name "Net-(Q14-GATE)") (class "Default")
      (node (ref "Q14") (pin "1") (pinfunction "GATE_1") (pintype "passive"))
      (node (ref "R62") (pin "2") (pinfunction "2_2") (pintype "passive"))
      (node (ref "R63") (pin "1") (pinfunction "1_1") (pintype "passive"))
    )
    (net (code "86") (name "Net-(Q15-D)") (class "Default")
      (node (ref "Q15") (pin "3") (pinfunction "D_3") (pintype "passive"))
      (node (ref "R66") (pin "1") (pinfunction "1_1") (pintype "passive"))
    )
    (net (code "87") (name "Net-(Q15-G)") (class "Default")
      (node (ref "Q15") (pin "1") (pinfunction "G_1") (pintype "passive"))
      (node (ref "R64") (pin "2") (pinfunction "2_2") (pintype "passive"))
      (node (ref "R65") (pin "2") (pinfunction "2_2") (pintype "passive"))
    )
    (net (code "88") (name "Net-(Q16-GATE)") (class "Default")
      (node (ref "Q16") (pin "1") (pinfunction "GATE_1") (pintype "passive"))
      (node (ref "R66") (pin "2") (pinfunction "2_2") (pintype "passive"))
      (node (ref "R67") (pin "1") (pinfunction "1_1") (pintype "passive"))
    )
    (net (code "89") (name "Net-(Q17-B)") (class "Default")
      (node (ref "Q17") (pin "1") (pinfunction "B_1") (pintype "passive"))
      (node (ref "R70") (pin "2") (pinfunction "2_2") (pintype "passive"))
    )
    (net (code "90") (name "Net-(Q17-E)") (class "Default")
      (node (ref "Q17") (pin "2") (pinfunction "E_2") (pintype "passive"))
      (node (ref "R69") (pin "2") (pinfunction "2_2") (pintype "passive"))
    )
    (net (code "91") (name "Net-(Q18-B)") (class "Default")
      (node (ref "Q18") (pin "1") (pinfunction "B_1") (pintype "passive"))
      (node (ref "R72") (pin "2") (pinfunction "2_2") (pintype "passive"))
    )
    (net (code "92") (name "Net-(Q18-E)") (class "Default")
      (node (ref "Q18") (pin "2") (pinfunction "E_2") (pintype "passive"))
      (node (ref "R71") (pin "2") (pinfunction "2_2") (pintype "passive"))
    )
    (net (code "93") (name "Net-(Q19-B)") (class "Default")
      (node (ref "Q19") (pin "1") (pinfunction "B_1") (pintype "passive"))
      (node (ref "R74") (pin "2") (pinfunction "2_2") (pintype "passive"))
    )
    (net (code "94") (name "Net-(Q19-E)") (class "Default")
      (node (ref "Q19") (pin "2") (pinfunction "E_2") (pintype "passive"))
      (node (ref "R73") (pin "2") (pinfunction "2_2") (pintype "passive"))
    )
    (net (code "95") (name "Net-(Q20-B)") (class "Default")
      (node (ref "Q20") (pin "1") (pinfunction "B_1") (pintype "passive"))
      (node (ref "R76") (pin "2") (pinfunction "2_2") (pintype "passive"))
    )
    (net (code "96") (name "Net-(Q20-E)") (class "Default")
      (node (ref "Q20") (pin "2") (pinfunction "E_2") (pintype "passive"))
      (node (ref "R75") (pin "2") (pinfunction "2_2") (pintype "passive"))
    )
    (net (code "97") (name "Net-(Q21-B)") (class "Default")
      (node (ref "Q21") (pin "1") (pinfunction "B_1") (pintype "passive"))
      (node (ref "R78") (pin "2") (pinfunction "2_2") (pintype "passive"))
    )
    (net (code "98") (name "Net-(Q21-E)") (class "Default")
      (node (ref "Q21") (pin "2") (pinfunction "E_2") (pintype "passive"))
      (node (ref "R77") (pin "2") (pinfunction "2_2") (pintype "passive"))
    )
    (net (code "99") (name "Net-(Q22-B)") (class "Default")
      (node (ref "Q22") (pin "1") (pinfunction "B_1") (pintype "passive"))
      (node (ref "R80") (pin "2") (pinfunction "2_2") (pintype "passive"))
    )
    (net (code "100") (name "Net-(Q22-E)") (class "Default")
      (node (ref "Q22") (pin "2") (pinfunction "E_2") (pintype "passive"))
      (node (ref "R79") (pin "2") (pinfunction "2_2") (pintype "passive"))
    )
    (net (code "101") (name "Net-(Q23-B)") (class "Default")
      (node (ref "Q23") (pin "1") (pinfunction "B_1") (pintype "passive"))
      (node (ref "R82") (pin "2") (pinfunction "2_2") (pintype "passive"))
    )
    (net (code "102") (name "Net-(Q23-E)") (class "Default")
      (node (ref "Q23") (pin "2") (pinfunction "E_2") (pintype "passive"))
      (node (ref "R81") (pin "2") (pinfunction "2_2") (pintype "passive"))
    )
    (net (code "103") (name "Net-(R6-Pad1)") (class "Default")
      (node (ref "R6") (pin "1") (pinfunction "1_1") (pintype "passive"))
      (node (ref "R7") (pin "2") (pinfunction "2_2") (pintype "passive"))
    )
    (net (code "104") (name "Net-(R40-Pad1)") (class "Default")
      (node (ref "R40") (pin "1") (pinfunction "1_1") (pintype "passive"))
      (node (ref "R41") (pin "2") (pinfunction "2_2") (pintype "passive"))
      (node (ref "R42") (pin "2") (pinfunction "2_2") (pintype "passive"))
    )
    (net (code "105") (name "Net-(R46-Pad2)") (class "Default")
      (node (ref "R46") (pin "2") (pinfunction "2_2") (pintype "passive"))
      (node (ref "R8") (pin "1") (pinfunction "1_1") (pintype "passive"))
    )
    (net (code "106") (name "Net-(U2A-P213{slash}XTAL)") (class "Default")
      (node (ref "R93") (pin "1") (pinfunction "1_1") (pintype "passive"))
      (node (ref "R94") (pin "2") (pinfunction "2_2") (pintype "passive"))
      (node (ref "U2") (pin "19") (pinfunction "P213/XTAL_19") (pintype "bidirectional"))
    )
    (net (code "107") (name "Net-(U2A-VCL0)") (class "Default")
      (node (ref "C51") (pin "2") (pinfunction "2_2") (pintype "passive"))
      (node (ref "U2") (pin "15") (pinfunction "VCL0_15") (pintype "power_in"))
    )
    (net (code "108") (name "Net-(U2B-VCL)") (class "Default")
      (node (ref "C57") (pin "2") (pinfunction "2_2") (pintype "passive"))
      (node (ref "U2") (pin "92") (pinfunction "VCL_92") (pintype "power_in"))
    )
    (net (code "109") (name "Net-(X13D-S)") (class "Default")
      (node (ref "R87") (pin "1") (pinfunction "1_1") (pintype "passive"))
      (node (ref "X13") (pin "12") (pinfunction "S_12") (pintype "passive"))
    )
    (net (code "110") (name "Net-(X13E-S)") (class "Default")
      (node (ref "R88") (pin "1") (pinfunction "1_1") (pintype "passive"))
      (node (ref "X13") (pin "13") (pinfunction "S_13") (pintype "passive"))
    )
    (net (code "111") (name "Net-(X13F-S)") (class "Default")
      (node (ref "R89") (pin "1") (pinfunction "1_1") (pintype "passive"))
      (node (ref "X13") (pin "14") (pinfunction "S_14") (pintype "passive"))
    )
    (net (code "112") (name "Net-(X13G-S)") (class "Default")
      (node (ref "R90") (pin "1") (pinfunction "1_1") (pintype "passive"))
      (node (ref "X13") (pin "15") (pinfunction "S_15") (pintype "passive"))
    )
    (net (code "113") (name "PH_PUMP_MAINS_L_SW") (class "Default")
      (node (ref "K1") (pin "P$3") (pinfunction "3_P$3") (pintype "passive"))
      (node (ref "V4") (pin "2") (pinfunction "2_2") (pintype "passive"))
      (node (ref "X8") (pin "1") (pinfunction "1_1") (pintype "passive"))
      (node (ref "X8") (pin "1-2") (pinfunction "1_1-2") (pintype "passive"))
    )
    (net (code "114") (name "RS485_A") (class "Default")
      (node (ref "IC1") (pin "6") (pinfunction "A_6") (pintype "bidirectional"))
      (node (ref "R50") (pin "2") (pinfunction "2_2") (pintype "passive"))
      (node (ref "R55") (pin "1") (pinfunction "1_1") (pintype "passive"))
      (node (ref "V2") (pin "2") (pinfunction "2_2") (pintype "passive"))
      (node (ref "X12") (pin "1") (pinfunction "1_1") (pintype "passive"))
    )
    (net (code "115") (name "RS485_A_NEXT") (class "Default")
      (node (ref "R55") (pin "2") (pinfunction "2_2") (pintype "passive"))
      (node (ref "X14") (pin "1") (pinfunction "1_1") (pintype "passive"))
    )
    (net (code "116") (name "RS485_B") (class "Default")
      (node (ref "IC1") (pin "7") (pinfunction "B_7") (pintype "bidirectional"))
      (node (ref "R49") (pin "2") (pinfunction "2_2") (pintype "passive"))
      (node (ref "R53") (pin "1") (pinfunction "1_1") (pintype "passive"))
      (node (ref "V3") (pin "2") (pinfunction "2_2") (pintype "passive"))
      (node (ref "X12") (pin "2") (pinfunction "2_2") (pintype "passive"))
    )
    (net (code "117") (name "RS485_B_NEXT") (class "Default")
      (node (ref "R53") (pin "2") (pinfunction "2_2") (pintype "passive"))
      (node (ref "X14") (pin "2") (pinfunction "2_2") (pintype "passive"))
    )
    (net (code "118") (name "V5V0_ESP32") (class "Default")
      (node (ref "C36") (pin "1") (pinfunction "1_1") (pintype "passive"))
      (node (ref "C39") (pin "1") (pinfunction "1_1") (pintype "passive"))
      (node (ref "J1") (pin "J3_20") (pinfunction "EXT_5V_J3_20") (pintype "power_in"))
      (node (ref "R85") (pin "1") (pinfunction "1_1") (pintype "passive"))
    )
    (net (code "119") (name "VBATT") (class "Default")
      (node (ref "U2") (pin "14") (pinfunction "VBATT_14") (pintype "power_in"))
    )
    (net (code "120") (name "VCC") (class "Default")
      (node (ref "C22") (pin "1") (pinfunction "1_1") (pintype "passive"))
      (node (ref "C23") (pin "1") (pinfunction "1_1") (pintype "passive"))
      (node (ref "C3") (pin "1") (pinfunction "1_1") (pintype "passive"))
      (node (ref "C37") (pin "1") (pinfunction "1_1") (pintype "passive"))
      (node (ref "C38") (pin "1") (pinfunction "1_1") (pintype "passive"))
      (node (ref "C40") (pin "1") (pinfunction "1_1") (pintype "passive"))
      (node (ref "C44") (pin "1") (pinfunction "1_1") (pintype "passive"))
      (node (ref "C50") (pin "2") (pinfunction "2_2") (pintype "passive"))
      (node (ref "C53") (pin "2") (pinfunction "2_2") (pintype "passive"))
      (node (ref "C55") (pin "2") (pinfunction "2_2") (pintype "passive"))
      (node (ref "C56") (pin "2") (pinfunction "2_2") (pintype "passive"))
      (node (ref "C58") (pin "2") (pinfunction "2_2") (pintype "passive"))
      (node (ref "C59") (pin "2") (pinfunction "2_2") (pintype "passive"))
      (node (ref "C60") (pin "2") (pinfunction "2_2") (pintype "passive"))
      (node (ref "C61") (pin "2") (pinfunction "2_2") (pintype "passive"))
      (node (ref "C62") (pin "2") (pinfunction "2_2") (pintype "passive"))
      (node (ref "C63") (pin "2") (pinfunction "2_2") (pintype "passive"))
      (node (ref "C64") (pin "2") (pinfunction "2_2") (pintype "passive"))
      (node (ref "C65") (pin "2") (pinfunction "2_2") (pintype "passive"))
      (node (ref "C66") (pin "2") (pinfunction "2_2") (pintype "passive"))
      (node (ref "C67") (pin "2") (pinfunction "2_2") (pintype "passive"))
      (node (ref "C68") (pin "2") (pinfunction "2_2") (pintype "passive"))
      (node (ref "D10") (pin "2") (pinfunction "C2_2") (pintype "passive"))
      (node (ref "D11") (pin "2") (pinfunction "A_2") (pintype "passive"))
      (node (ref "D12") (pin "1") (pinfunction "A_1") (pintype "passive"))
      (node (ref "D13") (pin "2") (pinfunction "C2_2") (pintype "passive"))
      (node (ref "D5") (pin "2") (pinfunction "C2_2") (pintype "passive"))
      (node (ref "D7") (pin "2") (pinfunction "C2_2") (pintype "passive"))
      (node (ref "D8") (pin "2") (pinfunction "C2_2") (pintype "passive"))
      (node (ref "D9") (pin "2") (pinfunction "C2_2") (pintype "passive"))
      (node (ref "IC6") (pin "2") (pinfunction "1_VOUT_2") (pintype "power_in"))
      (node (ref "IC6") (pin "4") (pinfunction "2_VOUT_4") (pintype "power_in"))
      (node (ref "J1") (pin "J2_20") (pinfunction "VDD33_1_J2_20") (pintype "power_in"))
      (node (ref "J1") (pin "J3_18") (pinfunction "VDD33_2_J3_18") (pintype "power_in"))
      (node (ref "R14") (pin "2") (pinfunction "2_2") (pintype "passive"))
      (node (ref "R15") (pin "2") (pinfunction "2_2") (pintype "passive"))
      (node (ref "R54") (pin "2") (pinfunction "2_2") (pintype "passive"))
      (node (ref "R83") (pin "1") (pinfunction "1_1") (pintype "passive"))
      (node (ref "R84") (pin "1") (pinfunction "1_1") (pintype "passive"))
      (node (ref "U2") (pin "111") (pinfunction "VCC_5_111") (pintype "power_in"))
      (node (ref "U2") (pin "121") (pinfunction "VCC_6_121") (pintype "power_in"))
      (node (ref "U2") (pin "126") (pinfunction "VREFH_126") (pintype "power_in"))
      (node (ref "U2") (pin "127") (pinfunction "AVCC0_127") (pintype "power_in"))
      (node (ref "U2") (pin "142") (pinfunction "VCC_142") (pintype "power_in"))
      (node (ref "U2") (pin "21") (pinfunction "VCC_2_21") (pintype "power_in"))
      (node (ref "U2") (pin "49") (pinfunction "VCC_3_49") (pintype "power_in"))
      (node (ref "U2") (pin "68") (pinfunction "VCC_68") (pintype "power_in"))
      (node (ref "U2") (pin "81") (pinfunction "VCC_2_81") (pintype "power_in"))
      (node (ref "U2") (pin "90") (pinfunction "VCC_3_90") (pintype "power_in"))
      (node (ref "U2") (pin "99") (pinfunction "VCC_4_99") (pintype "power_in"))
      (node (ref "X2") (pin "1") (pinfunction "1_1") (pintype "bidirectional"))
    )
    (net (code "121") (name "VCC_CONDUCTIV_SENSOR_SW") (class "Default")
      (node (ref "C8") (pin "1") (pinfunction "1_1") (pintype "passive"))
      (node (ref "IC3") (pin "4") (pinfunction "IN+_4") (pintype "bidirectional"))
      (node (ref "R28") (pin "2") (pinfunction "2_2") (pintype "passive"))
      (node (ref "X3") (pin "1") (pinfunction "1_1") (pintype "bidirectional"))
    )
    (net (code "122") (name "VCC_DISPLAY_2") (class "Default")
      (node (ref "Q16") (pin "2") (pinfunction "DRAIN_2") (pintype "passive"))
      (node (ref "Q16") (pin "4") (pinfunction "DRAIN_4") (pintype "passive"))
      (node (ref "V7") (pin "2") (pinfunction "2_2") (pintype "passive"))
      (node (ref "X13") (pin "9") (pinfunction "S_9") (pintype "passive"))
    )
    (net (code "123") (name "VCC_DISPLAY_3") (class "Default")
      (node (ref "Q12") (pin "2") (pinfunction "DRAIN_2") (pintype "passive"))
      (node (ref "Q12") (pin "4") (pinfunction "DRAIN_4") (pintype "passive"))
      (node (ref "V8") (pin "2") (pinfunction "2_2") (pintype "passive"))
      (node (ref "X13") (pin "10") (pinfunction "S_10") (pintype "passive"))
    )
    (net (code "124") (name "VCC_DSIPLAY_1") (class "Default")
      (node (ref "Q14") (pin "2") (pinfunction "DRAIN_2") (pintype "passive"))
      (node (ref "Q14") (pin "4") (pinfunction "DRAIN_4") (pintype "passive"))
      (node (ref "V6") (pin "2") (pinfunction "2_2") (pintype "passive"))
      (node (ref "X13") (pin "8") (pinfunction "S_8") (pintype "passive"))
    )
    (net (code "125") (name "VCC_PH_SENSOR_SW") (class "Default")
      (node (ref "C10") (pin "1") (pinfunction "1_1") (pintype "passive"))
      (node (ref "IC4") (pin "4") (pinfunction "IN+_4") (pintype "bidirectional"))
      (node (ref "R36") (pin "2") (pinfunction "2_2") (pintype "passive"))
      (node (ref "X4") (pin "1") (pinfunction "1_1") (pintype "bidirectional"))
    )
    (net (code "126") (name "VCC_USBHS") (class "Default")
      (node (ref "U2") (pin "40") (pinfunction "VCC_USBHS_40") (pintype "power_in"))
    )
    (net (code "127") (name "VREFH0") (class "Default")
      (node (ref "U2") (pin "130") (pinfunction "VREFH0_130") (pintype "power_in"))
    )
    (net (code "128") (name "VREFL0") (class "Default")
      (node (ref "U2") (pin "129") (pinfunction "VREFL0_129") (pintype "power_in"))
    )
    (net (code "129") (name "VSS_USB") (class "Default")
      (node (ref "U2") (pin "37") (pinfunction "VSS_USB_37") (pintype "power_in"))
    )
    (net (code "130") (name "V_5V0") (class "Default")
      (node (ref "C14") (pin "1") (pinfunction "1_1") (pintype "passive"))
      (node (ref "C15") (pin "1") (pinfunction "1_1") (pintype "passive"))
      (node (ref "C16") (pin "1") (pinfunction "1_1") (pintype "passive"))
      (node (ref "C20") (pin "1") (pinfunction "1_1") (pintype "passive"))
      (node (ref "C21") (pin "1") (pinfunction "1_1") (pintype "passive"))
      (node (ref "C24") (pin "1") (pinfunction "1_1") (pintype "passive"))
      (node (ref "D11") (pin "1") (pinfunction "C_1") (pintype "passive"))
      (node (ref "IC1") (pin "8") (pinfunction "VCC_8") (pintype "bidirectional"))
      (node (ref "IC6") (pin "3") (pinfunction "VIN_3") (pintype "power_in"))
      (node (ref "L1") (pin "2") (pinfunction "P$2_2") (pintype "bidirectional"))
      (node (ref "R45") (pin "2") (pinfunction "2_2") (pintype "passive"))
      (node (ref "R68") (pin "1") (pinfunction "1_1") (pintype "passive"))
      (node (ref "R85") (pin "2") (pinfunction "2_2") (pintype "passive"))
      (node (ref "X13") (pin "11") (pinfunction "S_11") (pintype "passive"))
    )
    (net (code "131") (name "V_5V0_HMI") (class "Default")
      (node (ref "C26") (pin "2") (pinfunction "2_2") (pintype "passive"))
      (node (ref "C27") (pin "2") (pinfunction "2_2") (pintype "passive"))
      (node (ref "C28") (pin "2") (pinfunction "2_2") (pintype "passive"))
      (node (ref "Q12") (pin "3") (pinfunction "SOURCE_3") (pintype "passive"))
      (node (ref "Q14") (pin "3") (pinfunction "SOURCE_3") (pintype "passive"))
      (node (ref "Q16") (pin "3") (pinfunction "SOURCE_3") (pintype "passive"))
      (node (ref "R59") (pin "2") (pinfunction "2_2") (pintype "passive"))
      (node (ref "R63") (pin "2") (pinfunction "2_2") (pintype "passive"))
      (node (ref "R67") (pin "2") (pinfunction "2_2") (pintype "passive"))
      (node (ref "R68") (pin "2") (pinfunction "2_2") (pintype "passive"))
    )
    (net (code "132") (name "V_24V0") (class "Default")
      (node (ref "C49") (pin "1") (pinfunction "1_1") (pintype "passive"))
      (node (ref "SW1") (pin "1") (pinfunction "1_1") (pintype "passive"))
      (node (ref "X1") (pin "1") (pinfunction "1_1") (pintype "bidirectional"))
    )
    (net (code "133") (name "V_24V0_P") (class "Default")
      (node (ref "C18") (pin "1") (pinfunction "+_1") (pintype "passive"))
      (node (ref "D14") (pin "3") (pinfunction "C_3") (pintype "passive"))
      (node (ref "D15") (pin "3") (pinfunction "C_3") (pintype "passive"))
      (node (ref "D16") (pin "3") (pinfunction "C_3") (pintype "passive"))
      (node (ref "D17") (pin "3") (pinfunction "C_3") (pintype "passive"))
      (node (ref "D3") (pin "3") (pinfunction "C_3") (pintype "passive"))
      (node (ref "IC8") (pin "3") (pinfunction "IN_3") (pintype "power_in"))
      (node (ref "Q1") (pin "3") (pinfunction "SOURCE_3") (pintype "passive"))
      (node (ref "Q3") (pin "3") (pinfunction "SOURCE_3") (pintype "passive"))
      (node (ref "Q5") (pin "3") (pinfunction "SOURCE_3") (pintype "passive"))
      (node (ref "Q6") (pin "3") (pinfunction "SOURCE_3") (pintype "passive"))
      (node (ref "Q8") (pin "3") (pinfunction "SOURCE_3") (pintype "passive"))
      (node (ref "R10") (pin "2") (pinfunction "2_2") (pintype "passive"))
      (node (ref "R2") (pin "2") (pinfunction "2_2") (pintype "passive"))
      (node (ref "R24") (pin "2") (pinfunction "2_2") (pintype "passive"))
      (node (ref "R32") (pin "2") (pinfunction "2_2") (pintype "passive"))
      (node (ref "R40") (pin "2") (pinfunction "2_2") (pintype "passive"))
    )
    (net (code "134") (name "V_CONDUCTIV") (class "Default")
      (node (ref "C7") (pin "2") (pinfunction "2_2") (pintype "passive"))
      (node (ref "D6") (pin "2") (pinfunction "C2_2") (pintype "passive"))
      (node (ref "R21") (pin "2") (pinfunction "2_2") (pintype "passive"))
      (node (ref "R22") (pin "2") (pinfunction "2_2") (pintype "passive"))
      (node (ref "X3") (pin "3") (pinfunction "3_3") (pintype "bidirectional"))
    )
    (net (code "135") (name "V_PH") (class "Default")
      (node (ref "C6") (pin "2") (pinfunction "2_2") (pintype "passive"))
      (node (ref "D4") (pin "2") (pinfunction "C2_2") (pintype "passive"))
      (node (ref "R18") (pin "2") (pinfunction "2_2") (pintype "passive"))
      (node (ref "R19") (pin "2") (pinfunction "2_2") (pintype "passive"))
      (node (ref "X4") (pin "3") (pinfunction "3_3") (pintype "bidirectional"))
    )
    (net (code "136") (name "unconnected-(D4-A-Pad3)") (class "Default")
      (node (ref "D4") (pin "3") (pinfunction "A_3") (pintype "passive"))
    )
    (net (code "137") (name "unconnected-(D6-A-Pad3)") (class "Default")
      (node (ref "D6") (pin "3") (pinfunction "A_3") (pintype "passive"))
    )
    (net (code "138") (name "unconnected-(FID1-PadP$1)") (class "Default")
      (node (ref "FID1") (pin "P$1") (pinfunction "P$1_P$1") (pintype "bidirectional"))
    )
    (net (code "139") (name "unconnected-(FID2-PadP$1)") (class "Default")
      (node (ref "FID2") (pin "P$1") (pinfunction "P$1_P$1") (pintype "bidirectional"))
    )
    (net (code "140") (name "unconnected-(H1-MOUNT-PadB3,0)") (class "Default")
      (node (ref "H1") (pin "B3,0") (pinfunction "MOUNT_B3,0") (pintype "passive"))
    )
    (net (code "141") (name "unconnected-(H2-MOUNT-PadB3,0)") (class "Default")
      (node (ref "H2") (pin "B3,0") (pinfunction "MOUNT_B3,0") (pintype "passive"))
    )
    (net (code "142") (name "unconnected-(H3-MOUNT-PadB3,0)") (class "Default")
      (node (ref "H3") (pin "B3,0") (pinfunction "MOUNT_B3,0") (pintype "passive"))
    )
    (net (code "143") (name "unconnected-(H4-MOUNT-PadB3,0)") (class "Default")
      (node (ref "H4") (pin "B3,0") (pinfunction "MOUNT_B3,0") (pintype "passive"))
    )
    (net (code "144") (name "unconnected-(J1-FLASH_CLK-PadJ2_3)") (class "Default")
      (node (ref "J1") (pin "J2_3") (pinfunction "FLASH_CLK_J2_3") (pintype "bidirectional"))
    )
    (net (code "145") (name "unconnected-(J1-FLASH_CS-PadJ3_1)") (class "Default")
      (node (ref "J1") (pin "J3_1") (pinfunction "FLASH_CS_J3_1") (pintype "bidirectional"))
    )
    (net (code "146") (name "unconnected-(J1-FLASH_SD0-PadJ3_2)") (class "Default")
      (node (ref "J1") (pin "J3_2") (pinfunction "FLASH_SD0_J3_2") (pintype "bidirectional"))
    )
    (net (code "147") (name "unconnected-(J1-FLASH_SD1-PadJ2_1)") (class "Default")
      (node (ref "J1") (pin "J2_1") (pinfunction "FLASH_SD1_J2_1") (pintype "bidirectional"))
    )
    (net (code "148") (name "unconnected-(J1-FLASH_SD2-PadJ3_3)") (class "Default")
      (node (ref "J1") (pin "J3_3") (pinfunction "FLASH_SD2_J3_3") (pintype "bidirectional"))
    )
    (net (code "149") (name "unconnected-(J1-FLASH_SD3-PadJ2_2)") (class "Default")
      (node (ref "J1") (pin "J2_2") (pinfunction "FLASH_SD3_J2_2") (pintype "bidirectional"))
    )
    (net (code "150") (name "unconnected-(J1-IO0-PadJ3_17)") (class "Default")
      (node (ref "J1") (pin "J3_17") (pinfunction "IO0_J3_17") (pintype "bidirectional"))
    )
    (net (code "151") (name "unconnected-(J1-IO2-PadJ3_15)") (class "Default")
      (node (ref "J1") (pin "J3_15") (pinfunction "IO2_J3_15") (pintype "bidirectional"))
    )
    (net (code "152") (name "unconnected-(J1-IO4-PadJ3_16)") (class "Default")
      (node (ref "J1") (pin "J3_16") (pinfunction "IO4_J3_16") (pintype "bidirectional"))
    )
    (net (code "153") (name "unconnected-(J1-IO5-PadJ2_9)") (class "Default")
      (node (ref "J1") (pin "J2_9") (pinfunction "IO5_J2_9") (pintype "bidirectional"))
    )
    (net (code "154") (name "unconnected-(J1-IO12-PadJ3_12)") (class "Default")
      (node (ref "J1") (pin "J3_12") (pinfunction "IO12_J3_12") (pintype "bidirectional"))
    )
    (net (code "155") (name "unconnected-(J1-IO13-PadJ3_13)") (class "Default")
      (node (ref "J1") (pin "J3_13") (pinfunction "IO13_J3_13") (pintype "bidirectional"))
    )
    (net (code "156") (name "unconnected-(J1-IO14-PadJ3_11)") (class "Default")
      (node (ref "J1") (pin "J3_11") (pinfunction "IO14_J3_11") (pintype "bidirectional"))
    )
    (net (code "157") (name "unconnected-(J1-IO15-PadJ3_14)") (class "Default")
      (node (ref "J1") (pin "J3_14") (pinfunction "IO15_J3_14") (pintype "bidirectional"))
    )
    (net (code "158") (name "unconnected-(J1-IO18-PadJ2_8)") (class "Default")
      (node (ref "J1") (pin "J2_8") (pinfunction "IO18_J2_8") (pintype "bidirectional"))
    )
    (net (code "159") (name "unconnected-(J1-IO19-PadJ2_6)") (class "Default")
      (node (ref "J1") (pin "J2_6") (pinfunction "IO19_J2_6") (pintype "bidirectional"))
    )
    (net (code "160") (name "unconnected-(J1-IO21-PadJ2_4)") (class "Default")
      (node (ref "J1") (pin "J2_4") (pinfunction "IO21_J2_4") (pintype "bidirectional"))
    )
    (net (code "161") (name "unconnected-(J1-IO22-PadJ2_5)") (class "Default")
      (node (ref "J1") (pin "J2_5") (pinfunction "IO22_J2_5") (pintype "bidirectional"))
    )
    (net (code "162") (name "unconnected-(J1-IO23-PadJ2_7)") (class "Default")
      (node (ref "J1") (pin "J2_7") (pinfunction "IO23_J2_7") (pintype "bidirectional"))
    )
    (net (code "163") (name "unconnected-(J1-IO25-PadJ3_6)") (class "Default")
      (node (ref "J1") (pin "J3_6") (pinfunction "IO25_J3_6") (pintype "bidirectional"))
    )
    (net (code "164") (name "unconnected-(J1-IO26-PadJ3_7)") (class "Default")
      (node (ref "J1") (pin "J3_7") (pinfunction "IO26_J3_7") (pintype "bidirectional"))
    )
    (net (code "165") (name "unconnected-(J1-IO27-PadJ3_10)") (class "Default")
      (node (ref "J1") (pin "J3_10") (pinfunction "IO27_J3_10") (pintype "bidirectional"))
    )
    (net (code "166") (name "unconnected-(J1-IO32-PadJ3_8)") (class "Default")
      (node (ref "J1") (pin "J3_8") (pinfunction "IO32_J3_8") (pintype "bidirectional"))
    )
    (net (code "167") (name "unconnected-(J1-IO33-PadJ3_9)") (class "Default")
      (node (ref "J1") (pin "J3_9") (pinfunction "IO33_J3_9") (pintype "bidirectional"))
    )
    (net (code "168") (name "unconnected-(J1-IO34-PadJ2_15)") (class "Default")
      (node (ref "J1") (pin "J2_15") (pinfunction "IO34_J2_15") (pintype "input"))
    )
    (net (code "169") (name "unconnected-(J1-IO35-PadJ2_14)") (class "Default")
      (node (ref "J1") (pin "J2_14") (pinfunction "IO35_J2_14") (pintype "input"))
    )
    (net (code "170") (name "unconnected-(J1-IO37-PadJ2_17)") (class "Default")
      (node (ref "J1") (pin "J2_17") (pinfunction "IO37_J2_17") (pintype "input"))
    )
    (net (code "171") (name "unconnected-(J1-IO38-PadJ2_16)") (class "Default")
      (node (ref "J1") (pin "J2_16") (pinfunction "IO38_J2_16") (pintype "input"))
    )
    (net (code "172") (name "unconnected-(J1-RXD0-PadJ2_12)") (class "Default")
      (node (ref "J1") (pin "J2_12") (pinfunction "RXD0_J2_12") (pintype "bidirectional"))
    )
    (net (code "173") (name "unconnected-(J1-SENSOR_VN-PadJ3_5)") (class "Default")
      (node (ref "J1") (pin "J3_5") (pinfunction "SENSOR_VN_J3_5") (pintype "input"))
    )
    (net (code "174") (name "unconnected-(J1-SENSOR_VP-PadJ3_4)") (class "Default")
      (node (ref "J1") (pin "J3_4") (pinfunction "SENSOR_VP_J3_4") (pintype "input"))
    )
    (net (code "175") (name "unconnected-(J1-TXD0-PadJ2_13)") (class "Default")
      (node (ref "J1") (pin "J2_13") (pinfunction "TXD0_J2_13") (pintype "bidirectional"))
    )
    (net (code "176") (name "unconnected-(U2A-P200-Pad57)") (class "Default")
      (node (ref "U2") (pin "57") (pinfunction "P200_57") (pintype "bidirectional"))
    )
    (net (code "177") (name "unconnected-(U2A-P201{slash}MD-Pad56)") (class "Default")
      (node (ref "U2") (pin "56") (pinfunction "P201/MD_56") (pintype "bidirectional"))
    )
    (net (code "178") (name "unconnected-(U2A-P202-Pad46)") (class "Default")
      (node (ref "U2") (pin "46") (pinfunction "P202_46") (pintype "bidirectional"))
    )
    (net (code "179") (name "unconnected-(U2A-P203-Pad45)") (class "Default")
      (node (ref "U2") (pin "45") (pinfunction "P203_45") (pintype "bidirectional"))
    )
    (net (code "180") (name "unconnected-(U2A-P204-Pad44)") (class "Default")
      (node (ref "U2") (pin "44") (pinfunction "P204_44") (pintype "bidirectional"))
    )
    (net (code "181") (name "unconnected-(U2A-P205-Pad43)") (class "Default")
      (node (ref "U2") (pin "43") (pinfunction "P205_43") (pintype "bidirectional"))
    )
    (net (code "182") (name "unconnected-(U2A-P206-Pad42)") (class "Default")
      (node (ref "U2") (pin "42") (pinfunction "P206_42") (pintype "bidirectional"))
    )
    (net (code "183") (name "unconnected-(U2A-P207-Pad41)") (class "Default")
      (node (ref "U2") (pin "41") (pinfunction "P207_41") (pintype "bidirectional"))
    )
    (net (code "184") (name "unconnected-(U2A-P208-Pad54)") (class "Default")
      (node (ref "U2") (pin "54") (pinfunction "P208_54") (pintype "bidirectional"))
    )
    (net (code "185") (name "unconnected-(U2A-P209-Pad53)") (class "Default")
      (node (ref "U2") (pin "53") (pinfunction "P209_53") (pintype "bidirectional"))
    )
    (net (code "186") (name "unconnected-(U2A-P210-Pad52)") (class "Default")
      (node (ref "U2") (pin "52") (pinfunction "P210_52") (pintype "bidirectional"))
    )
    (net (code "187") (name "unconnected-(U2A-P211-Pad51)") (class "Default")
      (node (ref "U2") (pin "51") (pinfunction "P211_51") (pintype "bidirectional"))
    )
    (net (code "188") (name "unconnected-(U2A-P214-Pad50)") (class "Default")
      (node (ref "U2") (pin "50") (pinfunction "P214_50") (pintype "bidirectional"))
    )
    (net (code "189") (name "unconnected-(U2A-P304-Pad66)") (class "Default")
      (node (ref "U2") (pin "66") (pinfunction "P304_66") (pintype "bidirectional"))
    )
    (net (code "190") (name "unconnected-(U2A-P305-Pad65)") (class "Default")
      (node (ref "U2") (pin "65") (pinfunction "P305_65") (pintype "bidirectional"))
    )
    (net (code "191") (name "unconnected-(U2A-P306-Pad64)") (class "Default")
      (node (ref "U2") (pin "64") (pinfunction "P306_64") (pintype "bidirectional"))
    )
    (net (code "192") (name "unconnected-(U2A-P307-Pad63)") (class "Default")
      (node (ref "U2") (pin "63") (pinfunction "P307_63") (pintype "bidirectional"))
    )
    (net (code "193") (name "unconnected-(U2A-P308-Pad62)") (class "Default")
      (node (ref "U2") (pin "62") (pinfunction "P308_62") (pintype "bidirectional"))
    )
    (net (code "194") (name "unconnected-(U2A-P309-Pad61)") (class "Default")
      (node (ref "U2") (pin "61") (pinfunction "P309_61") (pintype "bidirectional"))
    )
    (net (code "195") (name "unconnected-(U2A-P310-Pad60)") (class "Default")
      (node (ref "U2") (pin "60") (pinfunction "P310_60") (pintype "bidirectional"))
    )
    (net (code "196") (name "unconnected-(U2A-P311-Pad59)") (class "Default")
      (node (ref "U2") (pin "59") (pinfunction "P311_59") (pintype "bidirectional"))
    )
    (net (code "197") (name "unconnected-(U2A-P312-Pad58)") (class "Default")
      (node (ref "U2") (pin "58") (pinfunction "P312_58") (pintype "bidirectional"))
    )
    (net (code "198") (name "unconnected-(U2A-P313-Pad47)") (class "Default")
      (node (ref "U2") (pin "47") (pinfunction "P313_47") (pintype "bidirectional"))
    )
    (net (code "199") (name "unconnected-(U2A-P407-Pad36)") (class "Default")
      (node (ref "U2") (pin "36") (pinfunction "P407_36") (pintype "bidirectional"))
    )
    (net (code "200") (name "unconnected-(U2A-P413-Pad30)") (class "Default")
      (node (ref "U2") (pin "30") (pinfunction "P413_30") (pintype "bidirectional"))
    )
    (net (code "201") (name "unconnected-(U2A-P414-Pad29)") (class "Default")
      (node (ref "U2") (pin "29") (pinfunction "P414_29") (pintype "bidirectional"))
    )
    (net (code "202") (name "unconnected-(U2A-P415-Pad28)") (class "Default")
      (node (ref "U2") (pin "28") (pinfunction "P415_28") (pintype "bidirectional"))
    )
    (net (code "203") (name "unconnected-(U2A-P703-Pad11)") (class "Default")
      (node (ref "U2") (pin "11") (pinfunction "P703_11") (pintype "bidirectional"))
    )
    (net (code "204") (name "unconnected-(U2A-P704-Pad12)") (class "Default")
      (node (ref "U2") (pin "12") (pinfunction "P704_12") (pintype "bidirectional"))
    )
    (net (code "205") (name "unconnected-(U2A-P705-Pad13)") (class "Default")
      (node (ref "U2") (pin "13") (pinfunction "P705_13") (pintype "bidirectional"))
    )
    (net (code "206") (name "unconnected-(U2A-P708-Pad27)") (class "Default")
      (node (ref "U2") (pin "27") (pinfunction "P708_27") (pintype "bidirectional"))
    )
    (net (code "207") (name "unconnected-(U2A-P709-Pad26)") (class "Default")
      (node (ref "U2") (pin "26") (pinfunction "P709_26") (pintype "bidirectional"))
    )
    (net (code "208") (name "unconnected-(U2A-P710-Pad25)") (class "Default")
      (node (ref "U2") (pin "25") (pinfunction "P710_25") (pintype "bidirectional"))
    )
    (net (code "209") (name "unconnected-(U2A-P711-Pad24)") (class "Default")
      (node (ref "U2") (pin "24") (pinfunction "P711_24") (pintype "bidirectional"))
    )
    (net (code "210") (name "unconnected-(U2A-P712-Pad23)") (class "Default")
      (node (ref "U2") (pin "23") (pinfunction "P712_23") (pintype "bidirectional"))
    )
    (net (code "211") (name "unconnected-(U2A-P713-Pad22)") (class "Default")
      (node (ref "U2") (pin "22") (pinfunction "P713_22") (pintype "bidirectional"))
    )
    (net (code "212") (name "unconnected-(U2A-USB_DM-Pad38)") (class "Default")
      (node (ref "U2") (pin "38") (pinfunction "USB_DM_38") (pintype "bidirectional"))
    )
    (net (code "213") (name "unconnected-(U2A-USB_DP-Pad39)") (class "Default")
      (node (ref "U2") (pin "39") (pinfunction "USB_DP_39") (pintype "bidirectional"))
    )
    (net (code "214") (name "unconnected-(U2A-XCIN-Pad16)") (class "Default")
      (node (ref "U2") (pin "16") (pinfunction "XCIN_16") (pintype "input"))
    )
    (net (code "215") (name "unconnected-(U2A-XCOUT-Pad17)") (class "Default")
      (node (ref "U2") (pin "17") (pinfunction "XCOUT_17") (pintype "output"))
    )
    (net (code "216") (name "unconnected-(U2B-P000-Pad140)") (class "Default")
      (node (ref "U2") (pin "140") (pinfunction "P000_140") (pintype "bidirectional"))
    )
    (net (code "217") (name "unconnected-(U2B-P001-Pad139)") (class "Default")
      (node (ref "U2") (pin "139") (pinfunction "P001_139") (pintype "bidirectional"))
    )
    (net (code "218") (name "unconnected-(U2B-P002-Pad138)") (class "Default")
      (node (ref "U2") (pin "138") (pinfunction "P002_138") (pintype "bidirectional"))
    )
    (net (code "219") (name "unconnected-(U2B-P003-Pad137)") (class "Default")
      (node (ref "U2") (pin "137") (pinfunction "P003_137") (pintype "bidirectional"))
    )
    (net (code "220") (name "unconnected-(U2B-P004-Pad136)") (class "Default")
      (node (ref "U2") (pin "136") (pinfunction "P004_136") (pintype "bidirectional"))
    )
    (net (code "221") (name "unconnected-(U2B-P005-Pad135)") (class "Default")
      (node (ref "U2") (pin "135") (pinfunction "P005_135") (pintype "bidirectional"))
    )
    (net (code "222") (name "unconnected-(U2B-P006-Pad134)") (class "Default")
      (node (ref "U2") (pin "134") (pinfunction "P006_134") (pintype "bidirectional"))
    )
    (net (code "223") (name "unconnected-(U2B-P007-Pad133)") (class "Default")
      (node (ref "U2") (pin "133") (pinfunction "P007_133") (pintype "bidirectional"))
    )
    (net (code "224") (name "unconnected-(U2B-P008-Pad132)") (class "Default")
      (node (ref "U2") (pin "132") (pinfunction "P008_132") (pintype "bidirectional"))
    )
    (net (code "225") (name "unconnected-(U2B-P009-Pad131)") (class "Default")
      (node (ref "U2") (pin "131") (pinfunction "P009_131") (pintype "bidirectional"))
    )
    (net (code "226") (name "unconnected-(U2B-P014-Pad124)") (class "Default")
      (node (ref "U2") (pin "124") (pinfunction "P014_124") (pintype "bidirectional"))
    )
    (net (code "227") (name "unconnected-(U2B-P015-Pad123)") (class "Default")
      (node (ref "U2") (pin "123") (pinfunction "P015_123") (pintype "bidirectional"))
    )
    (net (code "228") (name "unconnected-(U2B-P106-Pad102)") (class "Default")
      (node (ref "U2") (pin "102") (pinfunction "P106_102") (pintype "bidirectional"))
    )
    (net (code "229") (name "unconnected-(U2B-P107-Pad101)") (class "Default")
      (node (ref "U2") (pin "101") (pinfunction "P107_101") (pintype "bidirectional"))
    )
    (net (code "230") (name "unconnected-(U2B-P112-Pad77)") (class "Default")
      (node (ref "U2") (pin "77") (pinfunction "P112_77") (pintype "bidirectional"))
    )
    (net (code "231") (name "unconnected-(U2B-P113-Pad78)") (class "Default")
      (node (ref "U2") (pin "78") (pinfunction "P113_78") (pintype "bidirectional"))
    )
    (net (code "232") (name "unconnected-(U2B-P114-Pad79)") (class "Default")
      (node (ref "U2") (pin "79") (pinfunction "P114_79") (pintype "bidirectional"))
    )
    (net (code "233") (name "unconnected-(U2B-P115-Pad80)") (class "Default")
      (node (ref "U2") (pin "80") (pinfunction "P115_80") (pintype "bidirectional"))
    )
    (net (code "234") (name "unconnected-(U2B-P505-Pad118)") (class "Default")
      (node (ref "U2") (pin "118") (pinfunction "P505_118") (pintype "bidirectional"))
    )
    (net (code "235") (name "unconnected-(U2B-P506-Pad119)") (class "Default")
      (node (ref "U2") (pin "119") (pinfunction "P506_119") (pintype "bidirectional"))
    )
    (net (code "236") (name "unconnected-(U2B-P507-Pad120)") (class "Default")
      (node (ref "U2") (pin "120") (pinfunction "P507_120") (pintype "bidirectional"))
    )
    (net (code "237") (name "unconnected-(U2B-P511-Pad144)") (class "Default")
      (node (ref "U2") (pin "144") (pinfunction "P511_144") (pintype "bidirectional"))
    )
    (net (code "238") (name "unconnected-(U2B-P512-Pad143)") (class "Default")
      (node (ref "U2") (pin "143") (pinfunction "P512_143") (pintype "bidirectional"))
    )
    (net (code "239") (name "unconnected-(U2B-P600-Pad98)") (class "Default")
      (node (ref "U2") (pin "98") (pinfunction "P600_98") (pintype "bidirectional"))
    )
    (net (code "240") (name "unconnected-(U2B-P601-Pad97)") (class "Default")
      (node (ref "U2") (pin "97") (pinfunction "P601_97") (pintype "bidirectional"))
    )
    (net (code "241") (name "unconnected-(U2B-P602-Pad96)") (class "Default")
      (node (ref "U2") (pin "96") (pinfunction "P602_96") (pintype "bidirectional"))
    )
    (net (code "242") (name "unconnected-(U2B-P603-Pad95)") (class "Default")
      (node (ref "U2") (pin "95") (pinfunction "P603_95") (pintype "bidirectional"))
    )
    (net (code "243") (name "unconnected-(U2B-P604-Pad94)") (class "Default")
      (node (ref "U2") (pin "94") (pinfunction "P604_94") (pintype "bidirectional"))
    )
    (net (code "244") (name "unconnected-(U2B-P605-Pad93)") (class "Default")
      (node (ref "U2") (pin "93") (pinfunction "P605_93") (pintype "bidirectional"))
    )
    (net (code "245") (name "unconnected-(U2B-P608-Pad83)") (class "Default")
      (node (ref "U2") (pin "83") (pinfunction "P608_83") (pintype "bidirectional"))
    )
    (net (code "246") (name "unconnected-(U2B-P609-Pad84)") (class "Default")
      (node (ref "U2") (pin "84") (pinfunction "P609_84") (pintype "bidirectional"))
    )
    (net (code "247") (name "unconnected-(U2B-P610-Pad85)") (class "Default")
      (node (ref "U2") (pin "85") (pinfunction "P610_85") (pintype "bidirectional"))
    )
    (net (code "248") (name "unconnected-(U2B-P611-Pad86)") (class "Default")
      (node (ref "U2") (pin "86") (pinfunction "P611_86") (pintype "bidirectional"))
    )
    (net (code "249") (name "unconnected-(U2B-P612-Pad87)") (class "Default")
      (node (ref "U2") (pin "87") (pinfunction "P612_87") (pintype "bidirectional"))
    )
    (net (code "250") (name "unconnected-(U2B-P613-Pad88)") (class "Default")
      (node (ref "U2") (pin "88") (pinfunction "P613_88") (pintype "bidirectional"))
    )
    (net (code "251") (name "unconnected-(U2B-P614-Pad89)") (class "Default")
      (node (ref "U2") (pin "89") (pinfunction "P614_89") (pintype "bidirectional"))
    )
    (net (code "252") (name "unconnected-(U2B-P800-Pad109)") (class "Default")
      (node (ref "U2") (pin "109") (pinfunction "P800_109") (pintype "bidirectional"))
    )
    (net (code "253") (name "unconnected-(U2B-P801-Pad110)") (class "Default")
      (node (ref "U2") (pin "110") (pinfunction "P801_110") (pintype "bidirectional"))
    )
    (net (code "254") (name "unconnected-(X2-Pad7)") (class "Default")
      (node (ref "X2") (pin "7") (pinfunction "7_7") (pintype "bidirectional"))
    )
    (net (code "255") (name "unconnected-(X2-Pad8)") (class "Default")
      (node (ref "X2") (pin "8") (pinfunction "8_8") (pintype "bidirectional"))
    )
    (net (code "256") (name "unconnected-(X12-Pad3)") (class "Default")
      (node (ref "X12") (pin "3") (pinfunction "3_3") (pintype "passive"))
    )
    (net (code "257") (name "unconnected-(X12-Pad4)") (class "Default")
      (node (ref "X12") (pin "4") (pinfunction "4_4") (pintype "passive"))
    )
    (net (code "258") (name "unconnected-(X12-Pad5)") (class "Default")
      (node (ref "X12") (pin "5") (pinfunction "5_5") (pintype "passive"))
    )
    (net (code "259") (name "unconnected-(X12-Pad6)") (class "Default")
      (node (ref "X12") (pin "6") (pinfunction "6_6") (pintype "passive"))
    )
    (net (code "260") (name "unconnected-(X12-Pad7)") (class "Default")
      (node (ref "X12") (pin "7") (pinfunction "7_7") (pintype "passive"))
    )
    (net (code "261") (name "unconnected-(X12-Pad8)") (class "Default")
      (node (ref "X12") (pin "8") (pinfunction "8_8") (pintype "passive"))
    )
    (net (code "262") (name "unconnected-(X14-Pad3)") (class "Default")
      (node (ref "X14") (pin "3") (pinfunction "3_3") (pintype "passive"))
    )
    (net (code "263") (name "unconnected-(X14-Pad4)") (class "Default")
      (node (ref "X14") (pin "4") (pinfunction "4_4") (pintype "passive"))
    )
    (net (code "264") (name "unconnected-(X14-Pad5)") (class "Default")
      (node (ref "X14") (pin "5") (pinfunction "5_5") (pintype "passive"))
    )
    (net (code "265") (name "unconnected-(X14-Pad6)") (class "Default")
      (node (ref "X14") (pin "6") (pinfunction "6_6") (pintype "passive"))
    )
    (net (code "266") (name "unconnected-(X14-Pad7)") (class "Default")
      (node (ref "X14") (pin "7") (pinfunction "7_7") (pintype "passive"))
    )
    (net (code "267") (name "unconnected-(X14-Pad8)") (class "Default")
      (node (ref "X14") (pin "8") (pinfunction "8_8") (pintype "passive"))
    )
    (net (code "268") (name "{slash}CONDUCTIV_PUMP_LED_ON") (class "Default")
      (node (ref "C35") (pin "2") (pinfunction "2_2") (pintype "passive"))
      (node (ref "Q23") (pin "3") (pinfunction "C_3") (pintype "passive"))
      (node (ref "X13") (pin "3") (pinfunction "S_3") (pintype "passive"))
    )
    (net (code "269") (name "{slash}CONDUCTIV_SENSOR_LED_ON") (class "Default")
      (node (ref "C33") (pin "2") (pinfunction "2_2") (pintype "passive"))
      (node (ref "Q21") (pin "3") (pinfunction "C_3") (pintype "passive"))
      (node (ref "X13") (pin "4") (pinfunction "S_4") (pintype "passive"))
    )
    (net (code "270") (name "{slash}DOSING_DIS") (class "Default")
      (node (ref "C25") (pin "2") (pinfunction "2_2") (pintype "passive"))
      (node (ref "R51") (pin "2") (pinfunction "2_2") (pintype "passive"))
      (node (ref "R52") (pin "2") (pinfunction "2_2") (pintype "passive"))
      (node (ref "X11") (pin "1") (pinfunction "1_1") (pintype "bidirectional"))
    )
    (net (code "271") (name "{slash}DO_COMM_RX_EN") (class "Default")
      (node (ref "R16") (pin "2") (pinfunction "2_2") (pintype "passive"))
      (node (ref "U2") (pin "32") (pinfunction "P411_32") (pintype "bidirectional"))
    )
    (net (code "272") (name "{slash}PH_PUMP_LED_ON") (class "Default")
      (node (ref "C34") (pin "2") (pinfunction "2_2") (pintype "passive"))
      (node (ref "Q22") (pin "3") (pinfunction "C_3") (pintype "passive"))
      (node (ref "X13") (pin "1") (pinfunction "S_1") (pintype "passive"))
    )
    (net (code "273") (name "{slash}PH_SENSOR_LED_ON") (class "Default")
      (node (ref "C32") (pin "2") (pinfunction "2_2") (pintype "passive"))
      (node (ref "Q20") (pin "3") (pinfunction "C_3") (pintype "passive"))
      (node (ref "X13") (pin "2") (pinfunction "S_2") (pintype "passive"))
    )
    (net (code "274") (name "{slash}STATUS_LED_G") (class "Default")
      (node (ref "C30") (pin "2") (pinfunction "2_2") (pintype "passive"))
      (node (ref "Q18") (pin "3") (pinfunction "C_3") (pintype "passive"))
      (node (ref "X13") (pin "6") (pinfunction "S_6") (pintype "passive"))
    )
    (net (code "275") (name "{slash}STATUS_LED_R") (class "Default")
      (node (ref "C31") (pin "2") (pinfunction "2_2") (pintype "passive"))
      (node (ref "Q19") (pin "3") (pinfunction "C_3") (pintype "passive"))
      (node (ref "X13") (pin "5") (pinfunction "S_5") (pintype "passive"))
    )
    (net (code "276") (name "{slash}STATUS_LED_Y") (class "Default")
      (node (ref "C29") (pin "2") (pinfunction "2_2") (pintype "passive"))
      (node (ref "Q17") (pin "3") (pinfunction "C_3") (pintype "passive"))
      (node (ref "X13") (pin "7") (pinfunction "S_7") (pintype "passive"))
    )
  )
)
